# main_oled.net
KiCad netlist of a schematic drawn in EAGLE
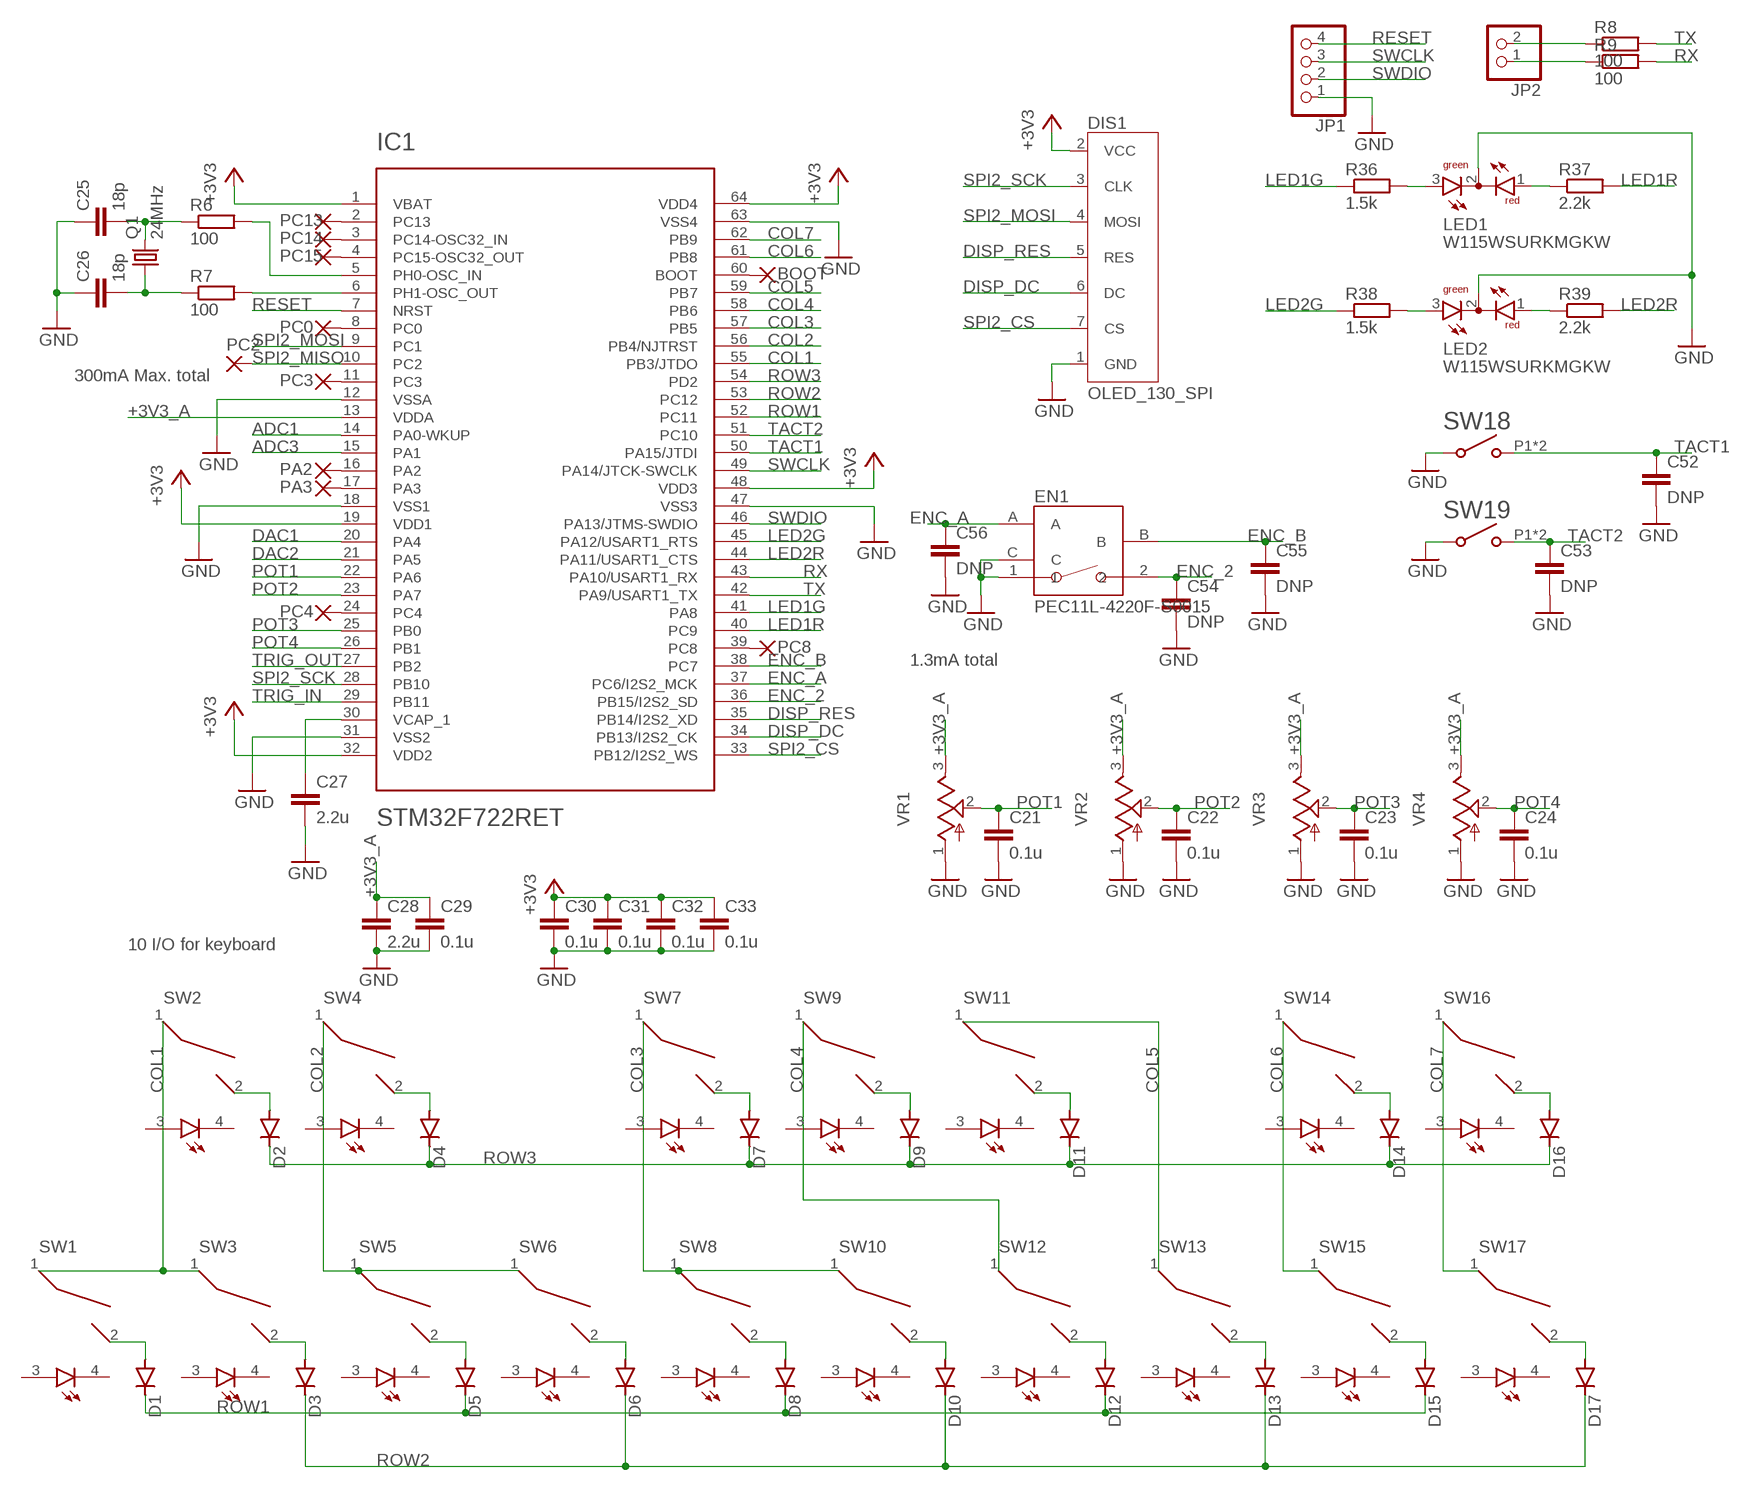
[diagram p0: schematic, sheet 1]
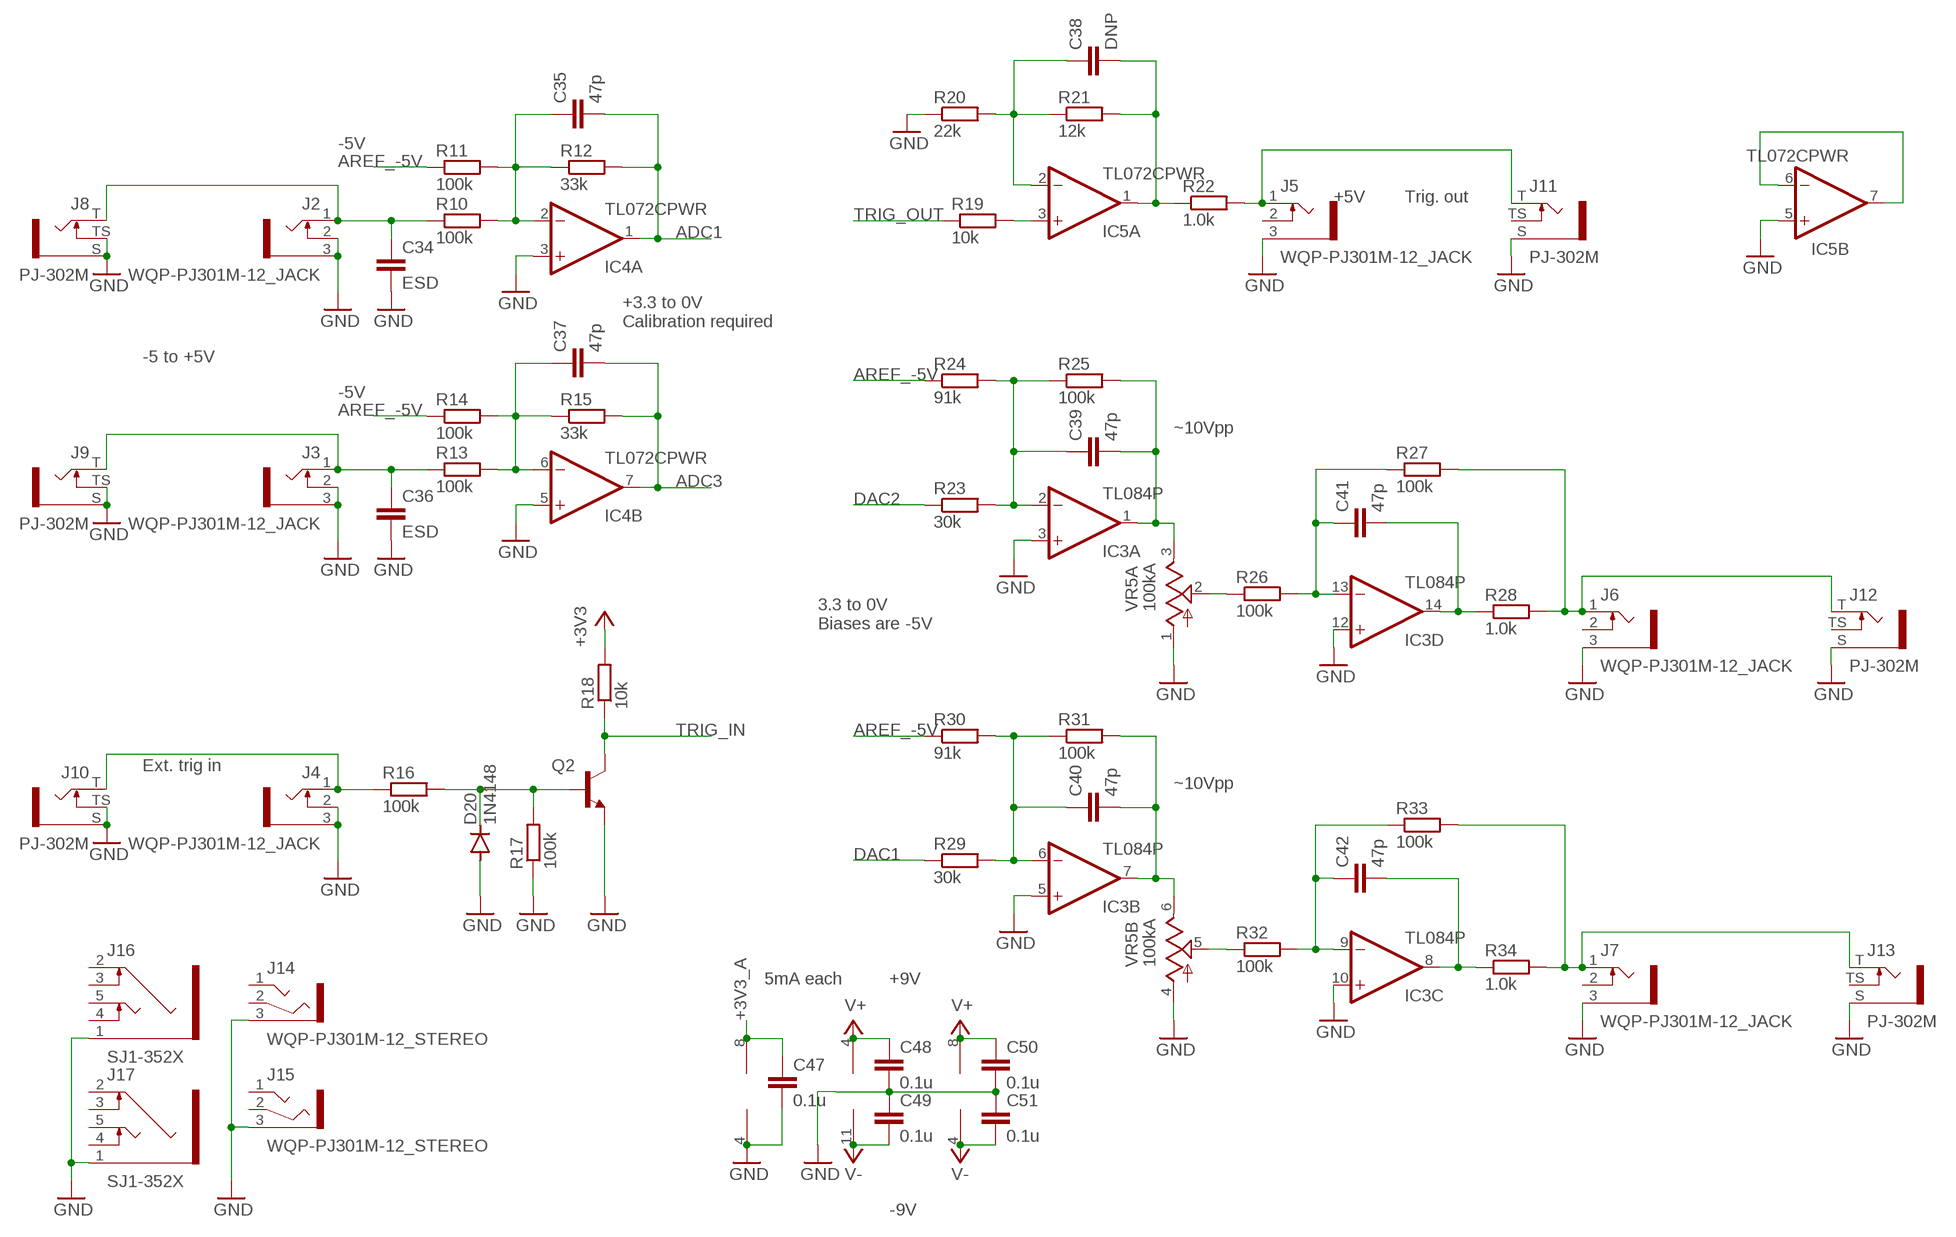
[diagram p1: schematic, sheet 2]
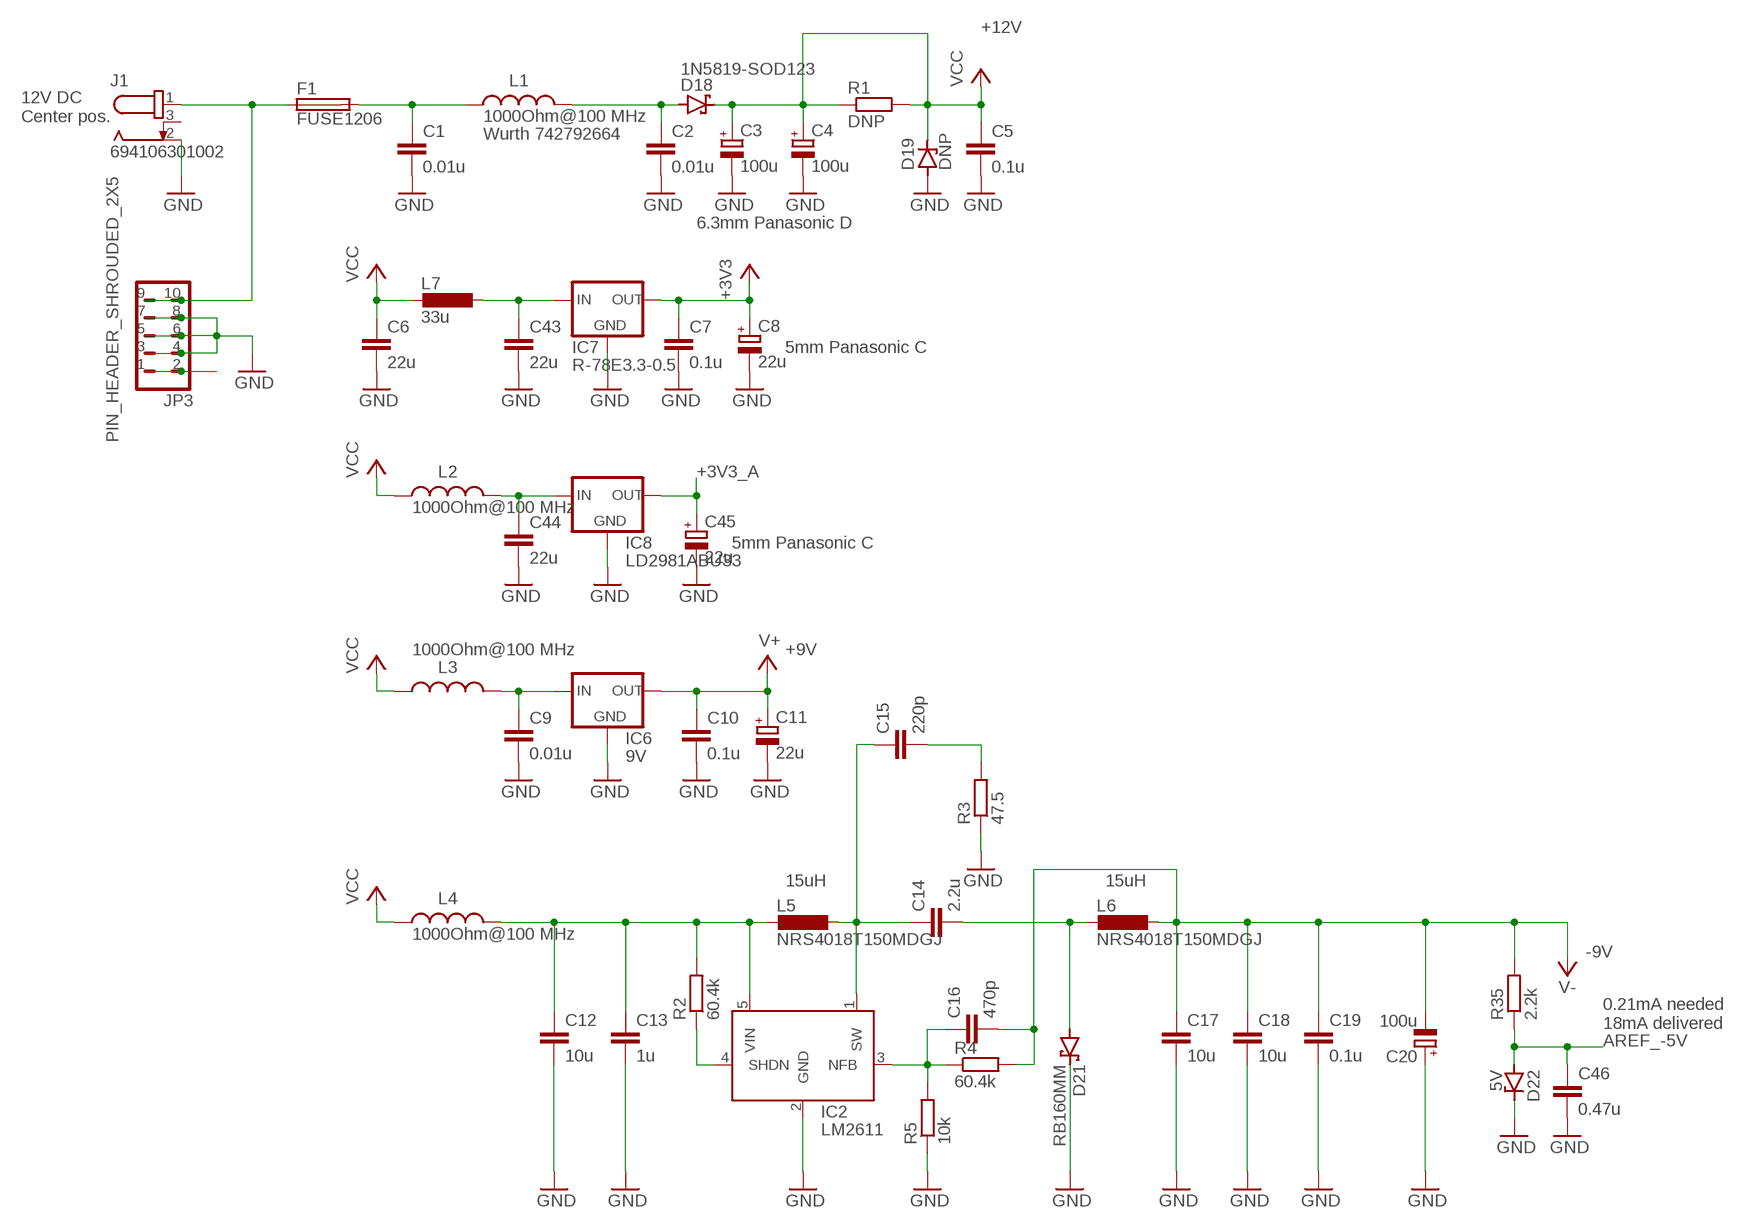
[diagram p2: schematic, sheet 3]
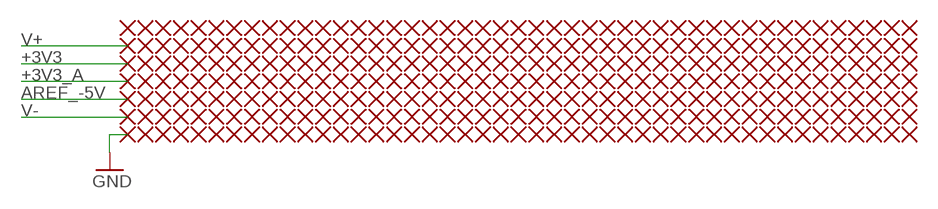
[diagram p3: schematic, sheet 4]

(export (version "E")
  (design (tool "Eeschema 10.0.6"))
  (components
    (comp (ref "C34")
      (value "ESD")
      (footprint "eagle-import:C0603")
      (libsource (lib "eagle-import") (part "C-EUC0603"))
    )
    (comp (ref "C35")
      (value "47p")
      (footprint "eagle-import:C0603")
      (libsource (lib "eagle-import") (part "C-EUC0603"))
    )
    (comp (ref "C36")
      (value "ESD")
      (footprint "eagle-import:C0603")
      (libsource (lib "eagle-import") (part "C-EUC0603"))
    )
    (comp (ref "C37")
      (value "47p")
      (footprint "eagle-import:C0603")
      (libsource (lib "eagle-import") (part "C-EUC0603"))
    )
    (comp (ref "C38")
      (value "DNP")
      (footprint "eagle-import:C0603")
      (libsource (lib "eagle-import") (part "C-EUC0603"))
    )
    (comp (ref "C39")
      (value "47p")
      (footprint "eagle-import:C0603")
      (libsource (lib "eagle-import") (part "C-EUC0603"))
    )
    (comp (ref "C40")
      (value "47p")
      (footprint "eagle-import:C0603")
      (libsource (lib "eagle-import") (part "C-EUC0603"))
    )
    (comp (ref "C41")
      (value "47p")
      (footprint "eagle-import:C0603")
      (libsource (lib "eagle-import") (part "C-EUC0603"))
    )
    (comp (ref "C42")
      (value "47p")
      (footprint "eagle-import:C0603")
      (libsource (lib "eagle-import") (part "C-EUC0603"))
    )
    (comp (ref "C47")
      (value "0.1u")
      (footprint "eagle-import:C0603")
      (libsource (lib "eagle-import") (part "C-EUC0603"))
    )
    (comp (ref "C48")
      (value "0.1u")
      (footprint "eagle-import:C0603")
      (libsource (lib "eagle-import") (part "C-EUC0603"))
    )
    (comp (ref "C49")
      (value "0.1u")
      (footprint "eagle-import:C0603")
      (libsource (lib "eagle-import") (part "C-EUC0603"))
    )
    (comp (ref "C50")
      (value "0.1u")
      (footprint "eagle-import:C0603")
      (libsource (lib "eagle-import") (part "C-EUC0603"))
    )
    (comp (ref "C51")
      (value "0.1u")
      (footprint "eagle-import:C0603")
      (libsource (lib "eagle-import") (part "C-EUC0603"))
    )
    (comp (ref "D20")
      (value "1N4148")
      (footprint "eagle-import:SOD123")
      (libsource (lib "eagle-import") (part "og_diode_DIODE-SOD123"))
    )
    (comp (ref "IC3")
      (value "TL084P")
      (footprint "eagle-import:TSSOP14")
      (libsource (lib "eagle-import") (part "TL084P"))
    )
    (comp (ref "IC4")
      (value "TL072CPWR")
      (footprint "eagle-import:TSSOP8")
      (libsource (lib "eagle-import") (part "TL072CPWR"))
    )
    (comp (ref "IC5")
      (value "TL072CPWR")
      (footprint "eagle-import:TSSOP8")
      (libsource (lib "eagle-import") (part "TL072CPWR"))
    )
    (comp (ref "J2")
      (value "WQP-PJ301M-12_JACK")
      (footprint "eagle-import:WQP-PJ301M-12_JACK")
      (libsource (lib "eagle-import") (part "WQP-PJ301M-12_JACK"))
    )
    (comp (ref "J3")
      (value "WQP-PJ301M-12_JACK")
      (footprint "eagle-import:WQP-PJ301M-12_JACK")
      (libsource (lib "eagle-import") (part "WQP-PJ301M-12_JACK"))
    )
    (comp (ref "J4")
      (value "WQP-PJ301M-12_JACK")
      (footprint "eagle-import:WQP-PJ301M-12_JACK")
      (libsource (lib "eagle-import") (part "WQP-PJ301M-12_JACK"))
    )
    (comp (ref "J5")
      (value "WQP-PJ301M-12_JACK")
      (footprint "eagle-import:WQP-PJ301M-12_JACK")
      (libsource (lib "eagle-import") (part "WQP-PJ301M-12_JACK"))
    )
    (comp (ref "J6")
      (value "WQP-PJ301M-12_JACK")
      (footprint "eagle-import:WQP-PJ301M-12_JACK")
      (libsource (lib "eagle-import") (part "WQP-PJ301M-12_JACK"))
    )
    (comp (ref "J7")
      (value "WQP-PJ301M-12_JACK")
      (footprint "eagle-import:WQP-PJ301M-12_JACK")
      (libsource (lib "eagle-import") (part "WQP-PJ301M-12_JACK"))
    )
    (comp (ref "J8")
      (value "PJ-302M")
      (footprint "eagle-import:PJ-302M")
      (libsource (lib "eagle-import") (part "PJ-302M"))
    )
    (comp (ref "J9")
      (value "PJ-302M")
      (footprint "eagle-import:PJ-302M")
      (libsource (lib "eagle-import") (part "PJ-302M"))
    )
    (comp (ref "J10")
      (value "PJ-302M")
      (footprint "eagle-import:PJ-302M")
      (libsource (lib "eagle-import") (part "PJ-302M"))
    )
    (comp (ref "J11")
      (value "PJ-302M")
      (footprint "eagle-import:PJ-302M")
      (libsource (lib "eagle-import") (part "PJ-302M"))
    )
    (comp (ref "J12")
      (value "PJ-302M")
      (footprint "eagle-import:PJ-302M")
      (libsource (lib "eagle-import") (part "PJ-302M"))
    )
    (comp (ref "J13")
      (value "PJ-302M")
      (footprint "eagle-import:PJ-302M")
      (libsource (lib "eagle-import") (part "PJ-302M"))
    )
    (comp (ref "J14")
      (value "WQP-PJ301M-12_STEREO")
      (footprint "eagle-import:WQP-PJ301M-12_JACK")
      (libsource (lib "eagle-import") (part "WQP-PJ301M-12_STEREO"))
    )
    (comp (ref "J15")
      (value "WQP-PJ301M-12_STEREO")
      (footprint "eagle-import:WQP-PJ301M-12_JACK")
      (libsource (lib "eagle-import") (part "WQP-PJ301M-12_STEREO"))
    )
    (comp (ref "J16")
      (value "SJ1-352X")
      (footprint "eagle-import:SJ1-352X")
      (libsource (lib "eagle-import") (part "SJ1-352X"))
    )
    (comp (ref "J17")
      (value "SJ1-352X")
      (footprint "eagle-import:SJ1-352X")
      (libsource (lib "eagle-import") (part "SJ1-352X"))
    )
    (comp (ref "Q2")
      (value "MMBT3904LT1-NPN-SOT23-BEC")
      (footprint "eagle-import:SOT23-BEC")
      (libsource (lib "eagle-import") (part "-NPN-SOT23-BECMMBT3904LT1"))
    )
    (comp (ref "R10")
      (value "100k")
      (footprint "eagle-import:R0603")
      (libsource (lib "eagle-import") (part "R-EU_R0603"))
    )
    (comp (ref "R11")
      (value "100k")
      (footprint "eagle-import:R0603")
      (libsource (lib "eagle-import") (part "R-EU_R0603"))
    )
    (comp (ref "R12")
      (value "33k")
      (footprint "eagle-import:R0603")
      (libsource (lib "eagle-import") (part "R-EU_R0603"))
    )
    (comp (ref "R13")
      (value "100k")
      (footprint "eagle-import:R0603")
      (libsource (lib "eagle-import") (part "R-EU_R0603"))
    )
    (comp (ref "R14")
      (value "100k")
      (footprint "eagle-import:R0603")
      (libsource (lib "eagle-import") (part "R-EU_R0603"))
    )
    (comp (ref "R15")
      (value "33k")
      (footprint "eagle-import:R0603")
      (libsource (lib "eagle-import") (part "R-EU_R0603"))
    )
    (comp (ref "R16")
      (value "100k")
      (footprint "eagle-import:R0603")
      (libsource (lib "eagle-import") (part "R-EU_R0603"))
    )
    (comp (ref "R17")
      (value "100k")
      (footprint "eagle-import:R0603")
      (libsource (lib "eagle-import") (part "R-EU_R0603"))
    )
    (comp (ref "R18")
      (value "10k")
      (footprint "eagle-import:R0603")
      (libsource (lib "eagle-import") (part "R-EU_R0603"))
    )
    (comp (ref "R19")
      (value "10k")
      (footprint "eagle-import:R0603")
      (libsource (lib "eagle-import") (part "R-EU_R0603"))
    )
    (comp (ref "R20")
      (value "22k")
      (footprint "eagle-import:R0603")
      (libsource (lib "eagle-import") (part "R-EU_R0603"))
    )
    (comp (ref "R21")
      (value "12k")
      (footprint "eagle-import:R0603")
      (libsource (lib "eagle-import") (part "R-EU_R0603"))
    )
    (comp (ref "R22")
      (value "1.0k")
      (footprint "eagle-import:R0603")
      (libsource (lib "eagle-import") (part "R-EU_R0603"))
    )
    (comp (ref "R23")
      (value "30k")
      (footprint "eagle-import:R0603")
      (libsource (lib "eagle-import") (part "R-EU_R0603"))
    )
    (comp (ref "R24")
      (value "91k")
      (footprint "eagle-import:R0603")
      (libsource (lib "eagle-import") (part "R-EU_R0603"))
    )
    (comp (ref "R25")
      (value "100k")
      (footprint "eagle-import:R0603")
      (libsource (lib "eagle-import") (part "R-EU_R0603"))
    )
    (comp (ref "R26")
      (value "100k")
      (footprint "eagle-import:R0603")
      (libsource (lib "eagle-import") (part "R-EU_R0603"))
    )
    (comp (ref "R27")
      (value "100k")
      (footprint "eagle-import:R0603")
      (libsource (lib "eagle-import") (part "R-EU_R0603"))
    )
    (comp (ref "R28")
      (value "1.0k")
      (footprint "eagle-import:R0603")
      (libsource (lib "eagle-import") (part "R-EU_R0603"))
    )
    (comp (ref "R29")
      (value "30k")
      (footprint "eagle-import:R0603")
      (libsource (lib "eagle-import") (part "R-EU_R0603"))
    )
    (comp (ref "R30")
      (value "91k")
      (footprint "eagle-import:R0603")
      (libsource (lib "eagle-import") (part "R-EU_R0603"))
    )
    (comp (ref "R31")
      (value "100k")
      (footprint "eagle-import:R0603")
      (libsource (lib "eagle-import") (part "R-EU_R0603"))
    )
    (comp (ref "R32")
      (value "100k")
      (footprint "eagle-import:R0603")
      (libsource (lib "eagle-import") (part "R-EU_R0603"))
    )
    (comp (ref "R33")
      (value "100k")
      (footprint "eagle-import:R0603")
      (libsource (lib "eagle-import") (part "R-EU_R0603"))
    )
    (comp (ref "R34")
      (value "1.0k")
      (footprint "eagle-import:R0603")
      (libsource (lib "eagle-import") (part "R-EU_R0603"))
    )
    (comp (ref "VR5")
      (value "100kA")
      (footprint "eagle-import:9MM_V_DUAL")
      (libsource (lib "eagle-import") (part "9MM_V_DUAL"))
    )
    (comp (ref "P1")
      (value "PERF_2.54")
      (footprint "eagle-import:PERF_2.54")
      (libsource (lib "eagle-import") (part "PERF_2.54"))
    )
    (comp (ref "P2")
      (value "PERF_2.54")
      (footprint "eagle-import:PERF_2.54")
      (libsource (lib "eagle-import") (part "PERF_2.54"))
    )
    (comp (ref "P3")
      (value "PERF_2.54")
      (footprint "eagle-import:PERF_2.54")
      (libsource (lib "eagle-import") (part "PERF_2.54"))
    )
    (comp (ref "P4")
      (value "PERF_2.54")
      (footprint "eagle-import:PERF_2.54")
      (libsource (lib "eagle-import") (part "PERF_2.54"))
    )
    (comp (ref "P5")
      (value "PERF_2.54")
      (footprint "eagle-import:PERF_2.54")
      (libsource (lib "eagle-import") (part "PERF_2.54"))
    )
    (comp (ref "P6")
      (value "PERF_2.54")
      (footprint "eagle-import:PERF_2.54")
      (libsource (lib "eagle-import") (part "PERF_2.54"))
    )
    (comp (ref "P7")
      (value "PERF_2.54")
      (footprint "eagle-import:PERF_2.54")
      (libsource (lib "eagle-import") (part "PERF_2.54"))
    )
    (comp (ref "P8")
      (value "PERF_2.54")
      (footprint "eagle-import:PERF_2.54")
      (libsource (lib "eagle-import") (part "PERF_2.54"))
    )
    (comp (ref "P9")
      (value "PERF_2.54")
      (footprint "eagle-import:PERF_2.54")
      (libsource (lib "eagle-import") (part "PERF_2.54"))
    )
    (comp (ref "P10")
      (value "PERF_2.54")
      (footprint "eagle-import:PERF_2.54")
      (libsource (lib "eagle-import") (part "PERF_2.54"))
    )
    (comp (ref "P11")
      (value "PERF_2.54")
      (footprint "eagle-import:PERF_2.54")
      (libsource (lib "eagle-import") (part "PERF_2.54"))
    )
    (comp (ref "P12")
      (value "PERF_2.54")
      (footprint "eagle-import:PERF_2.54")
      (libsource (lib "eagle-import") (part "PERF_2.54"))
    )
    (comp (ref "P13")
      (value "PERF_2.54")
      (footprint "eagle-import:PERF_2.54")
      (libsource (lib "eagle-import") (part "PERF_2.54"))
    )
    (comp (ref "P14")
      (value "PERF_2.54")
      (footprint "eagle-import:PERF_2.54")
      (libsource (lib "eagle-import") (part "PERF_2.54"))
    )
    (comp (ref "P15")
      (value "PERF_2.54")
      (footprint "eagle-import:PERF_2.54")
      (libsource (lib "eagle-import") (part "PERF_2.54"))
    )
    (comp (ref "P16")
      (value "PERF_2.54")
      (footprint "eagle-import:PERF_2.54")
      (libsource (lib "eagle-import") (part "PERF_2.54"))
    )
    (comp (ref "P17")
      (value "PERF_2.54")
      (footprint "eagle-import:PERF_2.54")
      (libsource (lib "eagle-import") (part "PERF_2.54"))
    )
    (comp (ref "P18")
      (value "PERF_2.54")
      (footprint "eagle-import:PERF_2.54")
      (libsource (lib "eagle-import") (part "PERF_2.54"))
    )
    (comp (ref "P19")
      (value "PERF_2.54")
      (footprint "eagle-import:PERF_2.54")
      (libsource (lib "eagle-import") (part "PERF_2.54"))
    )
    (comp (ref "P20")
      (value "PERF_2.54")
      (footprint "eagle-import:PERF_2.54")
      (libsource (lib "eagle-import") (part "PERF_2.54"))
    )
    (comp (ref "P21")
      (value "PERF_2.54")
      (footprint "eagle-import:PERF_2.54")
      (libsource (lib "eagle-import") (part "PERF_2.54"))
    )
    (comp (ref "P22")
      (value "PERF_2.54")
      (footprint "eagle-import:PERF_2.54")
      (libsource (lib "eagle-import") (part "PERF_2.54"))
    )
    (comp (ref "P23")
      (value "PERF_2.54")
      (footprint "eagle-import:PERF_2.54")
      (libsource (lib "eagle-import") (part "PERF_2.54"))
    )
    (comp (ref "P24")
      (value "PERF_2.54")
      (footprint "eagle-import:PERF_2.54")
      (libsource (lib "eagle-import") (part "PERF_2.54"))
    )
    (comp (ref "P25")
      (value "PERF_2.54")
      (footprint "eagle-import:PERF_2.54")
      (libsource (lib "eagle-import") (part "PERF_2.54"))
    )
    (comp (ref "P26")
      (value "PERF_2.54")
      (footprint "eagle-import:PERF_2.54")
      (libsource (lib "eagle-import") (part "PERF_2.54"))
    )
    (comp (ref "P27")
      (value "PERF_2.54")
      (footprint "eagle-import:PERF_2.54")
      (libsource (lib "eagle-import") (part "PERF_2.54"))
    )
    (comp (ref "P28")
      (value "PERF_2.54")
      (footprint "eagle-import:PERF_2.54")
      (libsource (lib "eagle-import") (part "PERF_2.54"))
    )
    (comp (ref "P29")
      (value "PERF_2.54")
      (footprint "eagle-import:PERF_2.54")
      (libsource (lib "eagle-import") (part "PERF_2.54"))
    )
    (comp (ref "P30")
      (value "PERF_2.54")
      (footprint "eagle-import:PERF_2.54")
      (libsource (lib "eagle-import") (part "PERF_2.54"))
    )
    (comp (ref "P31")
      (value "PERF_2.54")
      (footprint "eagle-import:PERF_2.54")
      (libsource (lib "eagle-import") (part "PERF_2.54"))
    )
    (comp (ref "P32")
      (value "PERF_2.54")
      (footprint "eagle-import:PERF_2.54")
      (libsource (lib "eagle-import") (part "PERF_2.54"))
    )
    (comp (ref "P33")
      (value "PERF_2.54")
      (footprint "eagle-import:PERF_2.54")
      (libsource (lib "eagle-import") (part "PERF_2.54"))
    )
    (comp (ref "P34")
      (value "PERF_2.54")
      (footprint "eagle-import:PERF_2.54")
      (libsource (lib "eagle-import") (part "PERF_2.54"))
    )
    (comp (ref "P35")
      (value "PERF_2.54")
      (footprint "eagle-import:PERF_2.54")
      (libsource (lib "eagle-import") (part "PERF_2.54"))
    )
    (comp (ref "P36")
      (value "PERF_2.54")
      (footprint "eagle-import:PERF_2.54")
      (libsource (lib "eagle-import") (part "PERF_2.54"))
    )
    (comp (ref "P37")
      (value "PERF_2.54")
      (footprint "eagle-import:PERF_2.54")
      (libsource (lib "eagle-import") (part "PERF_2.54"))
    )
    (comp (ref "P38")
      (value "PERF_2.54")
      (footprint "eagle-import:PERF_2.54")
      (libsource (lib "eagle-import") (part "PERF_2.54"))
    )
    (comp (ref "P39")
      (value "PERF_2.54")
      (footprint "eagle-import:PERF_2.54")
      (libsource (lib "eagle-import") (part "PERF_2.54"))
    )
    (comp (ref "P40")
      (value "PERF_2.54")
      (footprint "eagle-import:PERF_2.54")
      (libsource (lib "eagle-import") (part "PERF_2.54"))
    )
    (comp (ref "P41")
      (value "PERF_2.54")
      (footprint "eagle-import:PERF_2.54")
      (libsource (lib "eagle-import") (part "PERF_2.54"))
    )
    (comp (ref "P42")
      (value "PERF_2.54")
      (footprint "eagle-import:PERF_2.54")
      (libsource (lib "eagle-import") (part "PERF_2.54"))
    )
    (comp (ref "P43")
      (value "PERF_2.54")
      (footprint "eagle-import:PERF_2.54")
      (libsource (lib "eagle-import") (part "PERF_2.54"))
    )
    (comp (ref "P44")
      (value "PERF_2.54")
      (footprint "eagle-import:PERF_2.54")
      (libsource (lib "eagle-import") (part "PERF_2.54"))
    )
    (comp (ref "P45")
      (value "PERF_2.54")
      (footprint "eagle-import:PERF_2.54")
      (libsource (lib "eagle-import") (part "PERF_2.54"))
    )
    (comp (ref "P46")
      (value "PERF_2.54")
      (footprint "eagle-import:PERF_2.54")
      (libsource (lib "eagle-import") (part "PERF_2.54"))
    )
    (comp (ref "P47")
      (value "PERF_2.54")
      (footprint "eagle-import:PERF_2.54")
      (libsource (lib "eagle-import") (part "PERF_2.54"))
    )
    (comp (ref "P48")
      (value "PERF_2.54")
      (footprint "eagle-import:PERF_2.54")
      (libsource (lib "eagle-import") (part "PERF_2.54"))
    )
    (comp (ref "P49")
      (value "PERF_2.54")
      (footprint "eagle-import:PERF_2.54")
      (libsource (lib "eagle-import") (part "PERF_2.54"))
    )
    (comp (ref "P50")
      (value "PERF_2.54")
      (footprint "eagle-import:PERF_2.54")
      (libsource (lib "eagle-import") (part "PERF_2.54"))
    )
    (comp (ref "P51")
      (value "PERF_2.54")
      (footprint "eagle-import:PERF_2.54")
      (libsource (lib "eagle-import") (part "PERF_2.54"))
    )
    (comp (ref "P52")
      (value "PERF_2.54")
      (footprint "eagle-import:PERF_2.54")
      (libsource (lib "eagle-import") (part "PERF_2.54"))
    )
    (comp (ref "P53")
      (value "PERF_2.54")
      (footprint "eagle-import:PERF_2.54")
      (libsource (lib "eagle-import") (part "PERF_2.54"))
    )
    (comp (ref "P54")
      (value "PERF_2.54")
      (footprint "eagle-import:PERF_2.54")
      (libsource (lib "eagle-import") (part "PERF_2.54"))
    )
    (comp (ref "P55")
      (value "PERF_2.54")
      (footprint "eagle-import:PERF_2.54")
      (libsource (lib "eagle-import") (part "PERF_2.54"))
    )
    (comp (ref "P56")
      (value "PERF_2.54")
      (footprint "eagle-import:PERF_2.54")
      (libsource (lib "eagle-import") (part "PERF_2.54"))
    )
    (comp (ref "P57")
      (value "PERF_2.54")
      (footprint "eagle-import:PERF_2.54")
      (libsource (lib "eagle-import") (part "PERF_2.54"))
    )
    (comp (ref "P58")
      (value "PERF_2.54")
      (footprint "eagle-import:PERF_2.54")
      (libsource (lib "eagle-import") (part "PERF_2.54"))
    )
    (comp (ref "P59")
      (value "PERF_2.54")
      (footprint "eagle-import:PERF_2.54")
      (libsource (lib "eagle-import") (part "PERF_2.54"))
    )
    (comp (ref "P60")
      (value "PERF_2.54")
      (footprint "eagle-import:PERF_2.54")
      (libsource (lib "eagle-import") (part "PERF_2.54"))
    )
    (comp (ref "P61")
      (value "PERF_2.54")
      (footprint "eagle-import:PERF_2.54")
      (libsource (lib "eagle-import") (part "PERF_2.54"))
    )
    (comp (ref "P62")
      (value "PERF_2.54")
      (footprint "eagle-import:PERF_2.54")
      (libsource (lib "eagle-import") (part "PERF_2.54"))
    )
    (comp (ref "P63")
      (value "PERF_2.54")
      (footprint "eagle-import:PERF_2.54")
      (libsource (lib "eagle-import") (part "PERF_2.54"))
    )
    (comp (ref "P64")
      (value "PERF_2.54")
      (footprint "eagle-import:PERF_2.54")
      (libsource (lib "eagle-import") (part "PERF_2.54"))
    )
    (comp (ref "P65")
      (value "PERF_2.54")
      (footprint "eagle-import:PERF_2.54")
      (libsource (lib "eagle-import") (part "PERF_2.54"))
    )
    (comp (ref "P66")
      (value "PERF_2.54")
      (footprint "eagle-import:PERF_2.54")
      (libsource (lib "eagle-import") (part "PERF_2.54"))
    )
    (comp (ref "P67")
      (value "PERF_2.54")
      (footprint "eagle-import:PERF_2.54")
      (libsource (lib "eagle-import") (part "PERF_2.54"))
    )
    (comp (ref "P68")
      (value "PERF_2.54")
      (footprint "eagle-import:PERF_2.54")
      (libsource (lib "eagle-import") (part "PERF_2.54"))
    )
    (comp (ref "P69")
      (value "PERF_2.54")
      (footprint "eagle-import:PERF_2.54")
      (libsource (lib "eagle-import") (part "PERF_2.54"))
    )
    (comp (ref "P70")
      (value "PERF_2.54")
      (footprint "eagle-import:PERF_2.54")
      (libsource (lib "eagle-import") (part "PERF_2.54"))
    )
    (comp (ref "P71")
      (value "PERF_2.54")
      (footprint "eagle-import:PERF_2.54")
      (libsource (lib "eagle-import") (part "PERF_2.54"))
    )
    (comp (ref "P72")
      (value "PERF_2.54")
      (footprint "eagle-import:PERF_2.54")
      (libsource (lib "eagle-import") (part "PERF_2.54"))
    )
    (comp (ref "P73")
      (value "PERF_2.54")
      (footprint "eagle-import:PERF_2.54")
      (libsource (lib "eagle-import") (part "PERF_2.54"))
    )
    (comp (ref "P74")
      (value "PERF_2.54")
      (footprint "eagle-import:PERF_2.54")
      (libsource (lib "eagle-import") (part "PERF_2.54"))
    )
    (comp (ref "P75")
      (value "PERF_2.54")
      (footprint "eagle-import:PERF_2.54")
      (libsource (lib "eagle-import") (part "PERF_2.54"))
    )
    (comp (ref "P76")
      (value "PERF_2.54")
      (footprint "eagle-import:PERF_2.54")
      (libsource (lib "eagle-import") (part "PERF_2.54"))
    )
    (comp (ref "P77")
      (value "PERF_2.54")
      (footprint "eagle-import:PERF_2.54")
      (libsource (lib "eagle-import") (part "PERF_2.54"))
    )
    (comp (ref "P78")
      (value "PERF_2.54")
      (footprint "eagle-import:PERF_2.54")
      (libsource (lib "eagle-import") (part "PERF_2.54"))
    )
    (comp (ref "P79")
      (value "PERF_2.54")
      (footprint "eagle-import:PERF_2.54")
      (libsource (lib "eagle-import") (part "PERF_2.54"))
    )
    (comp (ref "P80")
      (value "PERF_2.54")
      (footprint "eagle-import:PERF_2.54")
      (libsource (lib "eagle-import") (part "PERF_2.54"))
    )
    (comp (ref "P81")
      (value "PERF_2.54")
      (footprint "eagle-import:PERF_2.54")
      (libsource (lib "eagle-import") (part "PERF_2.54"))
    )
    (comp (ref "P82")
      (value "PERF_2.54")
      (footprint "eagle-import:PERF_2.54")
      (libsource (lib "eagle-import") (part "PERF_2.54"))
    )
    (comp (ref "P83")
      (value "PERF_2.54")
      (footprint "eagle-import:PERF_2.54")
      (libsource (lib "eagle-import") (part "PERF_2.54"))
    )
    (comp (ref "P84")
      (value "PERF_2.54")
      (footprint "eagle-import:PERF_2.54")
      (libsource (lib "eagle-import") (part "PERF_2.54"))
    )
    (comp (ref "P85")
      (value "PERF_2.54")
      (footprint "eagle-import:PERF_2.54")
      (libsource (lib "eagle-import") (part "PERF_2.54"))
    )
    (comp (ref "P86")
      (value "PERF_2.54")
      (footprint "eagle-import:PERF_2.54")
      (libsource (lib "eagle-import") (part "PERF_2.54"))
    )
    (comp (ref "P87")
      (value "PERF_2.54")
      (footprint "eagle-import:PERF_2.54")
      (libsource (lib "eagle-import") (part "PERF_2.54"))
    )
    (comp (ref "P88")
      (value "PERF_2.54")
      (footprint "eagle-import:PERF_2.54")
      (libsource (lib "eagle-import") (part "PERF_2.54"))
    )
    (comp (ref "P89")
      (value "PERF_2.54")
      (footprint "eagle-import:PERF_2.54")
      (libsource (lib "eagle-import") (part "PERF_2.54"))
    )
    (comp (ref "P90")
      (value "PERF_2.54")
      (footprint "eagle-import:PERF_2.54")
      (libsource (lib "eagle-import") (part "PERF_2.54"))
    )
    (comp (ref "P91")
      (value "PERF_2.54")
      (footprint "eagle-import:PERF_2.54")
      (libsource (lib "eagle-import") (part "PERF_2.54"))
    )
    (comp (ref "P92")
      (value "PERF_2.54")
      (footprint "eagle-import:PERF_2.54")
      (libsource (lib "eagle-import") (part "PERF_2.54"))
    )
    (comp (ref "P93")
      (value "PERF_2.54")
      (footprint "eagle-import:PERF_2.54")
      (libsource (lib "eagle-import") (part "PERF_2.54"))
    )
    (comp (ref "P94")
      (value "PERF_2.54")
      (footprint "eagle-import:PERF_2.54")
      (libsource (lib "eagle-import") (part "PERF_2.54"))
    )
    (comp (ref "P95")
      (value "PERF_2.54")
      (footprint "eagle-import:PERF_2.54")
      (libsource (lib "eagle-import") (part "PERF_2.54"))
    )
    (comp (ref "P96")
      (value "PERF_2.54")
      (footprint "eagle-import:PERF_2.54")
      (libsource (lib "eagle-import") (part "PERF_2.54"))
    )
    (comp (ref "P97")
      (value "PERF_2.54")
      (footprint "eagle-import:PERF_2.54")
      (libsource (lib "eagle-import") (part "PERF_2.54"))
    )
    (comp (ref "P98")
      (value "PERF_2.54")
      (footprint "eagle-import:PERF_2.54")
      (libsource (lib "eagle-import") (part "PERF_2.54"))
    )
    (comp (ref "P99")
      (value "PERF_2.54")
      (footprint "eagle-import:PERF_2.54")
      (libsource (lib "eagle-import") (part "PERF_2.54"))
    )
    (comp (ref "P100")
      (value "PERF_2.54")
      (footprint "eagle-import:PERF_2.54")
      (libsource (lib "eagle-import") (part "PERF_2.54"))
    )
    (comp (ref "P101")
      (value "PERF_2.54")
      (footprint "eagle-import:PERF_2.54")
      (libsource (lib "eagle-import") (part "PERF_2.54"))
    )
    (comp (ref "P102")
      (value "PERF_2.54")
      (footprint "eagle-import:PERF_2.54")
      (libsource (lib "eagle-import") (part "PERF_2.54"))
    )
    (comp (ref "P103")
      (value "PERF_2.54")
      (footprint "eagle-import:PERF_2.54")
      (libsource (lib "eagle-import") (part "PERF_2.54"))
    )
    (comp (ref "P104")
      (value "PERF_2.54")
      (footprint "eagle-import:PERF_2.54")
      (libsource (lib "eagle-import") (part "PERF_2.54"))
    )
    (comp (ref "P105")
      (value "PERF_2.54")
      (footprint "eagle-import:PERF_2.54")
      (libsource (lib "eagle-import") (part "PERF_2.54"))
    )
    (comp (ref "P106")
      (value "PERF_2.54")
      (footprint "eagle-import:PERF_2.54")
      (libsource (lib "eagle-import") (part "PERF_2.54"))
    )
    (comp (ref "P107")
      (value "PERF_2.54")
      (footprint "eagle-import:PERF_2.54")
      (libsource (lib "eagle-import") (part "PERF_2.54"))
    )
    (comp (ref "P108")
      (value "PERF_2.54")
      (footprint "eagle-import:PERF_2.54")
      (libsource (lib "eagle-import") (part "PERF_2.54"))
    )
    (comp (ref "P109")
      (value "PERF_2.54")
      (footprint "eagle-import:PERF_2.54")
      (libsource (lib "eagle-import") (part "PERF_2.54"))
    )
    (comp (ref "P110")
      (value "PERF_2.54")
      (footprint "eagle-import:PERF_2.54")
      (libsource (lib "eagle-import") (part "PERF_2.54"))
    )
    (comp (ref "P111")
      (value "PERF_2.54")
      (footprint "eagle-import:PERF_2.54")
      (libsource (lib "eagle-import") (part "PERF_2.54"))
    )
    (comp (ref "P112")
      (value "PERF_2.54")
      (footprint "eagle-import:PERF_2.54")
      (libsource (lib "eagle-import") (part "PERF_2.54"))
    )
    (comp (ref "P113")
      (value "PERF_2.54")
      (footprint "eagle-import:PERF_2.54")
      (libsource (lib "eagle-import") (part "PERF_2.54"))
    )
    (comp (ref "P114")
      (value "PERF_2.54")
      (footprint "eagle-import:PERF_2.54")
      (libsource (lib "eagle-import") (part "PERF_2.54"))
    )
    (comp (ref "P115")
      (value "PERF_2.54")
      (footprint "eagle-import:PERF_2.54")
      (libsource (lib "eagle-import") (part "PERF_2.54"))
    )
    (comp (ref "P116")
      (value "PERF_2.54")
      (footprint "eagle-import:PERF_2.54")
      (libsource (lib "eagle-import") (part "PERF_2.54"))
    )
    (comp (ref "P117")
      (value "PERF_2.54")
      (footprint "eagle-import:PERF_2.54")
      (libsource (lib "eagle-import") (part "PERF_2.54"))
    )
    (comp (ref "P118")
      (value "PERF_2.54")
      (footprint "eagle-import:PERF_2.54")
      (libsource (lib "eagle-import") (part "PERF_2.54"))
    )
    (comp (ref "P119")
      (value "PERF_2.54")
      (footprint "eagle-import:PERF_2.54")
      (libsource (lib "eagle-import") (part "PERF_2.54"))
    )
    (comp (ref "P120")
      (value "PERF_2.54")
      (footprint "eagle-import:PERF_2.54")
      (libsource (lib "eagle-import") (part "PERF_2.54"))
    )
    (comp (ref "P121")
      (value "PERF_2.54")
      (footprint "eagle-import:PERF_2.54")
      (libsource (lib "eagle-import") (part "PERF_2.54"))
    )
    (comp (ref "P122")
      (value "PERF_2.54")
      (footprint "eagle-import:PERF_2.54")
      (libsource (lib "eagle-import") (part "PERF_2.54"))
    )
    (comp (ref "P123")
      (value "PERF_2.54")
      (footprint "eagle-import:PERF_2.54")
      (libsource (lib "eagle-import") (part "PERF_2.54"))
    )
    (comp (ref "P124")
      (value "PERF_2.54")
      (footprint "eagle-import:PERF_2.54")
      (libsource (lib "eagle-import") (part "PERF_2.54"))
    )
    (comp (ref "P125")
      (value "PERF_2.54")
      (footprint "eagle-import:PERF_2.54")
      (libsource (lib "eagle-import") (part "PERF_2.54"))
    )
    (comp (ref "P126")
      (value "PERF_2.54")
      (footprint "eagle-import:PERF_2.54")
      (libsource (lib "eagle-import") (part "PERF_2.54"))
    )
    (comp (ref "P127")
      (value "PERF_2.54")
      (footprint "eagle-import:PERF_2.54")
      (libsource (lib "eagle-import") (part "PERF_2.54"))
    )
    (comp (ref "P128")
      (value "PERF_2.54")
      (footprint "eagle-import:PERF_2.54")
      (libsource (lib "eagle-import") (part "PERF_2.54"))
    )
    (comp (ref "P129")
      (value "PERF_2.54")
      (footprint "eagle-import:PERF_2.54")
      (libsource (lib "eagle-import") (part "PERF_2.54"))
    )
    (comp (ref "P130")
      (value "PERF_2.54")
      (footprint "eagle-import:PERF_2.54")
      (libsource (lib "eagle-import") (part "PERF_2.54"))
    )
    (comp (ref "P131")
      (value "PERF_2.54")
      (footprint "eagle-import:PERF_2.54")
      (libsource (lib "eagle-import") (part "PERF_2.54"))
    )
    (comp (ref "P132")
      (value "PERF_2.54")
      (footprint "eagle-import:PERF_2.54")
      (libsource (lib "eagle-import") (part "PERF_2.54"))
    )
    (comp (ref "P133")
      (value "PERF_2.54")
      (footprint "eagle-import:PERF_2.54")
      (libsource (lib "eagle-import") (part "PERF_2.54"))
    )
    (comp (ref "P134")
      (value "PERF_2.54")
      (footprint "eagle-import:PERF_2.54")
      (libsource (lib "eagle-import") (part "PERF_2.54"))
    )
    (comp (ref "P135")
      (value "PERF_2.54")
      (footprint "eagle-import:PERF_2.54")
      (libsource (lib "eagle-import") (part "PERF_2.54"))
    )
    (comp (ref "P136")
      (value "PERF_2.54")
      (footprint "eagle-import:PERF_2.54")
      (libsource (lib "eagle-import") (part "PERF_2.54"))
    )
    (comp (ref "P137")
      (value "PERF_2.54")
      (footprint "eagle-import:PERF_2.54")
      (libsource (lib "eagle-import") (part "PERF_2.54"))
    )
    (comp (ref "P138")
      (value "PERF_2.54")
      (footprint "eagle-import:PERF_2.54")
      (libsource (lib "eagle-import") (part "PERF_2.54"))
    )
    (comp (ref "P139")
      (value "PERF_2.54")
      (footprint "eagle-import:PERF_2.54")
      (libsource (lib "eagle-import") (part "PERF_2.54"))
    )
    (comp (ref "P140")
      (value "PERF_2.54")
      (footprint "eagle-import:PERF_2.54")
      (libsource (lib "eagle-import") (part "PERF_2.54"))
    )
    (comp (ref "P141")
      (value "PERF_2.54")
      (footprint "eagle-import:PERF_2.54")
      (libsource (lib "eagle-import") (part "PERF_2.54"))
    )
    (comp (ref "P142")
      (value "PERF_2.54")
      (footprint "eagle-import:PERF_2.54")
      (libsource (lib "eagle-import") (part "PERF_2.54"))
    )
    (comp (ref "P143")
      (value "PERF_2.54")
      (footprint "eagle-import:PERF_2.54")
      (libsource (lib "eagle-import") (part "PERF_2.54"))
    )
    (comp (ref "P144")
      (value "PERF_2.54")
      (footprint "eagle-import:PERF_2.54")
      (libsource (lib "eagle-import") (part "PERF_2.54"))
    )
    (comp (ref "P145")
      (value "PERF_2.54")
      (footprint "eagle-import:PERF_2.54")
      (libsource (lib "eagle-import") (part "PERF_2.54"))
    )
    (comp (ref "P146")
      (value "PERF_2.54")
      (footprint "eagle-import:PERF_2.54")
      (libsource (lib "eagle-import") (part "PERF_2.54"))
    )
    (comp (ref "P147")
      (value "PERF_2.54")
      (footprint "eagle-import:PERF_2.54")
      (libsource (lib "eagle-import") (part "PERF_2.54"))
    )
    (comp (ref "P148")
      (value "PERF_2.54")
      (footprint "eagle-import:PERF_2.54")
      (libsource (lib "eagle-import") (part "PERF_2.54"))
    )
    (comp (ref "P149")
      (value "PERF_2.54")
      (footprint "eagle-import:PERF_2.54")
      (libsource (lib "eagle-import") (part "PERF_2.54"))
    )
    (comp (ref "P150")
      (value "PERF_2.54")
      (footprint "eagle-import:PERF_2.54")
      (libsource (lib "eagle-import") (part "PERF_2.54"))
    )
    (comp (ref "P151")
      (value "PERF_2.54")
      (footprint "eagle-import:PERF_2.54")
      (libsource (lib "eagle-import") (part "PERF_2.54"))
    )
    (comp (ref "P152")
      (value "PERF_2.54")
      (footprint "eagle-import:PERF_2.54")
      (libsource (lib "eagle-import") (part "PERF_2.54"))
    )
    (comp (ref "P153")
      (value "PERF_2.54")
      (footprint "eagle-import:PERF_2.54")
      (libsource (lib "eagle-import") (part "PERF_2.54"))
    )
    (comp (ref "P154")
      (value "PERF_2.54")
      (footprint "eagle-import:PERF_2.54")
      (libsource (lib "eagle-import") (part "PERF_2.54"))
    )
    (comp (ref "P155")
      (value "PERF_2.54")
      (footprint "eagle-import:PERF_2.54")
      (libsource (lib "eagle-import") (part "PERF_2.54"))
    )
    (comp (ref "P156")
      (value "PERF_2.54")
      (footprint "eagle-import:PERF_2.54")
      (libsource (lib "eagle-import") (part "PERF_2.54"))
    )
    (comp (ref "P157")
      (value "PERF_2.54")
      (footprint "eagle-import:PERF_2.54")
      (libsource (lib "eagle-import") (part "PERF_2.54"))
    )
    (comp (ref "P158")
      (value "PERF_2.54")
      (footprint "eagle-import:PERF_2.54")
      (libsource (lib "eagle-import") (part "PERF_2.54"))
    )
    (comp (ref "P159")
      (value "PERF_2.54")
      (footprint "eagle-import:PERF_2.54")
      (libsource (lib "eagle-import") (part "PERF_2.54"))
    )
    (comp (ref "P160")
      (value "PERF_2.54")
      (footprint "eagle-import:PERF_2.54")
      (libsource (lib "eagle-import") (part "PERF_2.54"))
    )
    (comp (ref "P161")
      (value "PERF_2.54")
      (footprint "eagle-import:PERF_2.54")
      (libsource (lib "eagle-import") (part "PERF_2.54"))
    )
    (comp (ref "P162")
      (value "PERF_2.54")
      (footprint "eagle-import:PERF_2.54")
      (libsource (lib "eagle-import") (part "PERF_2.54"))
    )
    (comp (ref "P163")
      (value "PERF_2.54")
      (footprint "eagle-import:PERF_2.54")
      (libsource (lib "eagle-import") (part "PERF_2.54"))
    )
    (comp (ref "P164")
      (value "PERF_2.54")
      (footprint "eagle-import:PERF_2.54")
      (libsource (lib "eagle-import") (part "PERF_2.54"))
    )
    (comp (ref "P165")
      (value "PERF_2.54")
      (footprint "eagle-import:PERF_2.54")
      (libsource (lib "eagle-import") (part "PERF_2.54"))
    )
    (comp (ref "P166")
      (value "PERF_2.54")
      (footprint "eagle-import:PERF_2.54")
      (libsource (lib "eagle-import") (part "PERF_2.54"))
    )
    (comp (ref "P167")
      (value "PERF_2.54")
      (footprint "eagle-import:PERF_2.54")
      (libsource (lib "eagle-import") (part "PERF_2.54"))
    )
    (comp (ref "P168")
      (value "PERF_2.54")
      (footprint "eagle-import:PERF_2.54")
      (libsource (lib "eagle-import") (part "PERF_2.54"))
    )
    (comp (ref "P169")
      (value "PERF_2.54")
      (footprint "eagle-import:PERF_2.54")
      (libsource (lib "eagle-import") (part "PERF_2.54"))
    )
    (comp (ref "P170")
      (value "PERF_2.54")
      (footprint "eagle-import:PERF_2.54")
      (libsource (lib "eagle-import") (part "PERF_2.54"))
    )
    (comp (ref "P171")
      (value "PERF_2.54")
      (footprint "eagle-import:PERF_2.54")
      (libsource (lib "eagle-import") (part "PERF_2.54"))
    )
    (comp (ref "P172")
      (value "PERF_2.54")
      (footprint "eagle-import:PERF_2.54")
      (libsource (lib "eagle-import") (part "PERF_2.54"))
    )
    (comp (ref "P173")
      (value "PERF_2.54")
      (footprint "eagle-import:PERF_2.54")
      (libsource (lib "eagle-import") (part "PERF_2.54"))
    )
    (comp (ref "P174")
      (value "PERF_2.54")
      (footprint "eagle-import:PERF_2.54")
      (libsource (lib "eagle-import") (part "PERF_2.54"))
    )
    (comp (ref "P175")
      (value "PERF_2.54")
      (footprint "eagle-import:PERF_2.54")
      (libsource (lib "eagle-import") (part "PERF_2.54"))
    )
    (comp (ref "P176")
      (value "PERF_2.54")
      (footprint "eagle-import:PERF_2.54")
      (libsource (lib "eagle-import") (part "PERF_2.54"))
    )
    (comp (ref "P177")
      (value "PERF_2.54")
      (footprint "eagle-import:PERF_2.54")
      (libsource (lib "eagle-import") (part "PERF_2.54"))
    )
    (comp (ref "P178")
      (value "PERF_2.54")
      (footprint "eagle-import:PERF_2.54")
      (libsource (lib "eagle-import") (part "PERF_2.54"))
    )
    (comp (ref "P179")
      (value "PERF_2.54")
      (footprint "eagle-import:PERF_2.54")
      (libsource (lib "eagle-import") (part "PERF_2.54"))
    )
    (comp (ref "P180")
      (value "PERF_2.54")
      (footprint "eagle-import:PERF_2.54")
      (libsource (lib "eagle-import") (part "PERF_2.54"))
    )
    (comp (ref "P181")
      (value "PERF_2.54")
      (footprint "eagle-import:PERF_2.54")
      (libsource (lib "eagle-import") (part "PERF_2.54"))
    )
    (comp (ref "P182")
      (value "PERF_2.54")
      (footprint "eagle-import:PERF_2.54")
      (libsource (lib "eagle-import") (part "PERF_2.54"))
    )
    (comp (ref "P183")
      (value "PERF_2.54")
      (footprint "eagle-import:PERF_2.54")
      (libsource (lib "eagle-import") (part "PERF_2.54"))
    )
    (comp (ref "P184")
      (value "PERF_2.54")
      (footprint "eagle-import:PERF_2.54")
      (libsource (lib "eagle-import") (part "PERF_2.54"))
    )
    (comp (ref "P185")
      (value "PERF_2.54")
      (footprint "eagle-import:PERF_2.54")
      (libsource (lib "eagle-import") (part "PERF_2.54"))
    )
    (comp (ref "P186")
      (value "PERF_2.54")
      (footprint "eagle-import:PERF_2.54")
      (libsource (lib "eagle-import") (part "PERF_2.54"))
    )
    (comp (ref "P187")
      (value "PERF_2.54")
      (footprint "eagle-import:PERF_2.54")
      (libsource (lib "eagle-import") (part "PERF_2.54"))
    )
    (comp (ref "P188")
      (value "PERF_2.54")
      (footprint "eagle-import:PERF_2.54")
      (libsource (lib "eagle-import") (part "PERF_2.54"))
    )
    (comp (ref "P189")
      (value "PERF_2.54")
      (footprint "eagle-import:PERF_2.54")
      (libsource (lib "eagle-import") (part "PERF_2.54"))
    )
    (comp (ref "P190")
      (value "PERF_2.54")
      (footprint "eagle-import:PERF_2.54")
      (libsource (lib "eagle-import") (part "PERF_2.54"))
    )
    (comp (ref "P191")
      (value "PERF_2.54")
      (footprint "eagle-import:PERF_2.54")
      (libsource (lib "eagle-import") (part "PERF_2.54"))
    )
    (comp (ref "P192")
      (value "PERF_2.54")
      (footprint "eagle-import:PERF_2.54")
      (libsource (lib "eagle-import") (part "PERF_2.54"))
    )
    (comp (ref "P193")
      (value "PERF_2.54")
      (footprint "eagle-import:PERF_2.54")
      (libsource (lib "eagle-import") (part "PERF_2.54"))
    )
    (comp (ref "P194")
      (value "PERF_2.54")
      (footprint "eagle-import:PERF_2.54")
      (libsource (lib "eagle-import") (part "PERF_2.54"))
    )
    (comp (ref "P195")
      (value "PERF_2.54")
      (footprint "eagle-import:PERF_2.54")
      (libsource (lib "eagle-import") (part "PERF_2.54"))
    )
    (comp (ref "P196")
      (value "PERF_2.54")
      (footprint "eagle-import:PERF_2.54")
      (libsource (lib "eagle-import") (part "PERF_2.54"))
    )
    (comp (ref "P197")
      (value "PERF_2.54")
      (footprint "eagle-import:PERF_2.54")
      (libsource (lib "eagle-import") (part "PERF_2.54"))
    )
    (comp (ref "P198")
      (value "PERF_2.54")
      (footprint "eagle-import:PERF_2.54")
      (libsource (lib "eagle-import") (part "PERF_2.54"))
    )
    (comp (ref "P199")
      (value "PERF_2.54")
      (footprint "eagle-import:PERF_2.54")
      (libsource (lib "eagle-import") (part "PERF_2.54"))
    )
    (comp (ref "P200")
      (value "PERF_2.54")
      (footprint "eagle-import:PERF_2.54")
      (libsource (lib "eagle-import") (part "PERF_2.54"))
    )
    (comp (ref "P201")
      (value "PERF_2.54")
      (footprint "eagle-import:PERF_2.54")
      (libsource (lib "eagle-import") (part "PERF_2.54"))
    )
    (comp (ref "P202")
      (value "PERF_2.54")
      (footprint "eagle-import:PERF_2.54")
      (libsource (lib "eagle-import") (part "PERF_2.54"))
    )
    (comp (ref "P203")
      (value "PERF_2.54")
      (footprint "eagle-import:PERF_2.54")
      (libsource (lib "eagle-import") (part "PERF_2.54"))
    )
    (comp (ref "P204")
      (value "PERF_2.54")
      (footprint "eagle-import:PERF_2.54")
      (libsource (lib "eagle-import") (part "PERF_2.54"))
    )
    (comp (ref "P205")
      (value "PERF_2.54")
      (footprint "eagle-import:PERF_2.54")
      (libsource (lib "eagle-import") (part "PERF_2.54"))
    )
    (comp (ref "P206")
      (value "PERF_2.54")
      (footprint "eagle-import:PERF_2.54")
      (libsource (lib "eagle-import") (part "PERF_2.54"))
    )
    (comp (ref "P207")
      (value "PERF_2.54")
      (footprint "eagle-import:PERF_2.54")
      (libsource (lib "eagle-import") (part "PERF_2.54"))
    )
    (comp (ref "P208")
      (value "PERF_2.54")
      (footprint "eagle-import:PERF_2.54")
      (libsource (lib "eagle-import") (part "PERF_2.54"))
    )
    (comp (ref "P209")
      (value "PERF_2.54")
      (footprint "eagle-import:PERF_2.54")
      (libsource (lib "eagle-import") (part "PERF_2.54"))
    )
    (comp (ref "P210")
      (value "PERF_2.54")
      (footprint "eagle-import:PERF_2.54")
      (libsource (lib "eagle-import") (part "PERF_2.54"))
    )
    (comp (ref "P211")
      (value "PERF_2.54")
      (footprint "eagle-import:PERF_2.54")
      (libsource (lib "eagle-import") (part "PERF_2.54"))
    )
    (comp (ref "P212")
      (value "PERF_2.54")
      (footprint "eagle-import:PERF_2.54")
      (libsource (lib "eagle-import") (part "PERF_2.54"))
    )
    (comp (ref "P213")
      (value "PERF_2.54")
      (footprint "eagle-import:PERF_2.54")
      (libsource (lib "eagle-import") (part "PERF_2.54"))
    )
    (comp (ref "P214")
      (value "PERF_2.54")
      (footprint "eagle-import:PERF_2.54")
      (libsource (lib "eagle-import") (part "PERF_2.54"))
    )
    (comp (ref "P215")
      (value "PERF_2.54")
      (footprint "eagle-import:PERF_2.54")
      (libsource (lib "eagle-import") (part "PERF_2.54"))
    )
    (comp (ref "P216")
      (value "PERF_2.54")
      (footprint "eagle-import:PERF_2.54")
      (libsource (lib "eagle-import") (part "PERF_2.54"))
    )
    (comp (ref "P217")
      (value "PERF_2.54")
      (footprint "eagle-import:PERF_2.54")
      (libsource (lib "eagle-import") (part "PERF_2.54"))
    )
    (comp (ref "P218")
      (value "PERF_2.54")
      (footprint "eagle-import:PERF_2.54")
      (libsource (lib "eagle-import") (part "PERF_2.54"))
    )
    (comp (ref "P219")
      (value "PERF_2.54")
      (footprint "eagle-import:PERF_2.54")
      (libsource (lib "eagle-import") (part "PERF_2.54"))
    )
    (comp (ref "P220")
      (value "PERF_2.54")
      (footprint "eagle-import:PERF_2.54")
      (libsource (lib "eagle-import") (part "PERF_2.54"))
    )
    (comp (ref "P221")
      (value "PERF_2.54")
      (footprint "eagle-import:PERF_2.54")
      (libsource (lib "eagle-import") (part "PERF_2.54"))
    )
    (comp (ref "P222")
      (value "PERF_2.54")
      (footprint "eagle-import:PERF_2.54")
      (libsource (lib "eagle-import") (part "PERF_2.54"))
    )
    (comp (ref "P223")
      (value "PERF_2.54")
      (footprint "eagle-import:PERF_2.54")
      (libsource (lib "eagle-import") (part "PERF_2.54"))
    )
    (comp (ref "P224")
      (value "PERF_2.54")
      (footprint "eagle-import:PERF_2.54")
      (libsource (lib "eagle-import") (part "PERF_2.54"))
    )
    (comp (ref "P225")
      (value "PERF_2.54")
      (footprint "eagle-import:PERF_2.54")
      (libsource (lib "eagle-import") (part "PERF_2.54"))
    )
    (comp (ref "P226")
      (value "PERF_2.54")
      (footprint "eagle-import:PERF_2.54")
      (libsource (lib "eagle-import") (part "PERF_2.54"))
    )
    (comp (ref "P227")
      (value "PERF_2.54")
      (footprint "eagle-import:PERF_2.54")
      (libsource (lib "eagle-import") (part "PERF_2.54"))
    )
    (comp (ref "P228")
      (value "PERF_2.54")
      (footprint "eagle-import:PERF_2.54")
      (libsource (lib "eagle-import") (part "PERF_2.54"))
    )
    (comp (ref "P229")
      (value "PERF_2.54")
      (footprint "eagle-import:PERF_2.54")
      (libsource (lib "eagle-import") (part "PERF_2.54"))
    )
    (comp (ref "P230")
      (value "PERF_2.54")
      (footprint "eagle-import:PERF_2.54")
      (libsource (lib "eagle-import") (part "PERF_2.54"))
    )
    (comp (ref "P231")
      (value "PERF_2.54")
      (footprint "eagle-import:PERF_2.54")
      (libsource (lib "eagle-import") (part "PERF_2.54"))
    )
    (comp (ref "P232")
      (value "PERF_2.54")
      (footprint "eagle-import:PERF_2.54")
      (libsource (lib "eagle-import") (part "PERF_2.54"))
    )
    (comp (ref "P233")
      (value "PERF_2.54")
      (footprint "eagle-import:PERF_2.54")
      (libsource (lib "eagle-import") (part "PERF_2.54"))
    )
    (comp (ref "P234")
      (value "PERF_2.54")
      (footprint "eagle-import:PERF_2.54")
      (libsource (lib "eagle-import") (part "PERF_2.54"))
    )
    (comp (ref "P235")
      (value "PERF_2.54")
      (footprint "eagle-import:PERF_2.54")
      (libsource (lib "eagle-import") (part "PERF_2.54"))
    )
    (comp (ref "P236")
      (value "PERF_2.54")
      (footprint "eagle-import:PERF_2.54")
      (libsource (lib "eagle-import") (part "PERF_2.54"))
    )
    (comp (ref "P237")
      (value "PERF_2.54")
      (footprint "eagle-import:PERF_2.54")
      (libsource (lib "eagle-import") (part "PERF_2.54"))
    )
    (comp (ref "P238")
      (value "PERF_2.54")
      (footprint "eagle-import:PERF_2.54")
      (libsource (lib "eagle-import") (part "PERF_2.54"))
    )
    (comp (ref "P239")
      (value "PERF_2.54")
      (footprint "eagle-import:PERF_2.54")
      (libsource (lib "eagle-import") (part "PERF_2.54"))
    )
    (comp (ref "P240")
      (value "PERF_2.54")
      (footprint "eagle-import:PERF_2.54")
      (libsource (lib "eagle-import") (part "PERF_2.54"))
    )
    (comp (ref "P241")
      (value "PERF_2.54")
      (footprint "eagle-import:PERF_2.54")
      (libsource (lib "eagle-import") (part "PERF_2.54"))
    )
    (comp (ref "P242")
      (value "PERF_2.54")
      (footprint "eagle-import:PERF_2.54")
      (libsource (lib "eagle-import") (part "PERF_2.54"))
    )
    (comp (ref "P243")
      (value "PERF_2.54")
      (footprint "eagle-import:PERF_2.54")
      (libsource (lib "eagle-import") (part "PERF_2.54"))
    )
    (comp (ref "P244")
      (value "PERF_2.54")
      (footprint "eagle-import:PERF_2.54")
      (libsource (lib "eagle-import") (part "PERF_2.54"))
    )
    (comp (ref "P245")
      (value "PERF_2.54")
      (footprint "eagle-import:PERF_2.54")
      (libsource (lib "eagle-import") (part "PERF_2.54"))
    )
    (comp (ref "P246")
      (value "PERF_2.54")
      (footprint "eagle-import:PERF_2.54")
      (libsource (lib "eagle-import") (part "PERF_2.54"))
    )
    (comp (ref "P247")
      (value "PERF_2.54")
      (footprint "eagle-import:PERF_2.54")
      (libsource (lib "eagle-import") (part "PERF_2.54"))
    )
    (comp (ref "P248")
      (value "PERF_2.54")
      (footprint "eagle-import:PERF_2.54")
      (libsource (lib "eagle-import") (part "PERF_2.54"))
    )
    (comp (ref "P249")
      (value "PERF_2.54")
      (footprint "eagle-import:PERF_2.54")
      (libsource (lib "eagle-import") (part "PERF_2.54"))
    )
    (comp (ref "P250")
      (value "PERF_2.54")
      (footprint "eagle-import:PERF_2.54")
      (libsource (lib "eagle-import") (part "PERF_2.54"))
    )
    (comp (ref "P251")
      (value "PERF_2.54")
      (footprint "eagle-import:PERF_2.54")
      (libsource (lib "eagle-import") (part "PERF_2.54"))
    )
    (comp (ref "P252")
      (value "PERF_2.54")
      (footprint "eagle-import:PERF_2.54")
      (libsource (lib "eagle-import") (part "PERF_2.54"))
    )
    (comp (ref "P253")
      (value "PERF_2.54")
      (footprint "eagle-import:PERF_2.54")
      (libsource (lib "eagle-import") (part "PERF_2.54"))
    )
    (comp (ref "P254")
      (value "PERF_2.54")
      (footprint "eagle-import:PERF_2.54")
      (libsource (lib "eagle-import") (part "PERF_2.54"))
    )
    (comp (ref "P255")
      (value "PERF_2.54")
      (footprint "eagle-import:PERF_2.54")
      (libsource (lib "eagle-import") (part "PERF_2.54"))
    )
    (comp (ref "P256")
      (value "PERF_2.54")
      (footprint "eagle-import:PERF_2.54")
      (libsource (lib "eagle-import") (part "PERF_2.54"))
    )
    (comp (ref "P257")
      (value "PERF_2.54")
      (footprint "eagle-import:PERF_2.54")
      (libsource (lib "eagle-import") (part "PERF_2.54"))
    )
    (comp (ref "P258")
      (value "PERF_2.54")
      (footprint "eagle-import:PERF_2.54")
      (libsource (lib "eagle-import") (part "PERF_2.54"))
    )
    (comp (ref "P259")
      (value "PERF_2.54")
      (footprint "eagle-import:PERF_2.54")
      (libsource (lib "eagle-import") (part "PERF_2.54"))
    )
    (comp (ref "P260")
      (value "PERF_2.54")
      (footprint "eagle-import:PERF_2.54")
      (libsource (lib "eagle-import") (part "PERF_2.54"))
    )
    (comp (ref "P261")
      (value "PERF_2.54")
      (footprint "eagle-import:PERF_2.54")
      (libsource (lib "eagle-import") (part "PERF_2.54"))
    )
    (comp (ref "P262")
      (value "PERF_2.54")
      (footprint "eagle-import:PERF_2.54")
      (libsource (lib "eagle-import") (part "PERF_2.54"))
    )
    (comp (ref "P263")
      (value "PERF_2.54")
      (footprint "eagle-import:PERF_2.54")
      (libsource (lib "eagle-import") (part "PERF_2.54"))
    )
    (comp (ref "P264")
      (value "PERF_2.54")
      (footprint "eagle-import:PERF_2.54")
      (libsource (lib "eagle-import") (part "PERF_2.54"))
    )
    (comp (ref "P265")
      (value "PERF_2.54")
      (footprint "eagle-import:PERF_2.54")
      (libsource (lib "eagle-import") (part "PERF_2.54"))
    )
    (comp (ref "P266")
      (value "PERF_2.54")
      (footprint "eagle-import:PERF_2.54")
      (libsource (lib "eagle-import") (part "PERF_2.54"))
    )
    (comp (ref "P267")
      (value "PERF_2.54")
      (footprint "eagle-import:PERF_2.54")
      (libsource (lib "eagle-import") (part "PERF_2.54"))
    )
    (comp (ref "P268")
      (value "PERF_2.54")
      (footprint "eagle-import:PERF_2.54")
      (libsource (lib "eagle-import") (part "PERF_2.54"))
    )
    (comp (ref "P269")
      (value "PERF_2.54")
      (footprint "eagle-import:PERF_2.54")
      (libsource (lib "eagle-import") (part "PERF_2.54"))
    )
    (comp (ref "P270")
      (value "PERF_2.54")
      (footprint "eagle-import:PERF_2.54")
      (libsource (lib "eagle-import") (part "PERF_2.54"))
    )
    (comp (ref "P271")
      (value "PERF_2.54")
      (footprint "eagle-import:PERF_2.54")
      (libsource (lib "eagle-import") (part "PERF_2.54"))
    )
    (comp (ref "P272")
      (value "PERF_2.54")
      (footprint "eagle-import:PERF_2.54")
      (libsource (lib "eagle-import") (part "PERF_2.54"))
    )
    (comp (ref "P273")
      (value "PERF_2.54")
      (footprint "eagle-import:PERF_2.54")
      (libsource (lib "eagle-import") (part "PERF_2.54"))
    )
    (comp (ref "P274")
      (value "PERF_2.54")
      (footprint "eagle-import:PERF_2.54")
      (libsource (lib "eagle-import") (part "PERF_2.54"))
    )
    (comp (ref "P275")
      (value "PERF_2.54")
      (footprint "eagle-import:PERF_2.54")
      (libsource (lib "eagle-import") (part "PERF_2.54"))
    )
    (comp (ref "P276")
      (value "PERF_2.54")
      (footprint "eagle-import:PERF_2.54")
      (libsource (lib "eagle-import") (part "PERF_2.54"))
    )
    (comp (ref "P277")
      (value "PERF_2.54")
      (footprint "eagle-import:PERF_2.54")
      (libsource (lib "eagle-import") (part "PERF_2.54"))
    )
    (comp (ref "P278")
      (value "PERF_2.54")
      (footprint "eagle-import:PERF_2.54")
      (libsource (lib "eagle-import") (part "PERF_2.54"))
    )
    (comp (ref "P279")
      (value "PERF_2.54")
      (footprint "eagle-import:PERF_2.54")
      (libsource (lib "eagle-import") (part "PERF_2.54"))
    )
    (comp (ref "P280")
      (value "PERF_2.54")
      (footprint "eagle-import:PERF_2.54")
      (libsource (lib "eagle-import") (part "PERF_2.54"))
    )
    (comp (ref "P281")
      (value "PERF_2.54")
      (footprint "eagle-import:PERF_2.54")
      (libsource (lib "eagle-import") (part "PERF_2.54"))
    )
    (comp (ref "P282")
      (value "PERF_2.54")
      (footprint "eagle-import:PERF_2.54")
      (libsource (lib "eagle-import") (part "PERF_2.54"))
    )
    (comp (ref "P283")
      (value "PERF_2.54")
      (footprint "eagle-import:PERF_2.54")
      (libsource (lib "eagle-import") (part "PERF_2.54"))
    )
    (comp (ref "P284")
      (value "PERF_2.54")
      (footprint "eagle-import:PERF_2.54")
      (libsource (lib "eagle-import") (part "PERF_2.54"))
    )
    (comp (ref "P285")
      (value "PERF_2.54")
      (footprint "eagle-import:PERF_2.54")
      (libsource (lib "eagle-import") (part "PERF_2.54"))
    )
    (comp (ref "P286")
      (value "PERF_2.54")
      (footprint "eagle-import:PERF_2.54")
      (libsource (lib "eagle-import") (part "PERF_2.54"))
    )
    (comp (ref "P287")
      (value "PERF_2.54")
      (footprint "eagle-import:PERF_2.54")
      (libsource (lib "eagle-import") (part "PERF_2.54"))
    )
    (comp (ref "P288")
      (value "PERF_2.54")
      (footprint "eagle-import:PERF_2.54")
      (libsource (lib "eagle-import") (part "PERF_2.54"))
    )
    (comp (ref "P289")
      (value "PERF_2.54")
      (footprint "eagle-import:PERF_2.54")
      (libsource (lib "eagle-import") (part "PERF_2.54"))
    )
    (comp (ref "P290")
      (value "PERF_2.54")
      (footprint "eagle-import:PERF_2.54")
      (libsource (lib "eagle-import") (part "PERF_2.54"))
    )
    (comp (ref "P291")
      (value "PERF_2.54")
      (footprint "eagle-import:PERF_2.54")
      (libsource (lib "eagle-import") (part "PERF_2.54"))
    )
    (comp (ref "P292")
      (value "PERF_2.54")
      (footprint "eagle-import:PERF_2.54")
      (libsource (lib "eagle-import") (part "PERF_2.54"))
    )
    (comp (ref "P293")
      (value "PERF_2.54")
      (footprint "eagle-import:PERF_2.54")
      (libsource (lib "eagle-import") (part "PERF_2.54"))
    )
    (comp (ref "P294")
      (value "PERF_2.54")
      (footprint "eagle-import:PERF_2.54")
      (libsource (lib "eagle-import") (part "PERF_2.54"))
    )
    (comp (ref "P295")
      (value "PERF_2.54")
      (footprint "eagle-import:PERF_2.54")
      (libsource (lib "eagle-import") (part "PERF_2.54"))
    )
    (comp (ref "P296")
      (value "PERF_2.54")
      (footprint "eagle-import:PERF_2.54")
      (libsource (lib "eagle-import") (part "PERF_2.54"))
    )
    (comp (ref "P297")
      (value "PERF_2.54")
      (footprint "eagle-import:PERF_2.54")
      (libsource (lib "eagle-import") (part "PERF_2.54"))
    )
    (comp (ref "P298")
      (value "PERF_2.54")
      (footprint "eagle-import:PERF_2.54")
      (libsource (lib "eagle-import") (part "PERF_2.54"))
    )
    (comp (ref "P299")
      (value "PERF_2.54")
      (footprint "eagle-import:PERF_2.54")
      (libsource (lib "eagle-import") (part "PERF_2.54"))
    )
    (comp (ref "P300")
      (value "PERF_2.54")
      (footprint "eagle-import:PERF_2.54")
      (libsource (lib "eagle-import") (part "PERF_2.54"))
    )
    (comp (ref "P301")
      (value "PERF_2.54")
      (footprint "eagle-import:PERF_2.54")
      (libsource (lib "eagle-import") (part "PERF_2.54"))
    )
    (comp (ref "P302")
      (value "PERF_2.54")
      (footprint "eagle-import:PERF_2.54")
      (libsource (lib "eagle-import") (part "PERF_2.54"))
    )
    (comp (ref "P303")
      (value "PERF_2.54")
      (footprint "eagle-import:PERF_2.54")
      (libsource (lib "eagle-import") (part "PERF_2.54"))
    )
    (comp (ref "P304")
      (value "PERF_2.54")
      (footprint "eagle-import:PERF_2.54")
      (libsource (lib "eagle-import") (part "PERF_2.54"))
    )
    (comp (ref "P305")
      (value "PERF_2.54")
      (footprint "eagle-import:PERF_2.54")
      (libsource (lib "eagle-import") (part "PERF_2.54"))
    )
    (comp (ref "P306")
      (value "PERF_2.54")
      (footprint "eagle-import:PERF_2.54")
      (libsource (lib "eagle-import") (part "PERF_2.54"))
    )
    (comp (ref "P307")
      (value "PERF_2.54")
      (footprint "eagle-import:PERF_2.54")
      (libsource (lib "eagle-import") (part "PERF_2.54"))
    )
    (comp (ref "P308")
      (value "PERF_2.54")
      (footprint "eagle-import:PERF_2.54")
      (libsource (lib "eagle-import") (part "PERF_2.54"))
    )
    (comp (ref "P309")
      (value "PERF_2.54")
      (footprint "eagle-import:PERF_2.54")
      (libsource (lib "eagle-import") (part "PERF_2.54"))
    )
    (comp (ref "P310")
      (value "PERF_2.54")
      (footprint "eagle-import:PERF_2.54")
      (libsource (lib "eagle-import") (part "PERF_2.54"))
    )
    (comp (ref "P311")
      (value "PERF_2.54")
      (footprint "eagle-import:PERF_2.54")
      (libsource (lib "eagle-import") (part "PERF_2.54"))
    )
    (comp (ref "P312")
      (value "PERF_2.54")
      (footprint "eagle-import:PERF_2.54")
      (libsource (lib "eagle-import") (part "PERF_2.54"))
    )
    (comp (ref "P313")
      (value "PERF_2.54")
      (footprint "eagle-import:PERF_2.54")
      (libsource (lib "eagle-import") (part "PERF_2.54"))
    )
    (comp (ref "P314")
      (value "PERF_2.54")
      (footprint "eagle-import:PERF_2.54")
      (libsource (lib "eagle-import") (part "PERF_2.54"))
    )
    (comp (ref "P315")
      (value "PERF_2.54")
      (footprint "eagle-import:PERF_2.54")
      (libsource (lib "eagle-import") (part "PERF_2.54"))
    )
    (comp (ref "BOOT")
      (value "WIREPAD1,6/0,9")
      (footprint "eagle-import:1,6_0,9")
      (libsource (lib "eagle-import") (part "WIREPAD1,6/0,9"))
    )
    (comp (ref "C21")
      (value "0.1u")
      (footprint "eagle-import:C0603")
      (libsource (lib "eagle-import") (part "C-EUC0603"))
    )
    (comp (ref "C22")
      (value "0.1u")
      (footprint "eagle-import:C0603")
      (libsource (lib "eagle-import") (part "C-EUC0603"))
    )
    (comp (ref "C23")
      (value "0.1u")
      (footprint "eagle-import:C0603")
      (libsource (lib "eagle-import") (part "C-EUC0603"))
    )
    (comp (ref "C24")
      (value "0.1u")
      (footprint "eagle-import:C0603")
      (libsource (lib "eagle-import") (part "C-EUC0603"))
    )
    (comp (ref "C25")
      (value "18p")
      (footprint "eagle-import:C0603")
      (libsource (lib "eagle-import") (part "C-EUC0603"))
    )
    (comp (ref "C26")
      (value "18p")
      (footprint "eagle-import:C0603")
      (libsource (lib "eagle-import") (part "C-EUC0603"))
    )
    (comp (ref "C27")
      (value "2.2u")
      (footprint "eagle-import:C0805")
      (libsource (lib "eagle-import") (part "C-EUC0805"))
    )
    (comp (ref "C28")
      (value "2.2u")
      (footprint "eagle-import:C0805")
      (libsource (lib "eagle-import") (part "C-EUC0805"))
    )
    (comp (ref "C29")
      (value "0.1u")
      (footprint "eagle-import:C0603")
      (libsource (lib "eagle-import") (part "C-EUC0603"))
    )
    (comp (ref "C30")
      (value "0.1u")
      (footprint "eagle-import:C0603")
      (libsource (lib "eagle-import") (part "C-EUC0603"))
    )
    (comp (ref "C31")
      (value "0.1u")
      (footprint "eagle-import:C0603")
      (libsource (lib "eagle-import") (part "C-EUC0603"))
    )
    (comp (ref "C32")
      (value "0.1u")
      (footprint "eagle-import:C0603")
      (libsource (lib "eagle-import") (part "C-EUC0603"))
    )
    (comp (ref "C33")
      (value "0.1u")
      (footprint "eagle-import:C0603")
      (libsource (lib "eagle-import") (part "C-EUC0603"))
    )
    (comp (ref "C52")
      (value "DNP")
      (footprint "eagle-import:C0603")
      (libsource (lib "eagle-import") (part "C-EUC0603"))
    )
    (comp (ref "C53")
      (value "DNP")
      (footprint "eagle-import:C0603")
      (libsource (lib "eagle-import") (part "C-EUC0603"))
    )
    (comp (ref "C54")
      (value "DNP")
      (footprint "eagle-import:C0603")
      (libsource (lib "eagle-import") (part "C-EUC0603"))
    )
    (comp (ref "C55")
      (value "DNP")
      (footprint "eagle-import:C0603")
      (libsource (lib "eagle-import") (part "C-EUC0603"))
    )
    (comp (ref "C56")
      (value "DNP")
      (footprint "eagle-import:C0603")
      (libsource (lib "eagle-import") (part "C-EUC0603"))
    )
    (comp (ref "D1")
      (value "DIODE-SOD123")
      (footprint "eagle-import:SOD123")
      (libsource (lib "eagle-import") (part "DIODE-SOD123"))
    )
    (comp (ref "D2")
      (value "DIODE-SOD123")
      (footprint "eagle-import:SOD123")
      (libsource (lib "eagle-import") (part "DIODE-SOD123"))
    )
    (comp (ref "D3")
      (value "DIODE-SOD123")
      (footprint "eagle-import:SOD123")
      (libsource (lib "eagle-import") (part "DIODE-SOD123"))
    )
    (comp (ref "D4")
      (value "DIODE-SOD123")
      (footprint "eagle-import:SOD123")
      (libsource (lib "eagle-import") (part "DIODE-SOD123"))
    )
    (comp (ref "D5")
      (value "DIODE-SOD123")
      (footprint "eagle-import:SOD123")
      (libsource (lib "eagle-import") (part "DIODE-SOD123"))
    )
    (comp (ref "D6")
      (value "DIODE-SOD123")
      (footprint "eagle-import:SOD123")
      (libsource (lib "eagle-import") (part "DIODE-SOD123"))
    )
    (comp (ref "D7")
      (value "DIODE-SOD123")
      (footprint "eagle-import:SOD123")
      (libsource (lib "eagle-import") (part "DIODE-SOD123"))
    )
    (comp (ref "D8")
      (value "DIODE-SOD123")
      (footprint "eagle-import:SOD123")
      (libsource (lib "eagle-import") (part "DIODE-SOD123"))
    )
    (comp (ref "D9")
      (value "DIODE-SOD123")
      (footprint "eagle-import:SOD123")
      (libsource (lib "eagle-import") (part "DIODE-SOD123"))
    )
    (comp (ref "D10")
      (value "DIODE-SOD123")
      (footprint "eagle-import:SOD123")
      (libsource (lib "eagle-import") (part "DIODE-SOD123"))
    )
    (comp (ref "D11")
      (value "DIODE-SOD123")
      (footprint "eagle-import:SOD123")
      (libsource (lib "eagle-import") (part "DIODE-SOD123"))
    )
    (comp (ref "D12")
      (value "DIODE-SOD123")
      (footprint "eagle-import:SOD123")
      (libsource (lib "eagle-import") (part "DIODE-SOD123"))
    )
    (comp (ref "D13")
      (value "DIODE-SOD123")
      (footprint "eagle-import:SOD123")
      (libsource (lib "eagle-import") (part "DIODE-SOD123"))
    )
    (comp (ref "D14")
      (value "DIODE-SOD123")
      (footprint "eagle-import:SOD123")
      (libsource (lib "eagle-import") (part "DIODE-SOD123"))
    )
    (comp (ref "D15")
      (value "DIODE-SOD123")
      (footprint "eagle-import:SOD123")
      (libsource (lib "eagle-import") (part "DIODE-SOD123"))
    )
    (comp (ref "D16")
      (value "DIODE-SOD123")
      (footprint "eagle-import:SOD123")
      (libsource (lib "eagle-import") (part "DIODE-SOD123"))
    )
    (comp (ref "D17")
      (value "DIODE-SOD123")
      (footprint "eagle-import:SOD123")
      (libsource (lib "eagle-import") (part "DIODE-SOD123"))
    )
    (comp (ref "DIS1")
      (value "OLED_130_SPI")
      (footprint "eagle-import:OLED_130_SPI")
      (libsource (lib "eagle-import") (part "OLED_130_SPI"))
    )
    (comp (ref "EN1")
      (value "PEC11L-4220F-S0015")
      (footprint "eagle-import:PEC11L-4220F-S0015")
      (fields
        (field (name "DIGIKEY_PARTNO") "PEC11L-4220F-S0015-ND")
        (field (name "MANUFACTURER") "Bourns Inc.")
        (field (name "CREATED_BY") "PCBLayout.com")
      )
      (libsource (lib "eagle-import") (part "PEC11L-4220F-S0015"))
    )
    (comp (ref "IC1")
      (value "STM32F722RET")
      (footprint "eagle-import:TQFP64")
      (libsource (lib "eagle-import") (part "STM32F722RET"))
    )
    (comp (ref "JP1")
      (value "PINHD-1X4")
      (footprint "eagle-import:1X04")
      (libsource (lib "eagle-import") (part "PINHD-1X4"))
    )
    (comp (ref "JP2")
      (value "PINHD-1X2")
      (footprint "eagle-import:1X02")
      (libsource (lib "eagle-import") (part "PINHD-1X2"))
    )
    (comp (ref "LED1")
      (value "W115WSURKMGKW")
      (footprint "eagle-import:W115WSURKMGKW")
      (libsource (lib "eagle-import") (part "W115WSURKMGKW"))
    )
    (comp (ref "LED2")
      (value "W115WSURKMGKW")
      (footprint "eagle-import:W115WSURKMGKW")
      (libsource (lib "eagle-import") (part "W115WSURKMGKW"))
    )
    (comp (ref "PA2")
      (value "WIREPAD1,6/0,9")
      (footprint "eagle-import:1,6_0,9")
      (libsource (lib "eagle-import") (part "WIREPAD1,6/0,9"))
    )
    (comp (ref "PA3")
      (value "WIREPAD1,6/0,9")
      (footprint "eagle-import:1,6_0,9")
      (libsource (lib "eagle-import") (part "WIREPAD1,6/0,9"))
    )
    (comp (ref "PC0")
      (value "WIREPAD1,6/0,9")
      (footprint "eagle-import:1,6_0,9")
      (libsource (lib "eagle-import") (part "WIREPAD1,6/0,9"))
    )
    (comp (ref "PC2")
      (value "WIREPAD1,6/0,9")
      (footprint "eagle-import:1,6_0,9")
      (libsource (lib "eagle-import") (part "WIREPAD1,6/0,9"))
    )
    (comp (ref "PC3")
      (value "WIREPAD1,6/0,9")
      (footprint "eagle-import:1,6_0,9")
      (libsource (lib "eagle-import") (part "WIREPAD1,6/0,9"))
    )
    (comp (ref "PC4")
      (value "WIREPAD1,6/0,9")
      (footprint "eagle-import:1,6_0,9")
      (libsource (lib "eagle-import") (part "WIREPAD1,6/0,9"))
    )
    (comp (ref "PC8")
      (value "WIREPAD1,6/0,9")
      (footprint "eagle-import:1,6_0,9")
      (libsource (lib "eagle-import") (part "WIREPAD1,6/0,9"))
    )
    (comp (ref "PC13")
      (value "WIREPAD1,6/0,9")
      (footprint "eagle-import:1,6_0,9")
      (libsource (lib "eagle-import") (part "WIREPAD1,6/0,9"))
    )
    (comp (ref "PC14")
      (value "WIREPAD1,6/0,9")
      (footprint "eagle-import:1,6_0,9")
      (libsource (lib "eagle-import") (part "WIREPAD1,6/0,9"))
    )
    (comp (ref "PC15")
      (value "WIREPAD1,6/0,9")
      (footprint "eagle-import:1,6_0,9")
      (libsource (lib "eagle-import") (part "WIREPAD1,6/0,9"))
    )
    (comp (ref "Q1")
      (value "24MHz")
      (footprint "eagle-import:HC49UP")
      (libsource (lib "eagle-import") (part "CRYSTALHC49UP"))
    )
    (comp (ref "R6")
      (value "100")
      (footprint "eagle-import:R0603")
      (libsource (lib "eagle-import") (part "R-EU_R0603"))
    )
    (comp (ref "R7")
      (value "100")
      (footprint "eagle-import:R0603")
      (libsource (lib "eagle-import") (part "R-EU_R0603"))
    )
    (comp (ref "R8")
      (value "100")
      (footprint "eagle-import:R0603")
      (libsource (lib "eagle-import") (part "R-EU_R0603"))
    )
    (comp (ref "R9")
      (value "100")
      (footprint "eagle-import:R0603")
      (libsource (lib "eagle-import") (part "R-EU_R0603"))
    )
    (comp (ref "R36")
      (value "1.5k")
      (footprint "eagle-import:R0603")
      (libsource (lib "eagle-import") (part "R-EU_R0603"))
    )
    (comp (ref "R37")
      (value "2.2k")
      (footprint "eagle-import:R0603")
      (libsource (lib "eagle-import") (part "R-EU_R0603"))
    )
    (comp (ref "R38")
      (value "1.5k")
      (footprint "eagle-import:R0603")
      (libsource (lib "eagle-import") (part "R-EU_R0603"))
    )
    (comp (ref "R39")
      (value "2.2k")
      (footprint "eagle-import:R0603")
      (libsource (lib "eagle-import") (part "R-EU_R0603"))
    )
    (comp (ref "SW1")
      (value "CHERRY_MX_LED_WITH_FIXING_PINS")
      (footprint "eagle-import:MX1A-XX[R_G_Y]W")
      (libsource (lib "eagle-import") (part "CHERRY_MX_LED_WITH_FIXING_PINS"))
    )
    (comp (ref "SW2")
      (value "CHERRY_MX_LED_WITH_FIXING_PINS")
      (footprint "eagle-import:MX1A-XX[R_G_Y]W")
      (libsource (lib "eagle-import") (part "CHERRY_MX_LED_WITH_FIXING_PINS"))
    )
    (comp (ref "SW3")
      (value "CHERRY_MX_LED_WITH_FIXING_PINS")
      (footprint "eagle-import:MX1A-XX[R_G_Y]W")
      (libsource (lib "eagle-import") (part "CHERRY_MX_LED_WITH_FIXING_PINS"))
    )
    (comp (ref "SW4")
      (value "CHERRY_MX_LED_WITH_FIXING_PINS")
      (footprint "eagle-import:MX1A-XX[R_G_Y]W")
      (libsource (lib "eagle-import") (part "CHERRY_MX_LED_WITH_FIXING_PINS"))
    )
    (comp (ref "SW5")
      (value "CHERRY_MX_LED_WITH_FIXING_PINS")
      (footprint "eagle-import:MX1A-XX[R_G_Y]W")
      (libsource (lib "eagle-import") (part "CHERRY_MX_LED_WITH_FIXING_PINS"))
    )
    (comp (ref "SW6")
      (value "CHERRY_MX_LED_WITH_FIXING_PINS")
      (footprint "eagle-import:MX1A-XX[R_G_Y]W")
      (libsource (lib "eagle-import") (part "CHERRY_MX_LED_WITH_FIXING_PINS"))
    )
    (comp (ref "SW7")
      (value "CHERRY_MX_LED_WITH_FIXING_PINS")
      (footprint "eagle-import:MX1A-XX[R_G_Y]W")
      (libsource (lib "eagle-import") (part "CHERRY_MX_LED_WITH_FIXING_PINS"))
    )
    (comp (ref "SW8")
      (value "CHERRY_MX_LED_WITH_FIXING_PINS")
      (footprint "eagle-import:MX1A-XX[R_G_Y]W")
      (libsource (lib "eagle-import") (part "CHERRY_MX_LED_WITH_FIXING_PINS"))
    )
    (comp (ref "SW9")
      (value "CHERRY_MX_LED_WITH_FIXING_PINS")
      (footprint "eagle-import:MX1A-XX[R_G_Y]W")
      (libsource (lib "eagle-import") (part "CHERRY_MX_LED_WITH_FIXING_PINS"))
    )
    (comp (ref "SW10")
      (value "CHERRY_MX_LED_WITH_FIXING_PINS")
      (footprint "eagle-import:MX1A-XX[R_G_Y]W")
      (libsource (lib "eagle-import") (part "CHERRY_MX_LED_WITH_FIXING_PINS"))
    )
    (comp (ref "SW11")
      (value "CHERRY_MX_LED_WITH_FIXING_PINS")
      (footprint "eagle-import:MX1A-XX[R_G_Y]W")
      (libsource (lib "eagle-import") (part "CHERRY_MX_LED_WITH_FIXING_PINS"))
    )
    (comp (ref "SW12")
      (value "CHERRY_MX_LED_WITH_FIXING_PINS")
      (footprint "eagle-import:MX1A-XX[R_G_Y]W")
      (libsource (lib "eagle-import") (part "CHERRY_MX_LED_WITH_FIXING_PINS"))
    )
    (comp (ref "SW13")
      (value "CHERRY_MX_LED_WITH_FIXING_PINS")
      (footprint "eagle-import:MX1A-XX[R_G_Y]W")
      (libsource (lib "eagle-import") (part "CHERRY_MX_LED_WITH_FIXING_PINS"))
    )
    (comp (ref "SW14")
      (value "CHERRY_MX_LED_WITH_FIXING_PINS")
      (footprint "eagle-import:MX1A-XX[R_G_Y]W")
      (libsource (lib "eagle-import") (part "CHERRY_MX_LED_WITH_FIXING_PINS"))
    )
    (comp (ref "SW15")
      (value "CHERRY_MX_LED_WITH_FIXING_PINS")
      (footprint "eagle-import:MX1A-XX[R_G_Y]W")
      (libsource (lib "eagle-import") (part "CHERRY_MX_LED_WITH_FIXING_PINS"))
    )
    (comp (ref "SW16")
      (value "CHERRY_MX_LED_WITH_FIXING_PINS")
      (footprint "eagle-import:MX1A-XX[R_G_Y]W")
      (libsource (lib "eagle-import") (part "CHERRY_MX_LED_WITH_FIXING_PINS"))
    )
    (comp (ref "SW17")
      (value "CHERRY_MX_LED_WITH_FIXING_PINS")
      (footprint "eagle-import:MX1A-XX[R_G_Y]W")
      (libsource (lib "eagle-import") (part "CHERRY_MX_LED_WITH_FIXING_PINS"))
    )
    (comp (ref "SW18")
      (value "TACT_TH")
      (footprint "eagle-import:TACT_TH")
      (libsource (lib "eagle-import") (part "TACT_TH"))
    )
    (comp (ref "SW19")
      (value "TACT_TH")
      (footprint "eagle-import:TACT_TH")
      (libsource (lib "eagle-import") (part "TACT_TH"))
    )
    (comp (ref "VR1")
      (value "9MM_V")
      (footprint "eagle-import:9MM_V")
      (libsource (lib "eagle-import") (part "9MM_V"))
    )
    (comp (ref "VR2")
      (value "9MM_V")
      (footprint "eagle-import:9MM_V")
      (libsource (lib "eagle-import") (part "9MM_V"))
    )
    (comp (ref "VR3")
      (value "9MM_V")
      (footprint "eagle-import:9MM_V")
      (libsource (lib "eagle-import") (part "9MM_V"))
    )
    (comp (ref "VR4")
      (value "9MM_V")
      (footprint "eagle-import:9MM_V")
      (libsource (lib "eagle-import") (part "9MM_V"))
    )
    (comp (ref "C1")
      (value "0.01u")
      (footprint "eagle-import:C0603")
      (libsource (lib "eagle-import") (part "C-EUC0603"))
    )
    (comp (ref "C2")
      (value "0.01u")
      (footprint "eagle-import:C0603")
      (libsource (lib "eagle-import") (part "C-EUC0603"))
    )
    (comp (ref "C3")
      (value "100u")
      (footprint "eagle-import:PANASONIC_D")
      (libsource (lib "eagle-import") (part "CPOL-EUD"))
    )
    (comp (ref "C4")
      (value "100u")
      (footprint "eagle-import:PANASONIC_D")
      (libsource (lib "eagle-import") (part "CPOL-EUD"))
    )
    (comp (ref "C5")
      (value "0.1u")
      (footprint "eagle-import:C0603")
      (libsource (lib "eagle-import") (part "C-EUC0603"))
    )
    (comp (ref "C6")
      (value "22u")
      (footprint "eagle-import:C1206")
      (libsource (lib "eagle-import") (part "C-EUC1206"))
    )
    (comp (ref "C7")
      (value "0.1u")
      (footprint "eagle-import:C0603")
      (libsource (lib "eagle-import") (part "C-EUC0603"))
    )
    (comp (ref "C8")
      (value "22u")
      (footprint "eagle-import:PANASONIC_C")
      (libsource (lib "eagle-import") (part "CPOL-EUC"))
    )
    (comp (ref "C9")
      (value "0.01u")
      (footprint "eagle-import:C0603")
      (libsource (lib "eagle-import") (part "C-EUC0603"))
    )
    (comp (ref "C10")
      (value "0.1u")
      (footprint "eagle-import:C0603")
      (libsource (lib "eagle-import") (part "C-EUC0603"))
    )
    (comp (ref "C11")
      (value "22u")
      (footprint "eagle-import:PANASONIC_C")
      (libsource (lib "eagle-import") (part "CPOL-EUC"))
    )
    (comp (ref "C12")
      (value "10u")
      (footprint "eagle-import:C0805")
      (libsource (lib "eagle-import") (part "C-EUC0805"))
    )
    (comp (ref "C13")
      (value "1u")
      (footprint "eagle-import:C0805")
      (libsource (lib "eagle-import") (part "C-EUC0805"))
    )
    (comp (ref "C14")
      (value "2.2u")
      (footprint "eagle-import:C0805")
      (libsource (lib "eagle-import") (part "C-EUC0805"))
    )
    (comp (ref "C15")
      (value "220p")
      (footprint "eagle-import:C0603")
      (libsource (lib "eagle-import") (part "C-EUC0603"))
    )
    (comp (ref "C16")
      (value "470p")
      (footprint "eagle-import:C0603")
      (libsource (lib "eagle-import") (part "C-EUC0603"))
    )
    (comp (ref "C17")
      (value "10u")
      (footprint "eagle-import:C0805")
      (libsource (lib "eagle-import") (part "C-EUC0805"))
    )
    (comp (ref "C18")
      (value "10u")
      (footprint "eagle-import:C0805")
      (libsource (lib "eagle-import") (part "C-EUC0805"))
    )
    (comp (ref "C19")
      (value "0.1u")
      (footprint "eagle-import:C0603")
      (libsource (lib "eagle-import") (part "C-EUC0603"))
    )
    (comp (ref "C20")
      (value "100u")
      (footprint "eagle-import:PANASONIC_D")
      (libsource (lib "eagle-import") (part "CPOL-EUD"))
    )
    (comp (ref "C43")
      (value "22u")
      (footprint "eagle-import:C1206")
      (libsource (lib "eagle-import") (part "C-EUC1206"))
    )
    (comp (ref "C44")
      (value "22u")
      (footprint "eagle-import:C1206")
      (libsource (lib "eagle-import") (part "C-EUC1206"))
    )
    (comp (ref "C45")
      (value "22u")
      (footprint "eagle-import:PANASONIC_C")
      (libsource (lib "eagle-import") (part "CPOL-EUC"))
    )
    (comp (ref "C46")
      (value "0.47u")
      (footprint "eagle-import:C0603")
      (libsource (lib "eagle-import") (part "C-EUC0603"))
    )
    (comp (ref "D18")
      (value "1N5819-SOD123")
      (footprint "eagle-import:SOD123")
      (libsource (lib "eagle-import") (part "1N5819-SOD123"))
    )
    (comp (ref "D19")
      (value "DNP")
      (footprint "eagle-import:SOT23")
      (libsource (lib "eagle-import") (part "ZENER-DIODESOT23"))
    )
    (comp (ref "D21")
      (value "RB160MM")
      (footprint "eagle-import:SOD123")
      (libsource (lib "eagle-import") (part "1N5819-SOD123"))
    )
    (comp (ref "D22")
      (value "5V")
      (footprint "eagle-import:SOD123")
      (libsource (lib "eagle-import") (part "ZENER-DIODESOD123"))
    )
    (comp (ref "F1")
      (value "FUSE1206")
      (footprint "eagle-import:R1206")
      (libsource (lib "eagle-import") (part "FUSE1206"))
    )
    (comp (ref "IC2")
      (value "LM2611")
      (footprint "eagle-import:SOT23-5")
      (libsource (lib "eagle-import") (part "LM2611"))
    )
    (comp (ref "IC6")
      (value "9V")
      (footprint "eagle-import:TO252-3")
      (libsource (lib "eagle-import") (part "78XXTO252-3"))
    )
    (comp (ref "IC7")
      (value "R-78E3.3-0.5")
      (footprint "eagle-import:R-78E")
      (libsource (lib "eagle-import") (part "R-78E-0.5"))
    )
    (comp (ref "IC8")
      (value "LD2981ABU33")
      (footprint "eagle-import:SOT89R")
      (libsource (lib "eagle-import") (part "LD2981U"))
    )
    (comp (ref "J1")
      (value "694106301002")
      (footprint "eagle-import:694106301002")
      (fields
        (field (name "DIGIKEY_PART_NUMBER") "732-5930-ND")
        (field (name "MANUFACTURER") "Wurth Electronics Inc.")
        (field (name "CREATED_BY") "PCBLayout.com")
      )
      (libsource (lib "eagle-import") (part "694106301002"))
    )
    (comp (ref "JP3")
      (value "PIN_HEADER_SHROUDED_2X5")
      (footprint "eagle-import:PIN_HEADER_SHROUDED_2X5")
      (libsource (lib "eagle-import") (part "PIN_HEADER_SHROUDED_2X5"))
    )
    (comp (ref "L1")
      (value "1000Ohm@100 MHz")
      (footprint "eagle-import:WE-CBF_0603(W=2.2)")
      (libsource (lib "eagle-import") (part "WE-CBF_0603_WB_HS_742792664"))
    )
    (comp (ref "L2")
      (value "1000Ohm@100 MHz")
      (footprint "eagle-import:WE-CBF_0603(W=2.2)")
      (libsource (lib "eagle-import") (part "WE-CBF_0603_WB_HS_742792664"))
    )
    (comp (ref "L3")
      (value "1000Ohm@100 MHz")
      (footprint "eagle-import:WE-CBF_0603(W=2.2)")
      (libsource (lib "eagle-import") (part "WE-CBF_0603_WB_HS_742792664"))
    )
    (comp (ref "L4")
      (value "1000Ohm@100 MHz")
      (footprint "eagle-import:WE-CBF_0603(W=2.2)")
      (libsource (lib "eagle-import") (part "WE-CBF_0603_WB_HS_742792664"))
    )
    (comp (ref "L5")
      (value "NRS4018T150MDGJ")
      (footprint "eagle-import:NR40XX")
      (libsource (lib "eagle-import") (part "NR40XX"))
    )
    (comp (ref "L6")
      (value "NRS4018T150MDGJ")
      (footprint "eagle-import:NR40XX")
      (libsource (lib "eagle-import") (part "NR40XX"))
    )
    (comp (ref "L7")
      (value "33u")
      (footprint "eagle-import:L2012C")
      (libsource (lib "eagle-import") (part "L-EUL2012C"))
    )
    (comp (ref "R1")
      (value "DNP")
      (footprint "eagle-import:R1210")
      (libsource (lib "eagle-import") (part "R-EU_R1210"))
    )
    (comp (ref "R2")
      (value "60.4k")
      (footprint "eagle-import:R0603")
      (libsource (lib "eagle-import") (part "R-EU_R0603"))
    )
    (comp (ref "R3")
      (value "47.5")
      (footprint "eagle-import:R0603")
      (libsource (lib "eagle-import") (part "R-EU_R0603"))
    )
    (comp (ref "R4")
      (value "60.4k")
      (footprint "eagle-import:R0603")
      (libsource (lib "eagle-import") (part "R-EU_R0603"))
    )
    (comp (ref "R5")
      (value "10k")
      (footprint "eagle-import:R0603")
      (libsource (lib "eagle-import") (part "R-EU_R0603"))
    )
    (comp (ref "R35")
      (value "2.2k")
      (footprint "eagle-import:R0603")
      (libsource (lib "eagle-import") (part "R-EU_R0603"))
    )
  )
  (nets
    (net (code "1") (name "+3V3") (class "Default")
      (node (ref "C30") (pin "1") (pinfunction "1_1") (pintype "passive"))
      (node (ref "C31") (pin "1") (pinfunction "1_1") (pintype "passive"))
      (node (ref "C32") (pin "1") (pinfunction "1_1") (pintype "passive"))
      (node (ref "C33") (pin "1") (pinfunction "1_1") (pintype "passive"))
      (node (ref "C7") (pin "1") (pinfunction "1_1") (pintype "passive"))
      (node (ref "C8") (pin "+") (pinfunction "+_+") (pintype "passive"))
      (node (ref "DIS1") (pin "2") (pinfunction "VCC_2") (pintype "bidirectional"))
      (node (ref "IC1") (pin "1") (pinfunction "VBAT_1") (pintype "bidirectional"))
      (node (ref "IC1") (pin "19") (pinfunction "VDD1_19") (pintype "bidirectional"))
      (node (ref "IC1") (pin "32") (pinfunction "VDD2_32") (pintype "bidirectional"))
      (node (ref "IC1") (pin "48") (pinfunction "VDD3_48") (pintype "bidirectional"))
      (node (ref "IC1") (pin "64") (pinfunction "VDD4_64") (pintype "bidirectional"))
      (node (ref "IC7") (pin "3") (pinfunction "OUT_3") (pintype "passive"))
      (node (ref "P3") (pin "1") (pinfunction "1_1") (pintype "bidirectional"))
      (node (ref "R18") (pin "2") (pinfunction "2_2") (pintype "passive"))
    )
    (net (code "2") (name "+3V3_A") (class "Default")
      (node (ref "C28") (pin "1") (pinfunction "1_1") (pintype "passive"))
      (node (ref "C29") (pin "1") (pinfunction "1_1") (pintype "passive"))
      (node (ref "C45") (pin "+") (pinfunction "+_+") (pintype "passive"))
      (node (ref "C47") (pin "1") (pinfunction "1_1") (pintype "passive"))
      (node (ref "IC1") (pin "13") (pinfunction "VDDA_13") (pintype "bidirectional"))
      (node (ref "IC4") (pin "8") (pinfunction "V+_8") (pintype "bidirectional"))
      (node (ref "IC8") (pin "2") (pinfunction "OUT_2") (pintype "passive"))
      (node (ref "P4") (pin "1") (pinfunction "1_1") (pintype "bidirectional"))
      (node (ref "VR1") (pin "3") (pinfunction "3_3") (pintype "passive"))
      (node (ref "VR2") (pin "3") (pinfunction "3_3") (pintype "passive"))
      (node (ref "VR3") (pin "3") (pinfunction "3_3") (pintype "passive"))
      (node (ref "VR4") (pin "3") (pinfunction "3_3") (pintype "passive"))
    )
    (net (code "3") (name "ADC1") (class "Default")
      (node (ref "C35") (pin "2") (pinfunction "2_2") (pintype "passive"))
      (node (ref "IC1") (pin "14") (pinfunction "PA0-WKUP_14") (pintype "bidirectional"))
      (node (ref "IC4") (pin "1") (pinfunction "OUT_1") (pintype "output"))
      (node (ref "R12") (pin "2") (pinfunction "2_2") (pintype "passive"))
    )
    (net (code "4") (name "ADC3") (class "Default")
      (node (ref "C37") (pin "2") (pinfunction "2_2") (pintype "passive"))
      (node (ref "IC1") (pin "15") (pinfunction "PA1_15") (pintype "bidirectional"))
      (node (ref "IC4") (pin "7") (pinfunction "OUT_7") (pintype "output"))
      (node (ref "R15") (pin "2") (pinfunction "2_2") (pintype "passive"))
    )
    (net (code "5") (name "AREF_-5V") (class "Default")
      (node (ref "C46") (pin "1") (pinfunction "1_1") (pintype "passive"))
      (node (ref "D22") (pin "A") (pinfunction "A_A") (pintype "passive"))
      (node (ref "P5") (pin "1") (pinfunction "1_1") (pintype "bidirectional"))
      (node (ref "R11") (pin "1") (pinfunction "1_1") (pintype "passive"))
      (node (ref "R14") (pin "1") (pinfunction "1_1") (pintype "passive"))
      (node (ref "R24") (pin "1") (pinfunction "1_1") (pintype "passive"))
      (node (ref "R30") (pin "1") (pinfunction "1_1") (pintype "passive"))
      (node (ref "R35") (pin "1") (pinfunction "1_1") (pintype "passive"))
    )
    (net (code "6") (name "COL1") (class "Default")
      (node (ref "IC1") (pin "55") (pinfunction "PB3/JTDO_55") (pintype "bidirectional"))
      (node (ref "SW1") (pin "1") (pinfunction "1_1") (pintype "passive"))
      (node (ref "SW2") (pin "1") (pinfunction "1_1") (pintype "passive"))
      (node (ref "SW3") (pin "1") (pinfunction "1_1") (pintype "passive"))
    )
    (net (code "7") (name "COL2") (class "Default")
      (node (ref "IC1") (pin "56") (pinfunction "PB4/NJTRST_56") (pintype "bidirectional"))
      (node (ref "SW4") (pin "1") (pinfunction "1_1") (pintype "passive"))
      (node (ref "SW5") (pin "1") (pinfunction "1_1") (pintype "passive"))
      (node (ref "SW6") (pin "1") (pinfunction "1_1") (pintype "passive"))
    )
    (net (code "8") (name "COL3") (class "Default")
      (node (ref "IC1") (pin "57") (pinfunction "PB5_57") (pintype "bidirectional"))
      (node (ref "SW10") (pin "1") (pinfunction "1_1") (pintype "passive"))
      (node (ref "SW7") (pin "1") (pinfunction "1_1") (pintype "passive"))
      (node (ref "SW8") (pin "1") (pinfunction "1_1") (pintype "passive"))
    )
    (net (code "9") (name "COL4") (class "Default")
      (node (ref "IC1") (pin "58") (pinfunction "PB6_58") (pintype "bidirectional"))
      (node (ref "SW12") (pin "1") (pinfunction "1_1") (pintype "passive"))
      (node (ref "SW9") (pin "1") (pinfunction "1_1") (pintype "passive"))
    )
    (net (code "10") (name "COL5") (class "Default")
      (node (ref "IC1") (pin "59") (pinfunction "PB7_59") (pintype "bidirectional"))
      (node (ref "SW11") (pin "1") (pinfunction "1_1") (pintype "passive"))
      (node (ref "SW13") (pin "1") (pinfunction "1_1") (pintype "passive"))
    )
    (net (code "11") (name "COL6") (class "Default")
      (node (ref "IC1") (pin "61") (pinfunction "PB8_61") (pintype "bidirectional"))
      (node (ref "SW14") (pin "1") (pinfunction "1_1") (pintype "passive"))
      (node (ref "SW15") (pin "1") (pinfunction "1_1") (pintype "passive"))
    )
    (net (code "12") (name "COL7") (class "Default")
      (node (ref "IC1") (pin "62") (pinfunction "PB9_62") (pintype "bidirectional"))
      (node (ref "SW16") (pin "1") (pinfunction "1_1") (pintype "passive"))
      (node (ref "SW17") (pin "1") (pinfunction "1_1") (pintype "passive"))
    )
    (net (code "13") (name "DAC1") (class "Default")
      (node (ref "IC1") (pin "20") (pinfunction "PA4_20") (pintype "bidirectional"))
      (node (ref "R29") (pin "1") (pinfunction "1_1") (pintype "passive"))
    )
    (net (code "14") (name "DAC2") (class "Default")
      (node (ref "IC1") (pin "21") (pinfunction "PA5_21") (pintype "bidirectional"))
      (node (ref "R23") (pin "1") (pinfunction "1_1") (pintype "passive"))
    )
    (net (code "15") (name "DISP_DC") (class "Default")
      (node (ref "DIS1") (pin "6") (pinfunction "DC_6") (pintype "bidirectional"))
      (node (ref "IC1") (pin "34") (pinfunction "PB13/I2S2_CK_34") (pintype "bidirectional"))
    )
    (net (code "16") (name "DISP_RES") (class "Default")
      (node (ref "DIS1") (pin "5") (pinfunction "RES_5") (pintype "bidirectional"))
      (node (ref "IC1") (pin "35") (pinfunction "PB14/I2S2_XD_35") (pintype "bidirectional"))
    )
    (net (code "17") (name "ENC_2") (class "Default")
      (node (ref "C54") (pin "1") (pinfunction "1_1") (pintype "passive"))
      (node (ref "EN1") (pin "2") (pinfunction "2_2") (pintype "passive"))
      (node (ref "IC1") (pin "36") (pinfunction "PB15/I2S2_SD_36") (pintype "bidirectional"))
    )
    (net (code "18") (name "ENC_A") (class "Default")
      (node (ref "C56") (pin "1") (pinfunction "1_1") (pintype "passive"))
      (node (ref "EN1") (pin "A") (pinfunction "A_A") (pintype "passive"))
      (node (ref "IC1") (pin "37") (pinfunction "PC6/I2S2_MCK_37") (pintype "bidirectional"))
    )
    (net (code "19") (name "ENC_B") (class "Default")
      (node (ref "C55") (pin "1") (pinfunction "1_1") (pintype "passive"))
      (node (ref "EN1") (pin "B") (pinfunction "B_B") (pintype "passive"))
      (node (ref "IC1") (pin "38") (pinfunction "PC7_38") (pintype "bidirectional"))
    )
    (net (code "20") (name "GND") (class "Default")
      (node (ref "C1") (pin "2") (pinfunction "2_2") (pintype "passive"))
      (node (ref "C10") (pin "2") (pinfunction "2_2") (pintype "passive"))
      (node (ref "C11") (pin "-") (pinfunction "-_-") (pintype "passive"))
      (node (ref "C12") (pin "2") (pinfunction "2_2") (pintype "passive"))
      (node (ref "C13") (pin "2") (pinfunction "2_2") (pintype "passive"))
      (node (ref "C17") (pin "2") (pinfunction "2_2") (pintype "passive"))
      (node (ref "C18") (pin "2") (pinfunction "2_2") (pintype "passive"))
      (node (ref "C19") (pin "2") (pinfunction "2_2") (pintype "passive"))
      (node (ref "C2") (pin "2") (pinfunction "2_2") (pintype "passive"))
      (node (ref "C20") (pin "+") (pinfunction "+_+") (pintype "passive"))
      (node (ref "C21") (pin "2") (pinfunction "2_2") (pintype "passive"))
      (node (ref "C22") (pin "2") (pinfunction "2_2") (pintype "passive"))
      (node (ref "C23") (pin "2") (pinfunction "2_2") (pintype "passive"))
      (node (ref "C24") (pin "2") (pinfunction "2_2") (pintype "passive"))
      (node (ref "C25") (pin "1") (pinfunction "1_1") (pintype "passive"))
      (node (ref "C26") (pin "1") (pinfunction "1_1") (pintype "passive"))
      (node (ref "C27") (pin "2") (pinfunction "2_2") (pintype "passive"))
      (node (ref "C28") (pin "2") (pinfunction "2_2") (pintype "passive"))
      (node (ref "C29") (pin "2") (pinfunction "2_2") (pintype "passive"))
      (node (ref "C3") (pin "-") (pinfunction "-_-") (pintype "passive"))
      (node (ref "C30") (pin "2") (pinfunction "2_2") (pintype "passive"))
      (node (ref "C31") (pin "2") (pinfunction "2_2") (pintype "passive"))
      (node (ref "C32") (pin "2") (pinfunction "2_2") (pintype "passive"))
      (node (ref "C33") (pin "2") (pinfunction "2_2") (pintype "passive"))
      (node (ref "C34") (pin "2") (pinfunction "2_2") (pintype "passive"))
      (node (ref "C36") (pin "2") (pinfunction "2_2") (pintype "passive"))
      (node (ref "C4") (pin "-") (pinfunction "-_-") (pintype "passive"))
      (node (ref "C43") (pin "2") (pinfunction "2_2") (pintype "passive"))
      (node (ref "C44") (pin "2") (pinfunction "2_2") (pintype "passive"))
      (node (ref "C45") (pin "-") (pinfunction "-_-") (pintype "passive"))
      (node (ref "C46") (pin "2") (pinfunction "2_2") (pintype "passive"))
      (node (ref "C47") (pin "2") (pinfunction "2_2") (pintype "passive"))
      (node (ref "C48") (pin "2") (pinfunction "2_2") (pintype "passive"))
      (node (ref "C49") (pin "1") (pinfunction "1_1") (pintype "passive"))
      (node (ref "C5") (pin "2") (pinfunction "2_2") (pintype "passive"))
      (node (ref "C50") (pin "2") (pinfunction "2_2") (pintype "passive"))
      (node (ref "C51") (pin "1") (pinfunction "1_1") (pintype "passive"))
      (node (ref "C52") (pin "2") (pinfunction "2_2") (pintype "passive"))
      (node (ref "C53") (pin "2") (pinfunction "2_2") (pintype "passive"))
      (node (ref "C54") (pin "2") (pinfunction "2_2") (pintype "passive"))
      (node (ref "C55") (pin "2") (pinfunction "2_2") (pintype "passive"))
      (node (ref "C56") (pin "2") (pinfunction "2_2") (pintype "passive"))
      (node (ref "C6") (pin "2") (pinfunction "2_2") (pintype "passive"))
      (node (ref "C7") (pin "2") (pinfunction "2_2") (pintype "passive"))
      (node (ref "C8") (pin "-") (pinfunction "-_-") (pintype "passive"))
      (node (ref "C9") (pin "2") (pinfunction "2_2") (pintype "passive"))
      (node (ref "D19") (pin "1") (pinfunction "A_1") (pintype "passive"))
      (node (ref "D20") (pin "A") (pinfunction "A_A") (pintype "passive"))
      (node (ref "D21") (pin "C") (pinfunction "C_C") (pintype "passive"))
      (node (ref "D22") (pin "C") (pinfunction "C_C") (pintype "passive"))
      (node (ref "DIS1") (pin "1") (pinfunction "GND_1") (pintype "bidirectional"))
      (node (ref "EN1") (pin "1") (pinfunction "1_1") (pintype "passive"))
      (node (ref "EN1") (pin "C") (pinfunction "C_C") (pintype "passive"))
      (node (ref "IC1") (pin "12") (pinfunction "VSSA_12") (pintype "bidirectional"))
      (node (ref "IC1") (pin "18") (pinfunction "VSS1_18") (pintype "bidirectional"))
      (node (ref "IC1") (pin "31") (pinfunction "VSS2_31") (pintype "bidirectional"))
      (node (ref "IC1") (pin "47") (pinfunction "VSS3_47") (pintype "bidirectional"))
      (node (ref "IC1") (pin "63") (pinfunction "VSS4_63") (pintype "bidirectional"))
      (node (ref "IC2") (pin "2") (pinfunction "GND_2") (pintype "bidirectional"))
      (node (ref "IC3") (pin "10") (pinfunction "+IN_10") (pintype "input"))
      (node (ref "IC3") (pin "12") (pinfunction "+IN_12") (pintype "input"))
      (node (ref "IC3") (pin "3") (pinfunction "+IN_3") (pintype "input"))
      (node (ref "IC3") (pin "5") (pinfunction "+IN_5") (pintype "input"))
      (node (ref "IC4") (pin "3") (pinfunction "+IN_3") (pintype "input"))
      (node (ref "IC4") (pin "4") (pinfunction "V-_4") (pintype "bidirectional"))
      (node (ref "IC4") (pin "5") (pinfunction "+IN_5") (pintype "input"))
      (node (ref "IC5") (pin "5") (pinfunction "+IN_5") (pintype "input"))
      (node (ref "IC6") (pin "GND") (pinfunction "GND_GND") (pintype "input"))
      (node (ref "IC7") (pin "2") (pinfunction "GND_2") (pintype "input"))
      (node (ref "IC8") (pin "3") (pinfunction "GND_3") (pintype "input"))
      (node (ref "IC8") (pin "4") (pinfunction "GND_4") (pintype "input"))
      (node (ref "J1") (pin "2") (pinfunction "2_2") (pintype "passive"))
      (node (ref "J10") (pin "S") (pinfunction "1_S") (pintype "passive"))
      (node (ref "J10") (pin "TS") (pinfunction "3_TS") (pintype "passive"))
      (node (ref "J11") (pin "S") (pinfunction "1_S") (pintype "passive"))
      (node (ref "J12") (pin "S") (pinfunction "1_S") (pintype "passive"))
      (node (ref "J13") (pin "S") (pinfunction "1_S") (pintype "passive"))
      (node (ref "J14") (pin "3") (pinfunction "1_3") (pintype "passive"))
      (node (ref "J15") (pin "3") (pinfunction "1_3") (pintype "passive"))
      (node (ref "J16") (pin "1") (pinfunction "S_1") (pintype "passive"))
      (node (ref "J17") (pin "1") (pinfunction "S_1") (pintype "passive"))
      (node (ref "J2") (pin "2") (pinfunction "3_2") (pintype "passive"))
      (node (ref "J2") (pin "3") (pinfunction "1_3") (pintype "passive"))
      (node (ref "J3") (pin "2") (pinfunction "3_2") (pintype "passive"))
      (node (ref "J3") (pin "3") (pinfunction "1_3") (pintype "passive"))
      (node (ref "J4") (pin "2") (pinfunction "3_2") (pintype "passive"))
      (node (ref "J4") (pin "3") (pinfunction "1_3") (pintype "passive"))
      (node (ref "J5") (pin "3") (pinfunction "1_3") (pintype "passive"))
      (node (ref "J6") (pin "3") (pinfunction "1_3") (pintype "passive"))
      (node (ref "J7") (pin "3") (pinfunction "1_3") (pintype "passive"))
      (node (ref "J8") (pin "S") (pinfunction "1_S") (pintype "passive"))
      (node (ref "J8") (pin "TS") (pinfunction "3_TS") (pintype "passive"))
      (node (ref "J9") (pin "S") (pinfunction "1_S") (pintype "passive"))
      (node (ref "J9") (pin "TS") (pinfunction "3_TS") (pintype "passive"))
      (node (ref "JP1") (pin "1") (pinfunction "1_1") (pintype "passive"))
      (node (ref "JP3") (pin "3") (pinfunction "P$3_3") (pintype "bidirectional"))
      (node (ref "JP3") (pin "4") (pinfunction "P$4_4") (pintype "bidirectional"))
      (node (ref "JP3") (pin "5") (pinfunction "P$5_5") (pintype "bidirectional"))
      (node (ref "JP3") (pin "6") (pinfunction "P$6_6") (pintype "bidirectional"))
      (node (ref "JP3") (pin "7") (pinfunction "P$7_7") (pintype "bidirectional"))
      (node (ref "JP3") (pin "8") (pinfunction "P$8_8") (pintype "bidirectional"))
      (node (ref "LED1") (pin "2") (pinfunction "C_2") (pintype "passive"))
      (node (ref "LED2") (pin "2") (pinfunction "C_2") (pintype "passive"))
      (node (ref "P7") (pin "1") (pinfunction "1_1") (pintype "bidirectional"))
      (node (ref "Q2") (pin "E") (pinfunction "E_E") (pintype "passive"))
      (node (ref "R17") (pin "1") (pinfunction "1_1") (pintype "passive"))
      (node (ref "R20") (pin "1") (pinfunction "1_1") (pintype "passive"))
      (node (ref "R3") (pin "1") (pinfunction "1_1") (pintype "passive"))
      (node (ref "R5") (pin "1") (pinfunction "1_1") (pintype "passive"))
      (node (ref "SW18") (pin "P3") (pinfunction "2_P3") (pintype "bidirectional"))
      (node (ref "SW18") (pin "P4") (pinfunction "2_P4") (pintype "bidirectional"))
      (node (ref "SW19") (pin "P3") (pinfunction "2_P3") (pintype "bidirectional"))
      (node (ref "SW19") (pin "P4") (pinfunction "2_P4") (pintype "bidirectional"))
      (node (ref "VR1") (pin "1") (pinfunction "1_1") (pintype "passive"))
      (node (ref "VR2") (pin "1") (pinfunction "1_1") (pintype "passive"))
      (node (ref "VR3") (pin "1") (pinfunction "1_1") (pintype "passive"))
      (node (ref "VR4") (pin "1") (pinfunction "1_1") (pintype "passive"))
      (node (ref "VR5") (pin "1") (pinfunction "1_1") (pintype "passive"))
      (node (ref "VR5") (pin "4") (pinfunction "1_4") (pintype "passive"))
    )
    (net (code "21") (name "LED1G") (class "Default")
      (node (ref "IC1") (pin "41") (pinfunction "PA8_41") (pintype "bidirectional"))
      (node (ref "R36") (pin "1") (pinfunction "1_1") (pintype "passive"))
    )
    (net (code "22") (name "LED1R") (class "Default")
      (node (ref "IC1") (pin "40") (pinfunction "PC9_40") (pintype "bidirectional"))
      (node (ref "R37") (pin "2") (pinfunction "2_2") (pintype "passive"))
    )
    (net (code "23") (name "LED2G") (class "Default")
      (node (ref "IC1") (pin "45") (pinfunction "PA12/USART1_RTS_45") (pintype "bidirectional"))
      (node (ref "R38") (pin "1") (pinfunction "1_1") (pintype "passive"))
    )
    (net (code "24") (name "LED2R") (class "Default")
      (node (ref "IC1") (pin "44") (pinfunction "PA11/USART1_CTS_44") (pintype "bidirectional"))
      (node (ref "R39") (pin "2") (pinfunction "2_2") (pintype "passive"))
    )
    (net (code "25") (name "Net-(BOOT-P)") (class "Default")
      (node (ref "BOOT") (pin "1") (pinfunction "P_1") (pintype "passive"))
      (node (ref "IC1") (pin "60") (pinfunction "BOOT_60") (pintype "bidirectional"))
    )
    (net (code "26") (name "Net-(C1-Pad1)") (class "Default")
      (node (ref "C1") (pin "1") (pinfunction "1_1") (pintype "passive"))
      (node (ref "F1") (pin "2") (pinfunction "2_2") (pintype "passive"))
      (node (ref "L1") (pin "1") (pinfunction "1_1") (pintype "passive"))
    )
    (net (code "27") (name "Net-(C2-Pad1)") (class "Default")
      (node (ref "C2") (pin "1") (pinfunction "1_1") (pintype "passive"))
      (node (ref "D18") (pin "A") (pinfunction "A_A") (pintype "passive"))
      (node (ref "L1") (pin "2") (pinfunction "2_2") (pintype "passive"))
    )
    (net (code "28") (name "Net-(C9-Pad1)") (class "Default")
      (node (ref "C9") (pin "1") (pinfunction "1_1") (pintype "passive"))
      (node (ref "IC6") (pin "IN") (pinfunction "IN_IN") (pintype "input"))
      (node (ref "L3") (pin "2") (pinfunction "2_2") (pintype "passive"))
    )
    (net (code "29") (name "Net-(C14-Pad2)") (class "Default")
      (node (ref "C14") (pin "2") (pinfunction "2_2") (pintype "passive"))
      (node (ref "D21") (pin "A") (pinfunction "A_A") (pintype "passive"))
      (node (ref "L6") (pin "2") (pinfunction "2_2") (pintype "passive"))
    )
    (net (code "30") (name "Net-(C15-Pad2)") (class "Default")
      (node (ref "C15") (pin "2") (pinfunction "2_2") (pintype "passive"))
      (node (ref "R3") (pin "2") (pinfunction "2_2") (pintype "passive"))
    )
    (net (code "31") (name "Net-(C25-Pad2)") (class "Default")
      (node (ref "C25") (pin "2") (pinfunction "2_2") (pintype "passive"))
      (node (ref "Q1") (pin "2") (pinfunction "2_2") (pintype "passive"))
      (node (ref "R6") (pin "1") (pinfunction "1_1") (pintype "passive"))
    )
    (net (code "32") (name "Net-(C26-Pad2)") (class "Default")
      (node (ref "C26") (pin "2") (pinfunction "2_2") (pintype "passive"))
      (node (ref "Q1") (pin "1") (pinfunction "1_1") (pintype "passive"))
      (node (ref "R7") (pin "1") (pinfunction "1_1") (pintype "passive"))
    )
    (net (code "33") (name "Net-(D1-PadA)") (class "Default")
      (node (ref "D1") (pin "A") (pinfunction "A_A") (pintype "passive"))
      (node (ref "SW1") (pin "2") (pinfunction "2_2") (pintype "passive"))
    )
    (net (code "34") (name "Net-(D2-PadA)") (class "Default")
      (node (ref "D2") (pin "A") (pinfunction "A_A") (pintype "passive"))
      (node (ref "SW2") (pin "2") (pinfunction "2_2") (pintype "passive"))
    )
    (net (code "35") (name "Net-(D3-PadA)") (class "Default")
      (node (ref "D3") (pin "A") (pinfunction "A_A") (pintype "passive"))
      (node (ref "SW3") (pin "2") (pinfunction "2_2") (pintype "passive"))
    )
    (net (code "36") (name "Net-(D4-PadA)") (class "Default")
      (node (ref "D4") (pin "A") (pinfunction "A_A") (pintype "passive"))
      (node (ref "SW4") (pin "2") (pinfunction "2_2") (pintype "passive"))
    )
    (net (code "37") (name "Net-(D5-PadA)") (class "Default")
      (node (ref "D5") (pin "A") (pinfunction "A_A") (pintype "passive"))
      (node (ref "SW5") (pin "2") (pinfunction "2_2") (pintype "passive"))
    )
    (net (code "38") (name "Net-(D6-PadA)") (class "Default")
      (node (ref "D6") (pin "A") (pinfunction "A_A") (pintype "passive"))
      (node (ref "SW6") (pin "2") (pinfunction "2_2") (pintype "passive"))
    )
    (net (code "39") (name "Net-(D7-PadA)") (class "Default")
      (node (ref "D7") (pin "A") (pinfunction "A_A") (pintype "passive"))
      (node (ref "SW7") (pin "2") (pinfunction "2_2") (pintype "passive"))
    )
    (net (code "40") (name "Net-(D8-PadA)") (class "Default")
      (node (ref "D8") (pin "A") (pinfunction "A_A") (pintype "passive"))
      (node (ref "SW8") (pin "2") (pinfunction "2_2") (pintype "passive"))
    )
    (net (code "41") (name "Net-(D9-PadA)") (class "Default")
      (node (ref "D9") (pin "A") (pinfunction "A_A") (pintype "passive"))
      (node (ref "SW9") (pin "2") (pinfunction "2_2") (pintype "passive"))
    )
    (net (code "42") (name "Net-(D10-PadA)") (class "Default")
      (node (ref "D10") (pin "A") (pinfunction "A_A") (pintype "passive"))
      (node (ref "SW10") (pin "2") (pinfunction "2_2") (pintype "passive"))
    )
    (net (code "43") (name "Net-(D11-PadA)") (class "Default")
      (node (ref "D11") (pin "A") (pinfunction "A_A") (pintype "passive"))
      (node (ref "SW11") (pin "2") (pinfunction "2_2") (pintype "passive"))
    )
    (net (code "44") (name "Net-(D12-PadA)") (class "Default")
      (node (ref "D12") (pin "A") (pinfunction "A_A") (pintype "passive"))
      (node (ref "SW12") (pin "2") (pinfunction "2_2") (pintype "passive"))
    )
    (net (code "45") (name "Net-(D13-PadA)") (class "Default")
      (node (ref "D13") (pin "A") (pinfunction "A_A") (pintype "passive"))
      (node (ref "SW13") (pin "2") (pinfunction "2_2") (pintype "passive"))
    )
    (net (code "46") (name "Net-(D14-PadA)") (class "Default")
      (node (ref "D14") (pin "A") (pinfunction "A_A") (pintype "passive"))
      (node (ref "SW14") (pin "2") (pinfunction "2_2") (pintype "passive"))
    )
    (net (code "47") (name "Net-(D15-PadA)") (class "Default")
      (node (ref "D15") (pin "A") (pinfunction "A_A") (pintype "passive"))
      (node (ref "SW15") (pin "2") (pinfunction "2_2") (pintype "passive"))
    )
    (net (code "48") (name "Net-(D16-PadA)") (class "Default")
      (node (ref "D16") (pin "A") (pinfunction "A_A") (pintype "passive"))
      (node (ref "SW16") (pin "2") (pinfunction "2_2") (pintype "passive"))
    )
    (net (code "49") (name "Net-(D17-PadA)") (class "Default")
      (node (ref "D17") (pin "A") (pinfunction "A_A") (pintype "passive"))
      (node (ref "SW17") (pin "2") (pinfunction "2_2") (pintype "passive"))
    )
    (net (code "50") (name "Net-(D20-PadC)") (class "Default")
      (node (ref "D20") (pin "C") (pinfunction "C_C") (pintype "passive"))
      (node (ref "Q2") (pin "B") (pinfunction "B_B") (pintype "passive"))
      (node (ref "R16") (pin "2") (pinfunction "2_2") (pintype "passive"))
      (node (ref "R17") (pin "2") (pinfunction "2_2") (pintype "passive"))
    )
    (net (code "51") (name "Net-(IC1-PA2)") (class "Default")
      (node (ref "IC1") (pin "16") (pinfunction "PA2_16") (pintype "bidirectional"))
      (node (ref "PA2") (pin "1") (pinfunction "P_1") (pintype "passive"))
    )
    (net (code "52") (name "Net-(IC1-PA3)") (class "Default")
      (node (ref "IC1") (pin "17") (pinfunction "PA3_17") (pintype "bidirectional"))
      (node (ref "PA3") (pin "1") (pinfunction "P_1") (pintype "passive"))
    )
    (net (code "53") (name "Net-(IC1-PC0)") (class "Default")
      (node (ref "IC1") (pin "8") (pinfunction "PC0_8") (pintype "bidirectional"))
      (node (ref "PC0") (pin "1") (pinfunction "P_1") (pintype "passive"))
    )
    (net (code "54") (name "Net-(IC1-PC3)") (class "Default")
      (node (ref "IC1") (pin "11") (pinfunction "PC3_11") (pintype "bidirectional"))
      (node (ref "PC3") (pin "1") (pinfunction "P_1") (pintype "passive"))
    )
    (net (code "55") (name "Net-(IC1-PC4)") (class "Default")
      (node (ref "IC1") (pin "24") (pinfunction "PC4_24") (pintype "bidirectional"))
      (node (ref "PC4") (pin "1") (pinfunction "P_1") (pintype "passive"))
    )
    (net (code "56") (name "Net-(IC1-PC8)") (class "Default")
      (node (ref "IC1") (pin "39") (pinfunction "PC8_39") (pintype "bidirectional"))
      (node (ref "PC8") (pin "1") (pinfunction "P_1") (pintype "passive"))
    )
    (net (code "57") (name "Net-(IC1-PC13)") (class "Default")
      (node (ref "IC1") (pin "2") (pinfunction "PC13_2") (pintype "bidirectional"))
      (node (ref "PC13") (pin "1") (pinfunction "P_1") (pintype "passive"))
    )
    (net (code "58") (name "Net-(IC1-PC14-OSC32_IN)") (class "Default")
      (node (ref "IC1") (pin "3") (pinfunction "PC14-OSC32_IN_3") (pintype "bidirectional"))
      (node (ref "PC14") (pin "1") (pinfunction "P_1") (pintype "passive"))
    )
    (net (code "59") (name "Net-(IC1-PC15-OSC32_OUT)") (class "Default")
      (node (ref "IC1") (pin "4") (pinfunction "PC15-OSC32_OUT_4") (pintype "bidirectional"))
      (node (ref "PC15") (pin "1") (pinfunction "P_1") (pintype "passive"))
    )
    (net (code "60") (name "Net-(IC1-PH0-OSC_IN)") (class "Default")
      (node (ref "IC1") (pin "5") (pinfunction "PH0-OSC_IN_5") (pintype "bidirectional"))
      (node (ref "R6") (pin "2") (pinfunction "2_2") (pintype "passive"))
    )
    (net (code "61") (name "Net-(IC1-PH1-OSC_OUT)") (class "Default")
      (node (ref "IC1") (pin "6") (pinfunction "PH1-OSC_OUT_6") (pintype "bidirectional"))
      (node (ref "R7") (pin "2") (pinfunction "2_2") (pintype "passive"))
    )
    (net (code "62") (name "Net-(IC1-VCAP_1)") (class "Default")
      (node (ref "C27") (pin "1") (pinfunction "1_1") (pintype "passive"))
      (node (ref "IC1") (pin "30") (pinfunction "VCAP_1_30") (pintype "bidirectional"))
    )
    (net (code "63") (name "Net-(IC2-NFB)") (class "Default")
      (node (ref "C16") (pin "1") (pinfunction "1_1") (pintype "passive"))
      (node (ref "IC2") (pin "3") (pinfunction "NFB_3") (pintype "bidirectional"))
      (node (ref "R4") (pin "1") (pinfunction "1_1") (pintype "passive"))
      (node (ref "R5") (pin "2") (pinfunction "2_2") (pintype "passive"))
    )
    (net (code "64") (name "Net-(IC2-SHDN)") (class "Default")
      (node (ref "IC2") (pin "4") (pinfunction "SHDN_4") (pintype "bidirectional"))
      (node (ref "R2") (pin "1") (pinfunction "1_1") (pintype "passive"))
    )
    (net (code "65") (name "Net-(IC2-SW)") (class "Default")
      (node (ref "C14") (pin "1") (pinfunction "1_1") (pintype "passive"))
      (node (ref "C15") (pin "1") (pinfunction "1_1") (pintype "passive"))
      (node (ref "IC2") (pin "1") (pinfunction "SW_1") (pintype "bidirectional"))
      (node (ref "L5") (pin "1") (pinfunction "1_1") (pintype "passive"))
    )
    (net (code "66") (name "Net-(IC2-VIN)") (class "Default")
      (node (ref "C12") (pin "1") (pinfunction "1_1") (pintype "passive"))
      (node (ref "C13") (pin "1") (pinfunction "1_1") (pintype "passive"))
      (node (ref "IC2") (pin "5") (pinfunction "VIN_5") (pintype "bidirectional"))
      (node (ref "L4") (pin "2") (pinfunction "2_2") (pintype "passive"))
      (node (ref "L5") (pin "2") (pinfunction "2_2") (pintype "passive"))
      (node (ref "R2") (pin "2") (pinfunction "2_2") (pintype "passive"))
    )
    (net (code "67") (name "Net-(IC3A--IN)") (class "Default")
      (node (ref "C39") (pin "1") (pinfunction "1_1") (pintype "passive"))
      (node (ref "IC3") (pin "2") (pinfunction "-IN_2") (pintype "input"))
      (node (ref "R23") (pin "2") (pinfunction "2_2") (pintype "passive"))
      (node (ref "R24") (pin "2") (pinfunction "2_2") (pintype "passive"))
      (node (ref "R25") (pin "1") (pinfunction "1_1") (pintype "passive"))
    )
    (net (code "68") (name "Net-(IC3A-OUT)") (class "Default")
      (node (ref "C39") (pin "2") (pinfunction "2_2") (pintype "passive"))
      (node (ref "IC3") (pin "1") (pinfunction "OUT_1") (pintype "output"))
      (node (ref "R25") (pin "2") (pinfunction "2_2") (pintype "passive"))
      (node (ref "VR5") (pin "3") (pinfunction "3_3") (pintype "passive"))
    )
    (net (code "69") (name "Net-(IC3B--IN)") (class "Default")
      (node (ref "C40") (pin "1") (pinfunction "1_1") (pintype "passive"))
      (node (ref "IC3") (pin "6") (pinfunction "-IN_6") (pintype "input"))
      (node (ref "R29") (pin "2") (pinfunction "2_2") (pintype "passive"))
      (node (ref "R30") (pin "2") (pinfunction "2_2") (pintype "passive"))
      (node (ref "R31") (pin "1") (pinfunction "1_1") (pintype "passive"))
    )
    (net (code "70") (name "Net-(IC3B-OUT)") (class "Default")
      (node (ref "C40") (pin "2") (pinfunction "2_2") (pintype "passive"))
      (node (ref "IC3") (pin "7") (pinfunction "OUT_7") (pintype "output"))
      (node (ref "R31") (pin "2") (pinfunction "2_2") (pintype "passive"))
      (node (ref "VR5") (pin "6") (pinfunction "3_6") (pintype "passive"))
    )
    (net (code "71") (name "Net-(IC3C--IN)") (class "Default")
      (node (ref "C42") (pin "1") (pinfunction "1_1") (pintype "passive"))
      (node (ref "IC3") (pin "9") (pinfunction "-IN_9") (pintype "input"))
      (node (ref "R32") (pin "2") (pinfunction "2_2") (pintype "passive"))
      (node (ref "R33") (pin "1") (pinfunction "1_1") (pintype "passive"))
    )
    (net (code "72") (name "Net-(IC3C-OUT)") (class "Default")
      (node (ref "C42") (pin "2") (pinfunction "2_2") (pintype "passive"))
      (node (ref "IC3") (pin "8") (pinfunction "OUT_8") (pintype "output"))
      (node (ref "R34") (pin "1") (pinfunction "1_1") (pintype "passive"))
    )
    (net (code "73") (name "Net-(IC3D--IN)") (class "Default")
      (node (ref "C41") (pin "1") (pinfunction "1_1") (pintype "passive"))
      (node (ref "IC3") (pin "13") (pinfunction "-IN_13") (pintype "input"))
      (node (ref "R26") (pin "2") (pinfunction "2_2") (pintype "passive"))
      (node (ref "R27") (pin "1") (pinfunction "1_1") (pintype "passive"))
    )
    (net (code "74") (name "Net-(IC3D-OUT)") (class "Default")
      (node (ref "C41") (pin "2") (pinfunction "2_2") (pintype "passive"))
      (node (ref "IC3") (pin "14") (pinfunction "OUT_14") (pintype "output"))
      (node (ref "R28") (pin "1") (pinfunction "1_1") (pintype "passive"))
    )
    (net (code "75") (name "Net-(IC4A--IN)") (class "Default")
      (node (ref "C35") (pin "1") (pinfunction "1_1") (pintype "passive"))
      (node (ref "IC4") (pin "2") (pinfunction "-IN_2") (pintype "input"))
      (node (ref "R10") (pin "2") (pinfunction "2_2") (pintype "passive"))
      (node (ref "R11") (pin "2") (pinfunction "2_2") (pintype "passive"))
      (node (ref "R12") (pin "1") (pinfunction "1_1") (pintype "passive"))
    )
    (net (code "76") (name "Net-(IC4B--IN)") (class "Default")
      (node (ref "C37") (pin "1") (pinfunction "1_1") (pintype "passive"))
      (node (ref "IC4") (pin "6") (pinfunction "-IN_6") (pintype "input"))
      (node (ref "R13") (pin "2") (pinfunction "2_2") (pintype "passive"))
      (node (ref "R14") (pin "2") (pinfunction "2_2") (pintype "passive"))
      (node (ref "R15") (pin "1") (pinfunction "1_1") (pintype "passive"))
    )
    (net (code "77") (name "Net-(IC5A-+IN)") (class "Default")
      (node (ref "IC5") (pin "3") (pinfunction "+IN_3") (pintype "input"))
      (node (ref "R19") (pin "2") (pinfunction "2_2") (pintype "passive"))
    )
    (net (code "78") (name "Net-(IC5A--IN)") (class "Default")
      (node (ref "C38") (pin "1") (pinfunction "1_1") (pintype "passive"))
      (node (ref "IC5") (pin "2") (pinfunction "-IN_2") (pintype "input"))
      (node (ref "R20") (pin "2") (pinfunction "2_2") (pintype "passive"))
      (node (ref "R21") (pin "1") (pinfunction "1_1") (pintype "passive"))
    )
    (net (code "79") (name "Net-(IC5A-OUT)") (class "Default")
      (node (ref "C38") (pin "2") (pinfunction "2_2") (pintype "passive"))
      (node (ref "IC5") (pin "1") (pinfunction "OUT_1") (pintype "output"))
      (node (ref "R21") (pin "2") (pinfunction "2_2") (pintype "passive"))
      (node (ref "R22") (pin "1") (pinfunction "1_1") (pintype "passive"))
    )
    (net (code "80") (name "Net-(IC5B--IN)") (class "Default")
      (node (ref "IC5") (pin "6") (pinfunction "-IN_6") (pintype "input"))
      (node (ref "IC5") (pin "7") (pinfunction "OUT_7") (pintype "output"))
    )
    (net (code "81") (name "Net-(IC7-IN)") (class "Default")
      (node (ref "C43") (pin "1") (pinfunction "1_1") (pintype "passive"))
      (node (ref "IC7") (pin "1") (pinfunction "IN_1") (pintype "input"))
      (node (ref "L7") (pin "1") (pinfunction "1_1") (pintype "passive"))
    )
    (net (code "82") (name "Net-(IC8-IN)") (class "Default")
      (node (ref "C44") (pin "1") (pinfunction "1_1") (pintype "passive"))
      (node (ref "IC8") (pin "1") (pinfunction "IN_1") (pintype "input"))
      (node (ref "L2") (pin "2") (pinfunction "2_2") (pintype "passive"))
    )
    (net (code "83") (name "Net-(J2-2)") (class "Default")
      (node (ref "C34") (pin "1") (pinfunction "1_1") (pintype "passive"))
      (node (ref "J2") (pin "1") (pinfunction "2_1") (pintype "passive"))
      (node (ref "J8") (pin "T") (pinfunction "2_T") (pintype "passive"))
      (node (ref "R10") (pin "1") (pinfunction "1_1") (pintype "passive"))
    )
    (net (code "84") (name "Net-(J3-2)") (class "Default")
      (node (ref "C36") (pin "1") (pinfunction "1_1") (pintype "passive"))
      (node (ref "J3") (pin "1") (pinfunction "2_1") (pintype "passive"))
      (node (ref "J9") (pin "T") (pinfunction "2_T") (pintype "passive"))
      (node (ref "R13") (pin "1") (pinfunction "1_1") (pintype "passive"))
    )
    (net (code "85") (name "Net-(J10-2)") (class "Default")
      (node (ref "J10") (pin "T") (pinfunction "2_T") (pintype "passive"))
      (node (ref "J4") (pin "1") (pinfunction "2_1") (pintype "passive"))
      (node (ref "R16") (pin "1") (pinfunction "1_1") (pintype "passive"))
    )
    (net (code "86") (name "Net-(J11-2)") (class "Default")
      (node (ref "J11") (pin "T") (pinfunction "2_T") (pintype "passive"))
      (node (ref "J5") (pin "1") (pinfunction "2_1") (pintype "passive"))
      (node (ref "R22") (pin "2") (pinfunction "2_2") (pintype "passive"))
    )
    (net (code "87") (name "Net-(J12-2)") (class "Default")
      (node (ref "J12") (pin "T") (pinfunction "2_T") (pintype "passive"))
      (node (ref "J6") (pin "1") (pinfunction "2_1") (pintype "passive"))
      (node (ref "R27") (pin "2") (pinfunction "2_2") (pintype "passive"))
      (node (ref "R28") (pin "2") (pinfunction "2_2") (pintype "passive"))
    )
    (net (code "88") (name "Net-(J13-2)") (class "Default")
      (node (ref "J13") (pin "T") (pinfunction "2_T") (pintype "passive"))
      (node (ref "J7") (pin "1") (pinfunction "2_1") (pintype "passive"))
      (node (ref "R33") (pin "2") (pinfunction "2_2") (pintype "passive"))
      (node (ref "R34") (pin "2") (pinfunction "2_2") (pintype "passive"))
    )
    (net (code "89") (name "Net-(JP2-Pad1)") (class "Default")
      (node (ref "JP2") (pin "1") (pinfunction "1_1") (pintype "passive"))
      (node (ref "R9") (pin "1") (pinfunction "1_1") (pintype "passive"))
    )
    (net (code "90") (name "Net-(JP2-Pad2)") (class "Default")
      (node (ref "JP2") (pin "2") (pinfunction "2_2") (pintype "passive"))
      (node (ref "R8") (pin "1") (pinfunction "1_1") (pintype "passive"))
    )
    (net (code "91") (name "Net-(JP3-P$1)") (class "Default")
      (node (ref "JP3") (pin "1") (pinfunction "P$1_1") (pintype "bidirectional"))
      (node (ref "JP3") (pin "2") (pinfunction "P$2_2") (pintype "bidirectional"))
    )
    (net (code "92") (name "Net-(JP3-P$10)") (class "Default")
      (node (ref "F1") (pin "1") (pinfunction "1_1") (pintype "passive"))
      (node (ref "J1") (pin "1") (pinfunction "1_1") (pintype "passive"))
      (node (ref "JP3") (pin "10") (pinfunction "P$10_10") (pintype "bidirectional"))
      (node (ref "JP3") (pin "9") (pinfunction "P$9_9") (pintype "bidirectional"))
    )
    (net (code "93") (name "Net-(LED1-AG)") (class "Default")
      (node (ref "LED1") (pin "3") (pinfunction "AG_3") (pintype "passive"))
      (node (ref "R36") (pin "2") (pinfunction "2_2") (pintype "passive"))
    )
    (net (code "94") (name "Net-(LED1-AR)") (class "Default")
      (node (ref "LED1") (pin "1") (pinfunction "AR_1") (pintype "passive"))
      (node (ref "R37") (pin "1") (pinfunction "1_1") (pintype "passive"))
    )
    (net (code "95") (name "Net-(LED2-AG)") (class "Default")
      (node (ref "LED2") (pin "3") (pinfunction "AG_3") (pintype "passive"))
      (node (ref "R38") (pin "2") (pinfunction "2_2") (pintype "passive"))
    )
    (net (code "96") (name "Net-(LED2-AR)") (class "Default")
      (node (ref "LED2") (pin "1") (pinfunction "AR_1") (pintype "passive"))
      (node (ref "R39") (pin "1") (pinfunction "1_1") (pintype "passive"))
    )
    (net (code "97") (name "Net-(R26-Pad1)") (class "Default")
      (node (ref "R26") (pin "1") (pinfunction "1_1") (pintype "passive"))
      (node (ref "VR5") (pin "2") (pinfunction "2_2") (pintype "passive"))
    )
    (net (code "98") (name "Net-(VR5B-2)") (class "Default")
      (node (ref "R32") (pin "1") (pinfunction "1_1") (pintype "passive"))
      (node (ref "VR5") (pin "5") (pinfunction "2_5") (pintype "passive"))
    )
    (net (code "99") (name "POT1") (class "Default")
      (node (ref "C21") (pin "1") (pinfunction "1_1") (pintype "passive"))
      (node (ref "IC1") (pin "22") (pinfunction "PA6_22") (pintype "bidirectional"))
      (node (ref "VR1") (pin "2") (pinfunction "2_2") (pintype "passive"))
    )
    (net (code "100") (name "POT2") (class "Default")
      (node (ref "C22") (pin "1") (pinfunction "1_1") (pintype "passive"))
      (node (ref "IC1") (pin "23") (pinfunction "PA7_23") (pintype "bidirectional"))
      (node (ref "VR2") (pin "2") (pinfunction "2_2") (pintype "passive"))
    )
    (net (code "101") (name "POT3") (class "Default")
      (node (ref "C23") (pin "1") (pinfunction "1_1") (pintype "passive"))
      (node (ref "IC1") (pin "25") (pinfunction "PB0_25") (pintype "bidirectional"))
      (node (ref "VR3") (pin "2") (pinfunction "2_2") (pintype "passive"))
    )
    (net (code "102") (name "POT4") (class "Default")
      (node (ref "C24") (pin "1") (pinfunction "1_1") (pintype "passive"))
      (node (ref "IC1") (pin "26") (pinfunction "PB1_26") (pintype "bidirectional"))
      (node (ref "VR4") (pin "2") (pinfunction "2_2") (pintype "passive"))
    )
    (net (code "103") (name "RESET") (class "Default")
      (node (ref "IC1") (pin "7") (pinfunction "NRST_7") (pintype "bidirectional"))
      (node (ref "JP1") (pin "4") (pinfunction "4_4") (pintype "passive"))
    )
    (net (code "104") (name "ROW1") (class "Default")
      (node (ref "D1") (pin "C") (pinfunction "C_C") (pintype "passive"))
      (node (ref "D12") (pin "C") (pinfunction "C_C") (pintype "passive"))
      (node (ref "D15") (pin "C") (pinfunction "C_C") (pintype "passive"))
      (node (ref "D5") (pin "C") (pinfunction "C_C") (pintype "passive"))
      (node (ref "D8") (pin "C") (pinfunction "C_C") (pintype "passive"))
      (node (ref "IC1") (pin "52") (pinfunction "PC11_52") (pintype "bidirectional"))
    )
    (net (code "105") (name "ROW2") (class "Default")
      (node (ref "D10") (pin "C") (pinfunction "C_C") (pintype "passive"))
      (node (ref "D13") (pin "C") (pinfunction "C_C") (pintype "passive"))
      (node (ref "D17") (pin "C") (pinfunction "C_C") (pintype "passive"))
      (node (ref "D3") (pin "C") (pinfunction "C_C") (pintype "passive"))
      (node (ref "D6") (pin "C") (pinfunction "C_C") (pintype "passive"))
      (node (ref "IC1") (pin "53") (pinfunction "PC12_53") (pintype "bidirectional"))
    )
    (net (code "106") (name "ROW3") (class "Default")
      (node (ref "D11") (pin "C") (pinfunction "C_C") (pintype "passive"))
      (node (ref "D14") (pin "C") (pinfunction "C_C") (pintype "passive"))
      (node (ref "D16") (pin "C") (pinfunction "C_C") (pintype "passive"))
      (node (ref "D2") (pin "C") (pinfunction "C_C") (pintype "passive"))
      (node (ref "D4") (pin "C") (pinfunction "C_C") (pintype "passive"))
      (node (ref "D7") (pin "C") (pinfunction "C_C") (pintype "passive"))
      (node (ref "D9") (pin "C") (pinfunction "C_C") (pintype "passive"))
      (node (ref "IC1") (pin "54") (pinfunction "PD2_54") (pintype "bidirectional"))
    )
    (net (code "107") (name "RX") (class "Default")
      (node (ref "IC1") (pin "43") (pinfunction "PA10/USART1_RX_43") (pintype "bidirectional"))
      (node (ref "R9") (pin "2") (pinfunction "2_2") (pintype "passive"))
    )
    (net (code "108") (name "SPI2_CS") (class "Default")
      (node (ref "DIS1") (pin "7") (pinfunction "CS_7") (pintype "bidirectional"))
      (node (ref "IC1") (pin "33") (pinfunction "PB12/I2S2_WS_33") (pintype "bidirectional"))
    )
    (net (code "109") (name "SPI2_MISO") (class "Default")
      (node (ref "IC1") (pin "10") (pinfunction "PC2_10") (pintype "bidirectional"))
      (node (ref "PC2") (pin "1") (pinfunction "P_1") (pintype "passive"))
    )
    (net (code "110") (name "SPI2_MOSI") (class "Default")
      (node (ref "DIS1") (pin "4") (pinfunction "MOSI_4") (pintype "bidirectional"))
      (node (ref "IC1") (pin "9") (pinfunction "PC1_9") (pintype "bidirectional"))
    )
    (net (code "111") (name "SPI2_SCK") (class "Default")
      (node (ref "DIS1") (pin "3") (pinfunction "CLK_3") (pintype "bidirectional"))
      (node (ref "IC1") (pin "28") (pinfunction "PB10_28") (pintype "bidirectional"))
    )
    (net (code "112") (name "SWCLK") (class "Default")
      (node (ref "IC1") (pin "49") (pinfunction "PA14/JTCK-SWCLK_49") (pintype "bidirectional"))
      (node (ref "JP1") (pin "3") (pinfunction "3_3") (pintype "passive"))
    )
    (net (code "113") (name "SWDIO") (class "Default")
      (node (ref "IC1") (pin "46") (pinfunction "PA13/JTMS-SWDIO_46") (pintype "bidirectional"))
      (node (ref "JP1") (pin "2") (pinfunction "2_2") (pintype "passive"))
    )
    (net (code "114") (name "TACT1") (class "Default")
      (node (ref "C52") (pin "1") (pinfunction "1_1") (pintype "passive"))
      (node (ref "IC1") (pin "50") (pinfunction "PA15/JTDI_50") (pintype "bidirectional"))
      (node (ref "SW18") (pin "P1") (pinfunction "1_P1") (pintype "bidirectional"))
      (node (ref "SW18") (pin "P2") (pinfunction "1_P2") (pintype "bidirectional"))
    )
    (net (code "115") (name "TACT2") (class "Default")
      (node (ref "C53") (pin "1") (pinfunction "1_1") (pintype "passive"))
      (node (ref "IC1") (pin "51") (pinfunction "PC10_51") (pintype "bidirectional"))
      (node (ref "SW19") (pin "P1") (pinfunction "1_P1") (pintype "bidirectional"))
      (node (ref "SW19") (pin "P2") (pinfunction "1_P2") (pintype "bidirectional"))
    )
    (net (code "116") (name "TRIG_IN") (class "Default")
      (node (ref "IC1") (pin "29") (pinfunction "PB11_29") (pintype "bidirectional"))
      (node (ref "Q2") (pin "C") (pinfunction "C_C") (pintype "passive"))
      (node (ref "R18") (pin "1") (pinfunction "1_1") (pintype "passive"))
    )
    (net (code "117") (name "TRIG_OUT") (class "Default")
      (node (ref "IC1") (pin "27") (pinfunction "PB2_27") (pintype "bidirectional"))
      (node (ref "R19") (pin "1") (pinfunction "1_1") (pintype "passive"))
    )
    (net (code "118") (name "TX") (class "Default")
      (node (ref "IC1") (pin "42") (pinfunction "PA9/USART1_TX_42") (pintype "bidirectional"))
      (node (ref "R8") (pin "2") (pinfunction "2_2") (pintype "passive"))
    )
    (net (code "119") (name "V+") (class "Default")
      (node (ref "C10") (pin "1") (pinfunction "1_1") (pintype "passive"))
      (node (ref "C11") (pin "+") (pinfunction "+_+") (pintype "passive"))
      (node (ref "C48") (pin "1") (pinfunction "1_1") (pintype "passive"))
      (node (ref "C50") (pin "1") (pinfunction "1_1") (pintype "passive"))
      (node (ref "IC3") (pin "4") (pinfunction "V+_4") (pintype "bidirectional"))
      (node (ref "IC5") (pin "8") (pinfunction "V+_8") (pintype "bidirectional"))
      (node (ref "IC6") (pin "OUT") (pinfunction "OUT_OUT") (pintype "passive"))
      (node (ref "P2") (pin "1") (pinfunction "1_1") (pintype "bidirectional"))
    )
    (net (code "120") (name "V-") (class "Default")
      (node (ref "C16") (pin "2") (pinfunction "2_2") (pintype "passive"))
      (node (ref "C17") (pin "1") (pinfunction "1_1") (pintype "passive"))
      (node (ref "C18") (pin "1") (pinfunction "1_1") (pintype "passive"))
      (node (ref "C19") (pin "1") (pinfunction "1_1") (pintype "passive"))
      (node (ref "C20") (pin "-") (pinfunction "-_-") (pintype "passive"))
      (node (ref "C49") (pin "2") (pinfunction "2_2") (pintype "passive"))
      (node (ref "C51") (pin "2") (pinfunction "2_2") (pintype "passive"))
      (node (ref "IC3") (pin "11") (pinfunction "V-_11") (pintype "bidirectional"))
      (node (ref "IC5") (pin "4") (pinfunction "V-_4") (pintype "bidirectional"))
      (node (ref "L6") (pin "1") (pinfunction "1_1") (pintype "passive"))
      (node (ref "P6") (pin "1") (pinfunction "1_1") (pintype "bidirectional"))
      (node (ref "R35") (pin "2") (pinfunction "2_2") (pintype "passive"))
      (node (ref "R4") (pin "2") (pinfunction "2_2") (pintype "passive"))
    )
    (net (code "121") (name "VCC") (class "Default")
      (node (ref "C3") (pin "+") (pinfunction "+_+") (pintype "passive"))
      (node (ref "C4") (pin "+") (pinfunction "+_+") (pintype "passive"))
      (node (ref "C5") (pin "1") (pinfunction "1_1") (pintype "passive"))
      (node (ref "C6") (pin "1") (pinfunction "1_1") (pintype "passive"))
      (node (ref "D18") (pin "C") (pinfunction "C_C") (pintype "passive"))
      (node (ref "D19") (pin "3") (pinfunction "C_3") (pintype "passive"))
      (node (ref "L2") (pin "1") (pinfunction "1_1") (pintype "passive"))
      (node (ref "L3") (pin "1") (pinfunction "1_1") (pintype "passive"))
      (node (ref "L4") (pin "1") (pinfunction "1_1") (pintype "passive"))
      (node (ref "L7") (pin "2") (pinfunction "2_2") (pintype "passive"))
      (node (ref "R1") (pin "1") (pinfunction "1_1") (pintype "passive"))
      (node (ref "R1") (pin "2") (pinfunction "2_2") (pintype "passive"))
    )
    (net (code "122") (name "unconnected-(J1-Pad3)") (class "Default")
      (node (ref "J1") (pin "3") (pinfunction "3_3") (pintype "passive"))
    )
    (net (code "123") (name "unconnected-(J5-3-Pad2)") (class "Default")
      (node (ref "J5") (pin "2") (pinfunction "3_2") (pintype "passive"))
    )
    (net (code "124") (name "unconnected-(J6-3-Pad2)") (class "Default")
      (node (ref "J6") (pin "2") (pinfunction "3_2") (pintype "passive"))
    )
    (net (code "125") (name "unconnected-(J7-3-Pad2)") (class "Default")
      (node (ref "J7") (pin "2") (pinfunction "3_2") (pintype "passive"))
    )
    (net (code "126") (name "unconnected-(J11-3-PadTS)") (class "Default")
      (node (ref "J11") (pin "TS") (pinfunction "3_TS") (pintype "passive"))
    )
    (net (code "127") (name "unconnected-(J12-3-PadTS)") (class "Default")
      (node (ref "J12") (pin "TS") (pinfunction "3_TS") (pintype "passive"))
    )
    (net (code "128") (name "unconnected-(J13-3-PadTS)") (class "Default")
      (node (ref "J13") (pin "TS") (pinfunction "3_TS") (pintype "passive"))
    )
    (net (code "129") (name "unconnected-(J14-2-Pad1)") (class "Default")
      (node (ref "J14") (pin "1") (pinfunction "2_1") (pintype "passive"))
    )
    (net (code "130") (name "unconnected-(J14-3-Pad2)") (class "Default")
      (node (ref "J14") (pin "2") (pinfunction "3_2") (pintype "passive"))
    )
    (net (code "131") (name "unconnected-(J15-2-Pad1)") (class "Default")
      (node (ref "J15") (pin "1") (pinfunction "2_1") (pintype "passive"))
    )
    (net (code "132") (name "unconnected-(J15-3-Pad2)") (class "Default")
      (node (ref "J15") (pin "2") (pinfunction "3_2") (pintype "passive"))
    )
    (net (code "133") (name "unconnected-(J16-R-Pad2)") (class "Default")
      (node (ref "J16") (pin "2") (pinfunction "R_2") (pintype "passive"))
    )
    (net (code "134") (name "unconnected-(J16-RS-Pad3)") (class "Default")
      (node (ref "J16") (pin "3") (pinfunction "RS_3") (pintype "passive"))
    )
    (net (code "135") (name "unconnected-(J16-T-Pad5)") (class "Default")
      (node (ref "J16") (pin "5") (pinfunction "T_5") (pintype "passive"))
    )
    (net (code "136") (name "unconnected-(J16-TS-Pad4)") (class "Default")
      (node (ref "J16") (pin "4") (pinfunction "TS_4") (pintype "passive"))
    )
    (net (code "137") (name "unconnected-(J17-R-Pad2)") (class "Default")
      (node (ref "J17") (pin "2") (pinfunction "R_2") (pintype "passive"))
    )
    (net (code "138") (name "unconnected-(J17-RS-Pad3)") (class "Default")
      (node (ref "J17") (pin "3") (pinfunction "RS_3") (pintype "passive"))
    )
    (net (code "139") (name "unconnected-(J17-T-Pad5)") (class "Default")
      (node (ref "J17") (pin "5") (pinfunction "T_5") (pintype "passive"))
    )
    (net (code "140") (name "unconnected-(J17-TS-Pad4)") (class "Default")
      (node (ref "J17") (pin "4") (pinfunction "TS_4") (pintype "passive"))
    )
    (net (code "141") (name "unconnected-(P1-Pad1)") (class "Default")
      (node (ref "P1") (pin "1") (pinfunction "1_1") (pintype "bidirectional"))
    )
    (net (code "142") (name "unconnected-(P8-Pad1)") (class "Default")
      (node (ref "P8") (pin "1") (pinfunction "1_1") (pintype "bidirectional"))
    )
    (net (code "143") (name "unconnected-(P9-Pad1)") (class "Default")
      (node (ref "P9") (pin "1") (pinfunction "1_1") (pintype "bidirectional"))
    )
    (net (code "144") (name "unconnected-(P10-Pad1)") (class "Default")
      (node (ref "P10") (pin "1") (pinfunction "1_1") (pintype "bidirectional"))
    )
    (net (code "145") (name "unconnected-(P11-Pad1)") (class "Default")
      (node (ref "P11") (pin "1") (pinfunction "1_1") (pintype "bidirectional"))
    )
    (net (code "146") (name "unconnected-(P12-Pad1)") (class "Default")
      (node (ref "P12") (pin "1") (pinfunction "1_1") (pintype "bidirectional"))
    )
    (net (code "147") (name "unconnected-(P13-Pad1)") (class "Default")
      (node (ref "P13") (pin "1") (pinfunction "1_1") (pintype "bidirectional"))
    )
    (net (code "148") (name "unconnected-(P14-Pad1)") (class "Default")
      (node (ref "P14") (pin "1") (pinfunction "1_1") (pintype "bidirectional"))
    )
    (net (code "149") (name "unconnected-(P15-Pad1)") (class "Default")
      (node (ref "P15") (pin "1") (pinfunction "1_1") (pintype "bidirectional"))
    )
    (net (code "150") (name "unconnected-(P16-Pad1)") (class "Default")
      (node (ref "P16") (pin "1") (pinfunction "1_1") (pintype "bidirectional"))
    )
    (net (code "151") (name "unconnected-(P17-Pad1)") (class "Default")
      (node (ref "P17") (pin "1") (pinfunction "1_1") (pintype "bidirectional"))
    )
    (net (code "152") (name "unconnected-(P18-Pad1)") (class "Default")
      (node (ref "P18") (pin "1") (pinfunction "1_1") (pintype "bidirectional"))
    )
    (net (code "153") (name "unconnected-(P19-Pad1)") (class "Default")
      (node (ref "P19") (pin "1") (pinfunction "1_1") (pintype "bidirectional"))
    )
    (net (code "154") (name "unconnected-(P20-Pad1)") (class "Default")
      (node (ref "P20") (pin "1") (pinfunction "1_1") (pintype "bidirectional"))
    )
    (net (code "155") (name "unconnected-(P21-Pad1)") (class "Default")
      (node (ref "P21") (pin "1") (pinfunction "1_1") (pintype "bidirectional"))
    )
    (net (code "156") (name "unconnected-(P22-Pad1)") (class "Default")
      (node (ref "P22") (pin "1") (pinfunction "1_1") (pintype "bidirectional"))
    )
    (net (code "157") (name "unconnected-(P23-Pad1)") (class "Default")
      (node (ref "P23") (pin "1") (pinfunction "1_1") (pintype "bidirectional"))
    )
    (net (code "158") (name "unconnected-(P24-Pad1)") (class "Default")
      (node (ref "P24") (pin "1") (pinfunction "1_1") (pintype "bidirectional"))
    )
    (net (code "159") (name "unconnected-(P25-Pad1)") (class "Default")
      (node (ref "P25") (pin "1") (pinfunction "1_1") (pintype "bidirectional"))
    )
    (net (code "160") (name "unconnected-(P26-Pad1)") (class "Default")
      (node (ref "P26") (pin "1") (pinfunction "1_1") (pintype "bidirectional"))
    )
    (net (code "161") (name "unconnected-(P27-Pad1)") (class "Default")
      (node (ref "P27") (pin "1") (pinfunction "1_1") (pintype "bidirectional"))
    )
    (net (code "162") (name "unconnected-(P28-Pad1)") (class "Default")
      (node (ref "P28") (pin "1") (pinfunction "1_1") (pintype "bidirectional"))
    )
    (net (code "163") (name "unconnected-(P29-Pad1)") (class "Default")
      (node (ref "P29") (pin "1") (pinfunction "1_1") (pintype "bidirectional"))
    )
    (net (code "164") (name "unconnected-(P30-Pad1)") (class "Default")
      (node (ref "P30") (pin "1") (pinfunction "1_1") (pintype "bidirectional"))
    )
    (net (code "165") (name "unconnected-(P31-Pad1)") (class "Default")
      (node (ref "P31") (pin "1") (pinfunction "1_1") (pintype "bidirectional"))
    )
    (net (code "166") (name "unconnected-(P32-Pad1)") (class "Default")
      (node (ref "P32") (pin "1") (pinfunction "1_1") (pintype "bidirectional"))
    )
    (net (code "167") (name "unconnected-(P33-Pad1)") (class "Default")
      (node (ref "P33") (pin "1") (pinfunction "1_1") (pintype "bidirectional"))
    )
    (net (code "168") (name "unconnected-(P34-Pad1)") (class "Default")
      (node (ref "P34") (pin "1") (pinfunction "1_1") (pintype "bidirectional"))
    )
    (net (code "169") (name "unconnected-(P35-Pad1)") (class "Default")
      (node (ref "P35") (pin "1") (pinfunction "1_1") (pintype "bidirectional"))
    )
    (net (code "170") (name "unconnected-(P36-Pad1)") (class "Default")
      (node (ref "P36") (pin "1") (pinfunction "1_1") (pintype "bidirectional"))
    )
    (net (code "171") (name "unconnected-(P37-Pad1)") (class "Default")
      (node (ref "P37") (pin "1") (pinfunction "1_1") (pintype "bidirectional"))
    )
    (net (code "172") (name "unconnected-(P38-Pad1)") (class "Default")
      (node (ref "P38") (pin "1") (pinfunction "1_1") (pintype "bidirectional"))
    )
    (net (code "173") (name "unconnected-(P39-Pad1)") (class "Default")
      (node (ref "P39") (pin "1") (pinfunction "1_1") (pintype "bidirectional"))
    )
    (net (code "174") (name "unconnected-(P40-Pad1)") (class "Default")
      (node (ref "P40") (pin "1") (pinfunction "1_1") (pintype "bidirectional"))
    )
    (net (code "175") (name "unconnected-(P41-Pad1)") (class "Default")
      (node (ref "P41") (pin "1") (pinfunction "1_1") (pintype "bidirectional"))
    )
    (net (code "176") (name "unconnected-(P42-Pad1)") (class "Default")
      (node (ref "P42") (pin "1") (pinfunction "1_1") (pintype "bidirectional"))
    )
    (net (code "177") (name "unconnected-(P43-Pad1)") (class "Default")
      (node (ref "P43") (pin "1") (pinfunction "1_1") (pintype "bidirectional"))
    )
    (net (code "178") (name "unconnected-(P44-Pad1)") (class "Default")
      (node (ref "P44") (pin "1") (pinfunction "1_1") (pintype "bidirectional"))
    )
    (net (code "179") (name "unconnected-(P45-Pad1)") (class "Default")
      (node (ref "P45") (pin "1") (pinfunction "1_1") (pintype "bidirectional"))
    )
    (net (code "180") (name "unconnected-(P46-Pad1)") (class "Default")
      (node (ref "P46") (pin "1") (pinfunction "1_1") (pintype "bidirectional"))
    )
    (net (code "181") (name "unconnected-(P47-Pad1)") (class "Default")
      (node (ref "P47") (pin "1") (pinfunction "1_1") (pintype "bidirectional"))
    )
    (net (code "182") (name "unconnected-(P48-Pad1)") (class "Default")
      (node (ref "P48") (pin "1") (pinfunction "1_1") (pintype "bidirectional"))
    )
    (net (code "183") (name "unconnected-(P49-Pad1)") (class "Default")
      (node (ref "P49") (pin "1") (pinfunction "1_1") (pintype "bidirectional"))
    )
    (net (code "184") (name "unconnected-(P50-Pad1)") (class "Default")
      (node (ref "P50") (pin "1") (pinfunction "1_1") (pintype "bidirectional"))
    )
    (net (code "185") (name "unconnected-(P51-Pad1)") (class "Default")
      (node (ref "P51") (pin "1") (pinfunction "1_1") (pintype "bidirectional"))
    )
    (net (code "186") (name "unconnected-(P52-Pad1)") (class "Default")
      (node (ref "P52") (pin "1") (pinfunction "1_1") (pintype "bidirectional"))
    )
    (net (code "187") (name "unconnected-(P53-Pad1)") (class "Default")
      (node (ref "P53") (pin "1") (pinfunction "1_1") (pintype "bidirectional"))
    )
    (net (code "188") (name "unconnected-(P54-Pad1)") (class "Default")
      (node (ref "P54") (pin "1") (pinfunction "1_1") (pintype "bidirectional"))
    )
    (net (code "189") (name "unconnected-(P55-Pad1)") (class "Default")
      (node (ref "P55") (pin "1") (pinfunction "1_1") (pintype "bidirectional"))
    )
    (net (code "190") (name "unconnected-(P56-Pad1)") (class "Default")
      (node (ref "P56") (pin "1") (pinfunction "1_1") (pintype "bidirectional"))
    )
    (net (code "191") (name "unconnected-(P57-Pad1)") (class "Default")
      (node (ref "P57") (pin "1") (pinfunction "1_1") (pintype "bidirectional"))
    )
    (net (code "192") (name "unconnected-(P58-Pad1)") (class "Default")
      (node (ref "P58") (pin "1") (pinfunction "1_1") (pintype "bidirectional"))
    )
    (net (code "193") (name "unconnected-(P59-Pad1)") (class "Default")
      (node (ref "P59") (pin "1") (pinfunction "1_1") (pintype "bidirectional"))
    )
    (net (code "194") (name "unconnected-(P60-Pad1)") (class "Default")
      (node (ref "P60") (pin "1") (pinfunction "1_1") (pintype "bidirectional"))
    )
    (net (code "195") (name "unconnected-(P61-Pad1)") (class "Default")
      (node (ref "P61") (pin "1") (pinfunction "1_1") (pintype "bidirectional"))
    )
    (net (code "196") (name "unconnected-(P62-Pad1)") (class "Default")
      (node (ref "P62") (pin "1") (pinfunction "1_1") (pintype "bidirectional"))
    )
    (net (code "197") (name "unconnected-(P63-Pad1)") (class "Default")
      (node (ref "P63") (pin "1") (pinfunction "1_1") (pintype "bidirectional"))
    )
    (net (code "198") (name "unconnected-(P64-Pad1)") (class "Default")
      (node (ref "P64") (pin "1") (pinfunction "1_1") (pintype "bidirectional"))
    )
    (net (code "199") (name "unconnected-(P65-Pad1)") (class "Default")
      (node (ref "P65") (pin "1") (pinfunction "1_1") (pintype "bidirectional"))
    )
    (net (code "200") (name "unconnected-(P66-Pad1)") (class "Default")
      (node (ref "P66") (pin "1") (pinfunction "1_1") (pintype "bidirectional"))
    )
    (net (code "201") (name "unconnected-(P67-Pad1)") (class "Default")
      (node (ref "P67") (pin "1") (pinfunction "1_1") (pintype "bidirectional"))
    )
    (net (code "202") (name "unconnected-(P68-Pad1)") (class "Default")
      (node (ref "P68") (pin "1") (pinfunction "1_1") (pintype "bidirectional"))
    )
    (net (code "203") (name "unconnected-(P69-Pad1)") (class "Default")
      (node (ref "P69") (pin "1") (pinfunction "1_1") (pintype "bidirectional"))
    )
    (net (code "204") (name "unconnected-(P70-Pad1)") (class "Default")
      (node (ref "P70") (pin "1") (pinfunction "1_1") (pintype "bidirectional"))
    )
    (net (code "205") (name "unconnected-(P71-Pad1)") (class "Default")
      (node (ref "P71") (pin "1") (pinfunction "1_1") (pintype "bidirectional"))
    )
    (net (code "206") (name "unconnected-(P72-Pad1)") (class "Default")
      (node (ref "P72") (pin "1") (pinfunction "1_1") (pintype "bidirectional"))
    )
    (net (code "207") (name "unconnected-(P73-Pad1)") (class "Default")
      (node (ref "P73") (pin "1") (pinfunction "1_1") (pintype "bidirectional"))
    )
    (net (code "208") (name "unconnected-(P74-Pad1)") (class "Default")
      (node (ref "P74") (pin "1") (pinfunction "1_1") (pintype "bidirectional"))
    )
    (net (code "209") (name "unconnected-(P75-Pad1)") (class "Default")
      (node (ref "P75") (pin "1") (pinfunction "1_1") (pintype "bidirectional"))
    )
    (net (code "210") (name "unconnected-(P76-Pad1)") (class "Default")
      (node (ref "P76") (pin "1") (pinfunction "1_1") (pintype "bidirectional"))
    )
    (net (code "211") (name "unconnected-(P77-Pad1)") (class "Default")
      (node (ref "P77") (pin "1") (pinfunction "1_1") (pintype "bidirectional"))
    )
    (net (code "212") (name "unconnected-(P78-Pad1)") (class "Default")
      (node (ref "P78") (pin "1") (pinfunction "1_1") (pintype "bidirectional"))
    )
    (net (code "213") (name "unconnected-(P79-Pad1)") (class "Default")
      (node (ref "P79") (pin "1") (pinfunction "1_1") (pintype "bidirectional"))
    )
    (net (code "214") (name "unconnected-(P80-Pad1)") (class "Default")
      (node (ref "P80") (pin "1") (pinfunction "1_1") (pintype "bidirectional"))
    )
    (net (code "215") (name "unconnected-(P81-Pad1)") (class "Default")
      (node (ref "P81") (pin "1") (pinfunction "1_1") (pintype "bidirectional"))
    )
    (net (code "216") (name "unconnected-(P82-Pad1)") (class "Default")
      (node (ref "P82") (pin "1") (pinfunction "1_1") (pintype "bidirectional"))
    )
    (net (code "217") (name "unconnected-(P83-Pad1)") (class "Default")
      (node (ref "P83") (pin "1") (pinfunction "1_1") (pintype "bidirectional"))
    )
    (net (code "218") (name "unconnected-(P84-Pad1)") (class "Default")
      (node (ref "P84") (pin "1") (pinfunction "1_1") (pintype "bidirectional"))
    )
    (net (code "219") (name "unconnected-(P85-Pad1)") (class "Default")
      (node (ref "P85") (pin "1") (pinfunction "1_1") (pintype "bidirectional"))
    )
    (net (code "220") (name "unconnected-(P86-Pad1)") (class "Default")
      (node (ref "P86") (pin "1") (pinfunction "1_1") (pintype "bidirectional"))
    )
    (net (code "221") (name "unconnected-(P87-Pad1)") (class "Default")
      (node (ref "P87") (pin "1") (pinfunction "1_1") (pintype "bidirectional"))
    )
    (net (code "222") (name "unconnected-(P88-Pad1)") (class "Default")
      (node (ref "P88") (pin "1") (pinfunction "1_1") (pintype "bidirectional"))
    )
    (net (code "223") (name "unconnected-(P89-Pad1)") (class "Default")
      (node (ref "P89") (pin "1") (pinfunction "1_1") (pintype "bidirectional"))
    )
    (net (code "224") (name "unconnected-(P90-Pad1)") (class "Default")
      (node (ref "P90") (pin "1") (pinfunction "1_1") (pintype "bidirectional"))
    )
    (net (code "225") (name "unconnected-(P91-Pad1)") (class "Default")
      (node (ref "P91") (pin "1") (pinfunction "1_1") (pintype "bidirectional"))
    )
    (net (code "226") (name "unconnected-(P92-Pad1)") (class "Default")
      (node (ref "P92") (pin "1") (pinfunction "1_1") (pintype "bidirectional"))
    )
    (net (code "227") (name "unconnected-(P93-Pad1)") (class "Default")
      (node (ref "P93") (pin "1") (pinfunction "1_1") (pintype "bidirectional"))
    )
    (net (code "228") (name "unconnected-(P94-Pad1)") (class "Default")
      (node (ref "P94") (pin "1") (pinfunction "1_1") (pintype "bidirectional"))
    )
    (net (code "229") (name "unconnected-(P95-Pad1)") (class "Default")
      (node (ref "P95") (pin "1") (pinfunction "1_1") (pintype "bidirectional"))
    )
    (net (code "230") (name "unconnected-(P96-Pad1)") (class "Default")
      (node (ref "P96") (pin "1") (pinfunction "1_1") (pintype "bidirectional"))
    )
    (net (code "231") (name "unconnected-(P97-Pad1)") (class "Default")
      (node (ref "P97") (pin "1") (pinfunction "1_1") (pintype "bidirectional"))
    )
    (net (code "232") (name "unconnected-(P98-Pad1)") (class "Default")
      (node (ref "P98") (pin "1") (pinfunction "1_1") (pintype "bidirectional"))
    )
    (net (code "233") (name "unconnected-(P99-Pad1)") (class "Default")
      (node (ref "P99") (pin "1") (pinfunction "1_1") (pintype "bidirectional"))
    )
    (net (code "234") (name "unconnected-(P100-Pad1)") (class "Default")
      (node (ref "P100") (pin "1") (pinfunction "1_1") (pintype "bidirectional"))
    )
    (net (code "235") (name "unconnected-(P101-Pad1)") (class "Default")
      (node (ref "P101") (pin "1") (pinfunction "1_1") (pintype "bidirectional"))
    )
    (net (code "236") (name "unconnected-(P102-Pad1)") (class "Default")
      (node (ref "P102") (pin "1") (pinfunction "1_1") (pintype "bidirectional"))
    )
    (net (code "237") (name "unconnected-(P103-Pad1)") (class "Default")
      (node (ref "P103") (pin "1") (pinfunction "1_1") (pintype "bidirectional"))
    )
    (net (code "238") (name "unconnected-(P104-Pad1)") (class "Default")
      (node (ref "P104") (pin "1") (pinfunction "1_1") (pintype "bidirectional"))
    )
    (net (code "239") (name "unconnected-(P105-Pad1)") (class "Default")
      (node (ref "P105") (pin "1") (pinfunction "1_1") (pintype "bidirectional"))
    )
    (net (code "240") (name "unconnected-(P106-Pad1)") (class "Default")
      (node (ref "P106") (pin "1") (pinfunction "1_1") (pintype "bidirectional"))
    )
    (net (code "241") (name "unconnected-(P107-Pad1)") (class "Default")
      (node (ref "P107") (pin "1") (pinfunction "1_1") (pintype "bidirectional"))
    )
    (net (code "242") (name "unconnected-(P108-Pad1)") (class "Default")
      (node (ref "P108") (pin "1") (pinfunction "1_1") (pintype "bidirectional"))
    )
    (net (code "243") (name "unconnected-(P109-Pad1)") (class "Default")
      (node (ref "P109") (pin "1") (pinfunction "1_1") (pintype "bidirectional"))
    )
    (net (code "244") (name "unconnected-(P110-Pad1)") (class "Default")
      (node (ref "P110") (pin "1") (pinfunction "1_1") (pintype "bidirectional"))
    )
    (net (code "245") (name "unconnected-(P111-Pad1)") (class "Default")
      (node (ref "P111") (pin "1") (pinfunction "1_1") (pintype "bidirectional"))
    )
    (net (code "246") (name "unconnected-(P112-Pad1)") (class "Default")
      (node (ref "P112") (pin "1") (pinfunction "1_1") (pintype "bidirectional"))
    )
    (net (code "247") (name "unconnected-(P113-Pad1)") (class "Default")
      (node (ref "P113") (pin "1") (pinfunction "1_1") (pintype "bidirectional"))
    )
    (net (code "248") (name "unconnected-(P114-Pad1)") (class "Default")
      (node (ref "P114") (pin "1") (pinfunction "1_1") (pintype "bidirectional"))
    )
    (net (code "249") (name "unconnected-(P115-Pad1)") (class "Default")
      (node (ref "P115") (pin "1") (pinfunction "1_1") (pintype "bidirectional"))
    )
    (net (code "250") (name "unconnected-(P116-Pad1)") (class "Default")
      (node (ref "P116") (pin "1") (pinfunction "1_1") (pintype "bidirectional"))
    )
    (net (code "251") (name "unconnected-(P117-Pad1)") (class "Default")
      (node (ref "P117") (pin "1") (pinfunction "1_1") (pintype "bidirectional"))
    )
    (net (code "252") (name "unconnected-(P118-Pad1)") (class "Default")
      (node (ref "P118") (pin "1") (pinfunction "1_1") (pintype "bidirectional"))
    )
    (net (code "253") (name "unconnected-(P119-Pad1)") (class "Default")
      (node (ref "P119") (pin "1") (pinfunction "1_1") (pintype "bidirectional"))
    )
    (net (code "254") (name "unconnected-(P120-Pad1)") (class "Default")
      (node (ref "P120") (pin "1") (pinfunction "1_1") (pintype "bidirectional"))
    )
    (net (code "255") (name "unconnected-(P121-Pad1)") (class "Default")
      (node (ref "P121") (pin "1") (pinfunction "1_1") (pintype "bidirectional"))
    )
    (net (code "256") (name "unconnected-(P122-Pad1)") (class "Default")
      (node (ref "P122") (pin "1") (pinfunction "1_1") (pintype "bidirectional"))
    )
    (net (code "257") (name "unconnected-(P123-Pad1)") (class "Default")
      (node (ref "P123") (pin "1") (pinfunction "1_1") (pintype "bidirectional"))
    )
    (net (code "258") (name "unconnected-(P124-Pad1)") (class "Default")
      (node (ref "P124") (pin "1") (pinfunction "1_1") (pintype "bidirectional"))
    )
    (net (code "259") (name "unconnected-(P125-Pad1)") (class "Default")
      (node (ref "P125") (pin "1") (pinfunction "1_1") (pintype "bidirectional"))
    )
    (net (code "260") (name "unconnected-(P126-Pad1)") (class "Default")
      (node (ref "P126") (pin "1") (pinfunction "1_1") (pintype "bidirectional"))
    )
    (net (code "261") (name "unconnected-(P127-Pad1)") (class "Default")
      (node (ref "P127") (pin "1") (pinfunction "1_1") (pintype "bidirectional"))
    )
    (net (code "262") (name "unconnected-(P128-Pad1)") (class "Default")
      (node (ref "P128") (pin "1") (pinfunction "1_1") (pintype "bidirectional"))
    )
    (net (code "263") (name "unconnected-(P129-Pad1)") (class "Default")
      (node (ref "P129") (pin "1") (pinfunction "1_1") (pintype "bidirectional"))
    )
    (net (code "264") (name "unconnected-(P130-Pad1)") (class "Default")
      (node (ref "P130") (pin "1") (pinfunction "1_1") (pintype "bidirectional"))
    )
    (net (code "265") (name "unconnected-(P131-Pad1)") (class "Default")
      (node (ref "P131") (pin "1") (pinfunction "1_1") (pintype "bidirectional"))
    )
    (net (code "266") (name "unconnected-(P132-Pad1)") (class "Default")
      (node (ref "P132") (pin "1") (pinfunction "1_1") (pintype "bidirectional"))
    )
    (net (code "267") (name "unconnected-(P133-Pad1)") (class "Default")
      (node (ref "P133") (pin "1") (pinfunction "1_1") (pintype "bidirectional"))
    )
    (net (code "268") (name "unconnected-(P134-Pad1)") (class "Default")
      (node (ref "P134") (pin "1") (pinfunction "1_1") (pintype "bidirectional"))
    )
    (net (code "269") (name "unconnected-(P135-Pad1)") (class "Default")
      (node (ref "P135") (pin "1") (pinfunction "1_1") (pintype "bidirectional"))
    )
    (net (code "270") (name "unconnected-(P136-Pad1)") (class "Default")
      (node (ref "P136") (pin "1") (pinfunction "1_1") (pintype "bidirectional"))
    )
    (net (code "271") (name "unconnected-(P137-Pad1)") (class "Default")
      (node (ref "P137") (pin "1") (pinfunction "1_1") (pintype "bidirectional"))
    )
    (net (code "272") (name "unconnected-(P138-Pad1)") (class "Default")
      (node (ref "P138") (pin "1") (pinfunction "1_1") (pintype "bidirectional"))
    )
    (net (code "273") (name "unconnected-(P139-Pad1)") (class "Default")
      (node (ref "P139") (pin "1") (pinfunction "1_1") (pintype "bidirectional"))
    )
    (net (code "274") (name "unconnected-(P140-Pad1)") (class "Default")
      (node (ref "P140") (pin "1") (pinfunction "1_1") (pintype "bidirectional"))
    )
    (net (code "275") (name "unconnected-(P141-Pad1)") (class "Default")
      (node (ref "P141") (pin "1") (pinfunction "1_1") (pintype "bidirectional"))
    )
    (net (code "276") (name "unconnected-(P142-Pad1)") (class "Default")
      (node (ref "P142") (pin "1") (pinfunction "1_1") (pintype "bidirectional"))
    )
    (net (code "277") (name "unconnected-(P143-Pad1)") (class "Default")
      (node (ref "P143") (pin "1") (pinfunction "1_1") (pintype "bidirectional"))
    )
    (net (code "278") (name "unconnected-(P144-Pad1)") (class "Default")
      (node (ref "P144") (pin "1") (pinfunction "1_1") (pintype "bidirectional"))
    )
    (net (code "279") (name "unconnected-(P145-Pad1)") (class "Default")
      (node (ref "P145") (pin "1") (pinfunction "1_1") (pintype "bidirectional"))
    )
    (net (code "280") (name "unconnected-(P146-Pad1)") (class "Default")
      (node (ref "P146") (pin "1") (pinfunction "1_1") (pintype "bidirectional"))
    )
    (net (code "281") (name "unconnected-(P147-Pad1)") (class "Default")
      (node (ref "P147") (pin "1") (pinfunction "1_1") (pintype "bidirectional"))
    )
    (net (code "282") (name "unconnected-(P148-Pad1)") (class "Default")
      (node (ref "P148") (pin "1") (pinfunction "1_1") (pintype "bidirectional"))
    )
    (net (code "283") (name "unconnected-(P149-Pad1)") (class "Default")
      (node (ref "P149") (pin "1") (pinfunction "1_1") (pintype "bidirectional"))
    )
    (net (code "284") (name "unconnected-(P150-Pad1)") (class "Default")
      (node (ref "P150") (pin "1") (pinfunction "1_1") (pintype "bidirectional"))
    )
    (net (code "285") (name "unconnected-(P151-Pad1)") (class "Default")
      (node (ref "P151") (pin "1") (pinfunction "1_1") (pintype "bidirectional"))
    )
    (net (code "286") (name "unconnected-(P152-Pad1)") (class "Default")
      (node (ref "P152") (pin "1") (pinfunction "1_1") (pintype "bidirectional"))
    )
    (net (code "287") (name "unconnected-(P153-Pad1)") (class "Default")
      (node (ref "P153") (pin "1") (pinfunction "1_1") (pintype "bidirectional"))
    )
    (net (code "288") (name "unconnected-(P154-Pad1)") (class "Default")
      (node (ref "P154") (pin "1") (pinfunction "1_1") (pintype "bidirectional"))
    )
    (net (code "289") (name "unconnected-(P155-Pad1)") (class "Default")
      (node (ref "P155") (pin "1") (pinfunction "1_1") (pintype "bidirectional"))
    )
    (net (code "290") (name "unconnected-(P156-Pad1)") (class "Default")
      (node (ref "P156") (pin "1") (pinfunction "1_1") (pintype "bidirectional"))
    )
    (net (code "291") (name "unconnected-(P157-Pad1)") (class "Default")
      (node (ref "P157") (pin "1") (pinfunction "1_1") (pintype "bidirectional"))
    )
    (net (code "292") (name "unconnected-(P158-Pad1)") (class "Default")
      (node (ref "P158") (pin "1") (pinfunction "1_1") (pintype "bidirectional"))
    )
    (net (code "293") (name "unconnected-(P159-Pad1)") (class "Default")
      (node (ref "P159") (pin "1") (pinfunction "1_1") (pintype "bidirectional"))
    )
    (net (code "294") (name "unconnected-(P160-Pad1)") (class "Default")
      (node (ref "P160") (pin "1") (pinfunction "1_1") (pintype "bidirectional"))
    )
    (net (code "295") (name "unconnected-(P161-Pad1)") (class "Default")
      (node (ref "P161") (pin "1") (pinfunction "1_1") (pintype "bidirectional"))
    )
    (net (code "296") (name "unconnected-(P162-Pad1)") (class "Default")
      (node (ref "P162") (pin "1") (pinfunction "1_1") (pintype "bidirectional"))
    )
    (net (code "297") (name "unconnected-(P163-Pad1)") (class "Default")
      (node (ref "P163") (pin "1") (pinfunction "1_1") (pintype "bidirectional"))
    )
    (net (code "298") (name "unconnected-(P164-Pad1)") (class "Default")
      (node (ref "P164") (pin "1") (pinfunction "1_1") (pintype "bidirectional"))
    )
    (net (code "299") (name "unconnected-(P165-Pad1)") (class "Default")
      (node (ref "P165") (pin "1") (pinfunction "1_1") (pintype "bidirectional"))
    )
    (net (code "300") (name "unconnected-(P166-Pad1)") (class "Default")
      (node (ref "P166") (pin "1") (pinfunction "1_1") (pintype "bidirectional"))
    )
    (net (code "301") (name "unconnected-(P167-Pad1)") (class "Default")
      (node (ref "P167") (pin "1") (pinfunction "1_1") (pintype "bidirectional"))
    )
    (net (code "302") (name "unconnected-(P168-Pad1)") (class "Default")
      (node (ref "P168") (pin "1") (pinfunction "1_1") (pintype "bidirectional"))
    )
    (net (code "303") (name "unconnected-(P169-Pad1)") (class "Default")
      (node (ref "P169") (pin "1") (pinfunction "1_1") (pintype "bidirectional"))
    )
    (net (code "304") (name "unconnected-(P170-Pad1)") (class "Default")
      (node (ref "P170") (pin "1") (pinfunction "1_1") (pintype "bidirectional"))
    )
    (net (code "305") (name "unconnected-(P171-Pad1)") (class "Default")
      (node (ref "P171") (pin "1") (pinfunction "1_1") (pintype "bidirectional"))
    )
    (net (code "306") (name "unconnected-(P172-Pad1)") (class "Default")
      (node (ref "P172") (pin "1") (pinfunction "1_1") (pintype "bidirectional"))
    )
    (net (code "307") (name "unconnected-(P173-Pad1)") (class "Default")
      (node (ref "P173") (pin "1") (pinfunction "1_1") (pintype "bidirectional"))
    )
    (net (code "308") (name "unconnected-(P174-Pad1)") (class "Default")
      (node (ref "P174") (pin "1") (pinfunction "1_1") (pintype "bidirectional"))
    )
    (net (code "309") (name "unconnected-(P175-Pad1)") (class "Default")
      (node (ref "P175") (pin "1") (pinfunction "1_1") (pintype "bidirectional"))
    )
    (net (code "310") (name "unconnected-(P176-Pad1)") (class "Default")
      (node (ref "P176") (pin "1") (pinfunction "1_1") (pintype "bidirectional"))
    )
    (net (code "311") (name "unconnected-(P177-Pad1)") (class "Default")
      (node (ref "P177") (pin "1") (pinfunction "1_1") (pintype "bidirectional"))
    )
    (net (code "312") (name "unconnected-(P178-Pad1)") (class "Default")
      (node (ref "P178") (pin "1") (pinfunction "1_1") (pintype "bidirectional"))
    )
    (net (code "313") (name "unconnected-(P179-Pad1)") (class "Default")
      (node (ref "P179") (pin "1") (pinfunction "1_1") (pintype "bidirectional"))
    )
    (net (code "314") (name "unconnected-(P180-Pad1)") (class "Default")
      (node (ref "P180") (pin "1") (pinfunction "1_1") (pintype "bidirectional"))
    )
    (net (code "315") (name "unconnected-(P181-Pad1)") (class "Default")
      (node (ref "P181") (pin "1") (pinfunction "1_1") (pintype "bidirectional"))
    )
    (net (code "316") (name "unconnected-(P182-Pad1)") (class "Default")
      (node (ref "P182") (pin "1") (pinfunction "1_1") (pintype "bidirectional"))
    )
    (net (code "317") (name "unconnected-(P183-Pad1)") (class "Default")
      (node (ref "P183") (pin "1") (pinfunction "1_1") (pintype "bidirectional"))
    )
    (net (code "318") (name "unconnected-(P184-Pad1)") (class "Default")
      (node (ref "P184") (pin "1") (pinfunction "1_1") (pintype "bidirectional"))
    )
    (net (code "319") (name "unconnected-(P185-Pad1)") (class "Default")
      (node (ref "P185") (pin "1") (pinfunction "1_1") (pintype "bidirectional"))
    )
    (net (code "320") (name "unconnected-(P186-Pad1)") (class "Default")
      (node (ref "P186") (pin "1") (pinfunction "1_1") (pintype "bidirectional"))
    )
    (net (code "321") (name "unconnected-(P187-Pad1)") (class "Default")
      (node (ref "P187") (pin "1") (pinfunction "1_1") (pintype "bidirectional"))
    )
    (net (code "322") (name "unconnected-(P188-Pad1)") (class "Default")
      (node (ref "P188") (pin "1") (pinfunction "1_1") (pintype "bidirectional"))
    )
    (net (code "323") (name "unconnected-(P189-Pad1)") (class "Default")
      (node (ref "P189") (pin "1") (pinfunction "1_1") (pintype "bidirectional"))
    )
    (net (code "324") (name "unconnected-(P190-Pad1)") (class "Default")
      (node (ref "P190") (pin "1") (pinfunction "1_1") (pintype "bidirectional"))
    )
    (net (code "325") (name "unconnected-(P191-Pad1)") (class "Default")
      (node (ref "P191") (pin "1") (pinfunction "1_1") (pintype "bidirectional"))
    )
    (net (code "326") (name "unconnected-(P192-Pad1)") (class "Default")
      (node (ref "P192") (pin "1") (pinfunction "1_1") (pintype "bidirectional"))
    )
    (net (code "327") (name "unconnected-(P193-Pad1)") (class "Default")
      (node (ref "P193") (pin "1") (pinfunction "1_1") (pintype "bidirectional"))
    )
    (net (code "328") (name "unconnected-(P194-Pad1)") (class "Default")
      (node (ref "P194") (pin "1") (pinfunction "1_1") (pintype "bidirectional"))
    )
    (net (code "329") (name "unconnected-(P195-Pad1)") (class "Default")
      (node (ref "P195") (pin "1") (pinfunction "1_1") (pintype "bidirectional"))
    )
    (net (code "330") (name "unconnected-(P196-Pad1)") (class "Default")
      (node (ref "P196") (pin "1") (pinfunction "1_1") (pintype "bidirectional"))
    )
    (net (code "331") (name "unconnected-(P197-Pad1)") (class "Default")
      (node (ref "P197") (pin "1") (pinfunction "1_1") (pintype "bidirectional"))
    )
    (net (code "332") (name "unconnected-(P198-Pad1)") (class "Default")
      (node (ref "P198") (pin "1") (pinfunction "1_1") (pintype "bidirectional"))
    )
    (net (code "333") (name "unconnected-(P199-Pad1)") (class "Default")
      (node (ref "P199") (pin "1") (pinfunction "1_1") (pintype "bidirectional"))
    )
    (net (code "334") (name "unconnected-(P200-Pad1)") (class "Default")
      (node (ref "P200") (pin "1") (pinfunction "1_1") (pintype "bidirectional"))
    )
    (net (code "335") (name "unconnected-(P201-Pad1)") (class "Default")
      (node (ref "P201") (pin "1") (pinfunction "1_1") (pintype "bidirectional"))
    )
    (net (code "336") (name "unconnected-(P202-Pad1)") (class "Default")
      (node (ref "P202") (pin "1") (pinfunction "1_1") (pintype "bidirectional"))
    )
    (net (code "337") (name "unconnected-(P203-Pad1)") (class "Default")
      (node (ref "P203") (pin "1") (pinfunction "1_1") (pintype "bidirectional"))
    )
    (net (code "338") (name "unconnected-(P204-Pad1)") (class "Default")
      (node (ref "P204") (pin "1") (pinfunction "1_1") (pintype "bidirectional"))
    )
    (net (code "339") (name "unconnected-(P205-Pad1)") (class "Default")
      (node (ref "P205") (pin "1") (pinfunction "1_1") (pintype "bidirectional"))
    )
    (net (code "340") (name "unconnected-(P206-Pad1)") (class "Default")
      (node (ref "P206") (pin "1") (pinfunction "1_1") (pintype "bidirectional"))
    )
    (net (code "341") (name "unconnected-(P207-Pad1)") (class "Default")
      (node (ref "P207") (pin "1") (pinfunction "1_1") (pintype "bidirectional"))
    )
    (net (code "342") (name "unconnected-(P208-Pad1)") (class "Default")
      (node (ref "P208") (pin "1") (pinfunction "1_1") (pintype "bidirectional"))
    )
    (net (code "343") (name "unconnected-(P209-Pad1)") (class "Default")
      (node (ref "P209") (pin "1") (pinfunction "1_1") (pintype "bidirectional"))
    )
    (net (code "344") (name "unconnected-(P210-Pad1)") (class "Default")
      (node (ref "P210") (pin "1") (pinfunction "1_1") (pintype "bidirectional"))
    )
    (net (code "345") (name "unconnected-(P211-Pad1)") (class "Default")
      (node (ref "P211") (pin "1") (pinfunction "1_1") (pintype "bidirectional"))
    )
    (net (code "346") (name "unconnected-(P212-Pad1)") (class "Default")
      (node (ref "P212") (pin "1") (pinfunction "1_1") (pintype "bidirectional"))
    )
    (net (code "347") (name "unconnected-(P213-Pad1)") (class "Default")
      (node (ref "P213") (pin "1") (pinfunction "1_1") (pintype "bidirectional"))
    )
    (net (code "348") (name "unconnected-(P214-Pad1)") (class "Default")
      (node (ref "P214") (pin "1") (pinfunction "1_1") (pintype "bidirectional"))
    )
    (net (code "349") (name "unconnected-(P215-Pad1)") (class "Default")
      (node (ref "P215") (pin "1") (pinfunction "1_1") (pintype "bidirectional"))
    )
    (net (code "350") (name "unconnected-(P216-Pad1)") (class "Default")
      (node (ref "P216") (pin "1") (pinfunction "1_1") (pintype "bidirectional"))
    )
    (net (code "351") (name "unconnected-(P217-Pad1)") (class "Default")
      (node (ref "P217") (pin "1") (pinfunction "1_1") (pintype "bidirectional"))
    )
    (net (code "352") (name "unconnected-(P218-Pad1)") (class "Default")
      (node (ref "P218") (pin "1") (pinfunction "1_1") (pintype "bidirectional"))
    )
    (net (code "353") (name "unconnected-(P219-Pad1)") (class "Default")
      (node (ref "P219") (pin "1") (pinfunction "1_1") (pintype "bidirectional"))
    )
    (net (code "354") (name "unconnected-(P220-Pad1)") (class "Default")
      (node (ref "P220") (pin "1") (pinfunction "1_1") (pintype "bidirectional"))
    )
    (net (code "355") (name "unconnected-(P221-Pad1)") (class "Default")
      (node (ref "P221") (pin "1") (pinfunction "1_1") (pintype "bidirectional"))
    )
    (net (code "356") (name "unconnected-(P222-Pad1)") (class "Default")
      (node (ref "P222") (pin "1") (pinfunction "1_1") (pintype "bidirectional"))
    )
    (net (code "357") (name "unconnected-(P223-Pad1)") (class "Default")
      (node (ref "P223") (pin "1") (pinfunction "1_1") (pintype "bidirectional"))
    )
    (net (code "358") (name "unconnected-(P224-Pad1)") (class "Default")
      (node (ref "P224") (pin "1") (pinfunction "1_1") (pintype "bidirectional"))
    )
    (net (code "359") (name "unconnected-(P225-Pad1)") (class "Default")
      (node (ref "P225") (pin "1") (pinfunction "1_1") (pintype "bidirectional"))
    )
    (net (code "360") (name "unconnected-(P226-Pad1)") (class "Default")
      (node (ref "P226") (pin "1") (pinfunction "1_1") (pintype "bidirectional"))
    )
    (net (code "361") (name "unconnected-(P227-Pad1)") (class "Default")
      (node (ref "P227") (pin "1") (pinfunction "1_1") (pintype "bidirectional"))
    )
    (net (code "362") (name "unconnected-(P228-Pad1)") (class "Default")
      (node (ref "P228") (pin "1") (pinfunction "1_1") (pintype "bidirectional"))
    )
    (net (code "363") (name "unconnected-(P229-Pad1)") (class "Default")
      (node (ref "P229") (pin "1") (pinfunction "1_1") (pintype "bidirectional"))
    )
    (net (code "364") (name "unconnected-(P230-Pad1)") (class "Default")
      (node (ref "P230") (pin "1") (pinfunction "1_1") (pintype "bidirectional"))
    )
    (net (code "365") (name "unconnected-(P231-Pad1)") (class "Default")
      (node (ref "P231") (pin "1") (pinfunction "1_1") (pintype "bidirectional"))
    )
    (net (code "366") (name "unconnected-(P232-Pad1)") (class "Default")
      (node (ref "P232") (pin "1") (pinfunction "1_1") (pintype "bidirectional"))
    )
    (net (code "367") (name "unconnected-(P233-Pad1)") (class "Default")
      (node (ref "P233") (pin "1") (pinfunction "1_1") (pintype "bidirectional"))
    )
    (net (code "368") (name "unconnected-(P234-Pad1)") (class "Default")
      (node (ref "P234") (pin "1") (pinfunction "1_1") (pintype "bidirectional"))
    )
    (net (code "369") (name "unconnected-(P235-Pad1)") (class "Default")
      (node (ref "P235") (pin "1") (pinfunction "1_1") (pintype "bidirectional"))
    )
    (net (code "370") (name "unconnected-(P236-Pad1)") (class "Default")
      (node (ref "P236") (pin "1") (pinfunction "1_1") (pintype "bidirectional"))
    )
    (net (code "371") (name "unconnected-(P237-Pad1)") (class "Default")
      (node (ref "P237") (pin "1") (pinfunction "1_1") (pintype "bidirectional"))
    )
    (net (code "372") (name "unconnected-(P238-Pad1)") (class "Default")
      (node (ref "P238") (pin "1") (pinfunction "1_1") (pintype "bidirectional"))
    )
    (net (code "373") (name "unconnected-(P239-Pad1)") (class "Default")
      (node (ref "P239") (pin "1") (pinfunction "1_1") (pintype "bidirectional"))
    )
    (net (code "374") (name "unconnected-(P240-Pad1)") (class "Default")
      (node (ref "P240") (pin "1") (pinfunction "1_1") (pintype "bidirectional"))
    )
    (net (code "375") (name "unconnected-(P241-Pad1)") (class "Default")
      (node (ref "P241") (pin "1") (pinfunction "1_1") (pintype "bidirectional"))
    )
    (net (code "376") (name "unconnected-(P242-Pad1)") (class "Default")
      (node (ref "P242") (pin "1") (pinfunction "1_1") (pintype "bidirectional"))
    )
    (net (code "377") (name "unconnected-(P243-Pad1)") (class "Default")
      (node (ref "P243") (pin "1") (pinfunction "1_1") (pintype "bidirectional"))
    )
    (net (code "378") (name "unconnected-(P244-Pad1)") (class "Default")
      (node (ref "P244") (pin "1") (pinfunction "1_1") (pintype "bidirectional"))
    )
    (net (code "379") (name "unconnected-(P245-Pad1)") (class "Default")
      (node (ref "P245") (pin "1") (pinfunction "1_1") (pintype "bidirectional"))
    )
    (net (code "380") (name "unconnected-(P246-Pad1)") (class "Default")
      (node (ref "P246") (pin "1") (pinfunction "1_1") (pintype "bidirectional"))
    )
    (net (code "381") (name "unconnected-(P247-Pad1)") (class "Default")
      (node (ref "P247") (pin "1") (pinfunction "1_1") (pintype "bidirectional"))
    )
    (net (code "382") (name "unconnected-(P248-Pad1)") (class "Default")
      (node (ref "P248") (pin "1") (pinfunction "1_1") (pintype "bidirectional"))
    )
    (net (code "383") (name "unconnected-(P249-Pad1)") (class "Default")
      (node (ref "P249") (pin "1") (pinfunction "1_1") (pintype "bidirectional"))
    )
    (net (code "384") (name "unconnected-(P250-Pad1)") (class "Default")
      (node (ref "P250") (pin "1") (pinfunction "1_1") (pintype "bidirectional"))
    )
    (net (code "385") (name "unconnected-(P251-Pad1)") (class "Default")
      (node (ref "P251") (pin "1") (pinfunction "1_1") (pintype "bidirectional"))
    )
    (net (code "386") (name "unconnected-(P252-Pad1)") (class "Default")
      (node (ref "P252") (pin "1") (pinfunction "1_1") (pintype "bidirectional"))
    )
    (net (code "387") (name "unconnected-(P253-Pad1)") (class "Default")
      (node (ref "P253") (pin "1") (pinfunction "1_1") (pintype "bidirectional"))
    )
    (net (code "388") (name "unconnected-(P254-Pad1)") (class "Default")
      (node (ref "P254") (pin "1") (pinfunction "1_1") (pintype "bidirectional"))
    )
    (net (code "389") (name "unconnected-(P255-Pad1)") (class "Default")
      (node (ref "P255") (pin "1") (pinfunction "1_1") (pintype "bidirectional"))
    )
    (net (code "390") (name "unconnected-(P256-Pad1)") (class "Default")
      (node (ref "P256") (pin "1") (pinfunction "1_1") (pintype "bidirectional"))
    )
    (net (code "391") (name "unconnected-(P257-Pad1)") (class "Default")
      (node (ref "P257") (pin "1") (pinfunction "1_1") (pintype "bidirectional"))
    )
    (net (code "392") (name "unconnected-(P258-Pad1)") (class "Default")
      (node (ref "P258") (pin "1") (pinfunction "1_1") (pintype "bidirectional"))
    )
    (net (code "393") (name "unconnected-(P259-Pad1)") (class "Default")
      (node (ref "P259") (pin "1") (pinfunction "1_1") (pintype "bidirectional"))
    )
    (net (code "394") (name "unconnected-(P260-Pad1)") (class "Default")
      (node (ref "P260") (pin "1") (pinfunction "1_1") (pintype "bidirectional"))
    )
    (net (code "395") (name "unconnected-(P261-Pad1)") (class "Default")
      (node (ref "P261") (pin "1") (pinfunction "1_1") (pintype "bidirectional"))
    )
    (net (code "396") (name "unconnected-(P262-Pad1)") (class "Default")
      (node (ref "P262") (pin "1") (pinfunction "1_1") (pintype "bidirectional"))
    )
    (net (code "397") (name "unconnected-(P263-Pad1)") (class "Default")
      (node (ref "P263") (pin "1") (pinfunction "1_1") (pintype "bidirectional"))
    )
    (net (code "398") (name "unconnected-(P264-Pad1)") (class "Default")
      (node (ref "P264") (pin "1") (pinfunction "1_1") (pintype "bidirectional"))
    )
    (net (code "399") (name "unconnected-(P265-Pad1)") (class "Default")
      (node (ref "P265") (pin "1") (pinfunction "1_1") (pintype "bidirectional"))
    )
    (net (code "400") (name "unconnected-(P266-Pad1)") (class "Default")
      (node (ref "P266") (pin "1") (pinfunction "1_1") (pintype "bidirectional"))
    )
    (net (code "401") (name "unconnected-(P267-Pad1)") (class "Default")
      (node (ref "P267") (pin "1") (pinfunction "1_1") (pintype "bidirectional"))
    )
    (net (code "402") (name "unconnected-(P268-Pad1)") (class "Default")
      (node (ref "P268") (pin "1") (pinfunction "1_1") (pintype "bidirectional"))
    )
    (net (code "403") (name "unconnected-(P269-Pad1)") (class "Default")
      (node (ref "P269") (pin "1") (pinfunction "1_1") (pintype "bidirectional"))
    )
    (net (code "404") (name "unconnected-(P270-Pad1)") (class "Default")
      (node (ref "P270") (pin "1") (pinfunction "1_1") (pintype "bidirectional"))
    )
    (net (code "405") (name "unconnected-(P271-Pad1)") (class "Default")
      (node (ref "P271") (pin "1") (pinfunction "1_1") (pintype "bidirectional"))
    )
    (net (code "406") (name "unconnected-(P272-Pad1)") (class "Default")
      (node (ref "P272") (pin "1") (pinfunction "1_1") (pintype "bidirectional"))
    )
    (net (code "407") (name "unconnected-(P273-Pad1)") (class "Default")
      (node (ref "P273") (pin "1") (pinfunction "1_1") (pintype "bidirectional"))
    )
    (net (code "408") (name "unconnected-(P274-Pad1)") (class "Default")
      (node (ref "P274") (pin "1") (pinfunction "1_1") (pintype "bidirectional"))
    )
    (net (code "409") (name "unconnected-(P275-Pad1)") (class "Default")
      (node (ref "P275") (pin "1") (pinfunction "1_1") (pintype "bidirectional"))
    )
    (net (code "410") (name "unconnected-(P276-Pad1)") (class "Default")
      (node (ref "P276") (pin "1") (pinfunction "1_1") (pintype "bidirectional"))
    )
    (net (code "411") (name "unconnected-(P277-Pad1)") (class "Default")
      (node (ref "P277") (pin "1") (pinfunction "1_1") (pintype "bidirectional"))
    )
    (net (code "412") (name "unconnected-(P278-Pad1)") (class "Default")
      (node (ref "P278") (pin "1") (pinfunction "1_1") (pintype "bidirectional"))
    )
    (net (code "413") (name "unconnected-(P279-Pad1)") (class "Default")
      (node (ref "P279") (pin "1") (pinfunction "1_1") (pintype "bidirectional"))
    )
    (net (code "414") (name "unconnected-(P280-Pad1)") (class "Default")
      (node (ref "P280") (pin "1") (pinfunction "1_1") (pintype "bidirectional"))
    )
    (net (code "415") (name "unconnected-(P281-Pad1)") (class "Default")
      (node (ref "P281") (pin "1") (pinfunction "1_1") (pintype "bidirectional"))
    )
    (net (code "416") (name "unconnected-(P282-Pad1)") (class "Default")
      (node (ref "P282") (pin "1") (pinfunction "1_1") (pintype "bidirectional"))
    )
    (net (code "417") (name "unconnected-(P283-Pad1)") (class "Default")
      (node (ref "P283") (pin "1") (pinfunction "1_1") (pintype "bidirectional"))
    )
    (net (code "418") (name "unconnected-(P284-Pad1)") (class "Default")
      (node (ref "P284") (pin "1") (pinfunction "1_1") (pintype "bidirectional"))
    )
    (net (code "419") (name "unconnected-(P285-Pad1)") (class "Default")
      (node (ref "P285") (pin "1") (pinfunction "1_1") (pintype "bidirectional"))
    )
    (net (code "420") (name "unconnected-(P286-Pad1)") (class "Default")
      (node (ref "P286") (pin "1") (pinfunction "1_1") (pintype "bidirectional"))
    )
    (net (code "421") (name "unconnected-(P287-Pad1)") (class "Default")
      (node (ref "P287") (pin "1") (pinfunction "1_1") (pintype "bidirectional"))
    )
    (net (code "422") (name "unconnected-(P288-Pad1)") (class "Default")
      (node (ref "P288") (pin "1") (pinfunction "1_1") (pintype "bidirectional"))
    )
    (net (code "423") (name "unconnected-(P289-Pad1)") (class "Default")
      (node (ref "P289") (pin "1") (pinfunction "1_1") (pintype "bidirectional"))
    )
    (net (code "424") (name "unconnected-(P290-Pad1)") (class "Default")
      (node (ref "P290") (pin "1") (pinfunction "1_1") (pintype "bidirectional"))
    )
    (net (code "425") (name "unconnected-(P291-Pad1)") (class "Default")
      (node (ref "P291") (pin "1") (pinfunction "1_1") (pintype "bidirectional"))
    )
    (net (code "426") (name "unconnected-(P292-Pad1)") (class "Default")
      (node (ref "P292") (pin "1") (pinfunction "1_1") (pintype "bidirectional"))
    )
    (net (code "427") (name "unconnected-(P293-Pad1)") (class "Default")
      (node (ref "P293") (pin "1") (pinfunction "1_1") (pintype "bidirectional"))
    )
    (net (code "428") (name "unconnected-(P294-Pad1)") (class "Default")
      (node (ref "P294") (pin "1") (pinfunction "1_1") (pintype "bidirectional"))
    )
    (net (code "429") (name "unconnected-(P295-Pad1)") (class "Default")
      (node (ref "P295") (pin "1") (pinfunction "1_1") (pintype "bidirectional"))
    )
    (net (code "430") (name "unconnected-(P296-Pad1)") (class "Default")
      (node (ref "P296") (pin "1") (pinfunction "1_1") (pintype "bidirectional"))
    )
    (net (code "431") (name "unconnected-(P297-Pad1)") (class "Default")
      (node (ref "P297") (pin "1") (pinfunction "1_1") (pintype "bidirectional"))
    )
    (net (code "432") (name "unconnected-(P298-Pad1)") (class "Default")
      (node (ref "P298") (pin "1") (pinfunction "1_1") (pintype "bidirectional"))
    )
    (net (code "433") (name "unconnected-(P299-Pad1)") (class "Default")
      (node (ref "P299") (pin "1") (pinfunction "1_1") (pintype "bidirectional"))
    )
    (net (code "434") (name "unconnected-(P300-Pad1)") (class "Default")
      (node (ref "P300") (pin "1") (pinfunction "1_1") (pintype "bidirectional"))
    )
    (net (code "435") (name "unconnected-(P301-Pad1)") (class "Default")
      (node (ref "P301") (pin "1") (pinfunction "1_1") (pintype "bidirectional"))
    )
    (net (code "436") (name "unconnected-(P302-Pad1)") (class "Default")
      (node (ref "P302") (pin "1") (pinfunction "1_1") (pintype "bidirectional"))
    )
    (net (code "437") (name "unconnected-(P303-Pad1)") (class "Default")
      (node (ref "P303") (pin "1") (pinfunction "1_1") (pintype "bidirectional"))
    )
    (net (code "438") (name "unconnected-(P304-Pad1)") (class "Default")
      (node (ref "P304") (pin "1") (pinfunction "1_1") (pintype "bidirectional"))
    )
    (net (code "439") (name "unconnected-(P305-Pad1)") (class "Default")
      (node (ref "P305") (pin "1") (pinfunction "1_1") (pintype "bidirectional"))
    )
    (net (code "440") (name "unconnected-(P306-Pad1)") (class "Default")
      (node (ref "P306") (pin "1") (pinfunction "1_1") (pintype "bidirectional"))
    )
    (net (code "441") (name "unconnected-(P307-Pad1)") (class "Default")
      (node (ref "P307") (pin "1") (pinfunction "1_1") (pintype "bidirectional"))
    )
    (net (code "442") (name "unconnected-(P308-Pad1)") (class "Default")
      (node (ref "P308") (pin "1") (pinfunction "1_1") (pintype "bidirectional"))
    )
    (net (code "443") (name "unconnected-(P309-Pad1)") (class "Default")
      (node (ref "P309") (pin "1") (pinfunction "1_1") (pintype "bidirectional"))
    )
    (net (code "444") (name "unconnected-(P310-Pad1)") (class "Default")
      (node (ref "P310") (pin "1") (pinfunction "1_1") (pintype "bidirectional"))
    )
    (net (code "445") (name "unconnected-(P311-Pad1)") (class "Default")
      (node (ref "P311") (pin "1") (pinfunction "1_1") (pintype "bidirectional"))
    )
    (net (code "446") (name "unconnected-(P312-Pad1)") (class "Default")
      (node (ref "P312") (pin "1") (pinfunction "1_1") (pintype "bidirectional"))
    )
    (net (code "447") (name "unconnected-(P313-Pad1)") (class "Default")
      (node (ref "P313") (pin "1") (pinfunction "1_1") (pintype "bidirectional"))
    )
    (net (code "448") (name "unconnected-(P314-Pad1)") (class "Default")
      (node (ref "P314") (pin "1") (pinfunction "1_1") (pintype "bidirectional"))
    )
    (net (code "449") (name "unconnected-(P315-Pad1)") (class "Default")
      (node (ref "P315") (pin "1") (pinfunction "1_1") (pintype "bidirectional"))
    )
    (net (code "450") (name "unconnected-(SW1-Pad3)") (class "Default")
      (node (ref "SW1") (pin "3") (pinfunction "3_3") (pintype "passive"))
    )
    (net (code "451") (name "unconnected-(SW1-Pad4)") (class "Default")
      (node (ref "SW1") (pin "4") (pinfunction "4_4") (pintype "passive"))
    )
    (net (code "452") (name "unconnected-(SW2-Pad3)") (class "Default")
      (node (ref "SW2") (pin "3") (pinfunction "3_3") (pintype "passive"))
    )
    (net (code "453") (name "unconnected-(SW2-Pad4)") (class "Default")
      (node (ref "SW2") (pin "4") (pinfunction "4_4") (pintype "passive"))
    )
    (net (code "454") (name "unconnected-(SW3-Pad3)") (class "Default")
      (node (ref "SW3") (pin "3") (pinfunction "3_3") (pintype "passive"))
    )
    (net (code "455") (name "unconnected-(SW3-Pad4)") (class "Default")
      (node (ref "SW3") (pin "4") (pinfunction "4_4") (pintype "passive"))
    )
    (net (code "456") (name "unconnected-(SW4-Pad3)") (class "Default")
      (node (ref "SW4") (pin "3") (pinfunction "3_3") (pintype "passive"))
    )
    (net (code "457") (name "unconnected-(SW4-Pad4)") (class "Default")
      (node (ref "SW4") (pin "4") (pinfunction "4_4") (pintype "passive"))
    )
    (net (code "458") (name "unconnected-(SW5-Pad3)") (class "Default")
      (node (ref "SW5") (pin "3") (pinfunction "3_3") (pintype "passive"))
    )
    (net (code "459") (name "unconnected-(SW5-Pad4)") (class "Default")
      (node (ref "SW5") (pin "4") (pinfunction "4_4") (pintype "passive"))
    )
    (net (code "460") (name "unconnected-(SW6-Pad3)") (class "Default")
      (node (ref "SW6") (pin "3") (pinfunction "3_3") (pintype "passive"))
    )
    (net (code "461") (name "unconnected-(SW6-Pad4)") (class "Default")
      (node (ref "SW6") (pin "4") (pinfunction "4_4") (pintype "passive"))
    )
    (net (code "462") (name "unconnected-(SW7-Pad3)") (class "Default")
      (node (ref "SW7") (pin "3") (pinfunction "3_3") (pintype "passive"))
    )
    (net (code "463") (name "unconnected-(SW7-Pad4)") (class "Default")
      (node (ref "SW7") (pin "4") (pinfunction "4_4") (pintype "passive"))
    )
    (net (code "464") (name "unconnected-(SW8-Pad3)") (class "Default")
      (node (ref "SW8") (pin "3") (pinfunction "3_3") (pintype "passive"))
    )
    (net (code "465") (name "unconnected-(SW8-Pad4)") (class "Default")
      (node (ref "SW8") (pin "4") (pinfunction "4_4") (pintype "passive"))
    )
    (net (code "466") (name "unconnected-(SW9-Pad3)") (class "Default")
      (node (ref "SW9") (pin "3") (pinfunction "3_3") (pintype "passive"))
    )
    (net (code "467") (name "unconnected-(SW9-Pad4)") (class "Default")
      (node (ref "SW9") (pin "4") (pinfunction "4_4") (pintype "passive"))
    )
    (net (code "468") (name "unconnected-(SW10-Pad3)") (class "Default")
      (node (ref "SW10") (pin "3") (pinfunction "3_3") (pintype "passive"))
    )
    (net (code "469") (name "unconnected-(SW10-Pad4)") (class "Default")
      (node (ref "SW10") (pin "4") (pinfunction "4_4") (pintype "passive"))
    )
    (net (code "470") (name "unconnected-(SW11-Pad3)") (class "Default")
      (node (ref "SW11") (pin "3") (pinfunction "3_3") (pintype "passive"))
    )
    (net (code "471") (name "unconnected-(SW11-Pad4)") (class "Default")
      (node (ref "SW11") (pin "4") (pinfunction "4_4") (pintype "passive"))
    )
    (net (code "472") (name "unconnected-(SW12-Pad3)") (class "Default")
      (node (ref "SW12") (pin "3") (pinfunction "3_3") (pintype "passive"))
    )
    (net (code "473") (name "unconnected-(SW12-Pad4)") (class "Default")
      (node (ref "SW12") (pin "4") (pinfunction "4_4") (pintype "passive"))
    )
    (net (code "474") (name "unconnected-(SW13-Pad3)") (class "Default")
      (node (ref "SW13") (pin "3") (pinfunction "3_3") (pintype "passive"))
    )
    (net (code "475") (name "unconnected-(SW13-Pad4)") (class "Default")
      (node (ref "SW13") (pin "4") (pinfunction "4_4") (pintype "passive"))
    )
    (net (code "476") (name "unconnected-(SW14-Pad3)") (class "Default")
      (node (ref "SW14") (pin "3") (pinfunction "3_3") (pintype "passive"))
    )
    (net (code "477") (name "unconnected-(SW14-Pad4)") (class "Default")
      (node (ref "SW14") (pin "4") (pinfunction "4_4") (pintype "passive"))
    )
    (net (code "478") (name "unconnected-(SW15-Pad3)") (class "Default")
      (node (ref "SW15") (pin "3") (pinfunction "3_3") (pintype "passive"))
    )
    (net (code "479") (name "unconnected-(SW15-Pad4)") (class "Default")
      (node (ref "SW15") (pin "4") (pinfunction "4_4") (pintype "passive"))
    )
    (net (code "480") (name "unconnected-(SW16-Pad3)") (class "Default")
      (node (ref "SW16") (pin "3") (pinfunction "3_3") (pintype "passive"))
    )
    (net (code "481") (name "unconnected-(SW16-Pad4)") (class "Default")
      (node (ref "SW16") (pin "4") (pinfunction "4_4") (pintype "passive"))
    )
    (net (code "482") (name "unconnected-(SW17-Pad3)") (class "Default")
      (node (ref "SW17") (pin "3") (pinfunction "3_3") (pintype "passive"))
    )
    (net (code "483") (name "unconnected-(SW17-Pad4)") (class "Default")
      (node (ref "SW17") (pin "4") (pinfunction "4_4") (pintype "passive"))
    )
  )
)
